# ver5b.net
KiCad netlist of a schematic drawn in EAGLE
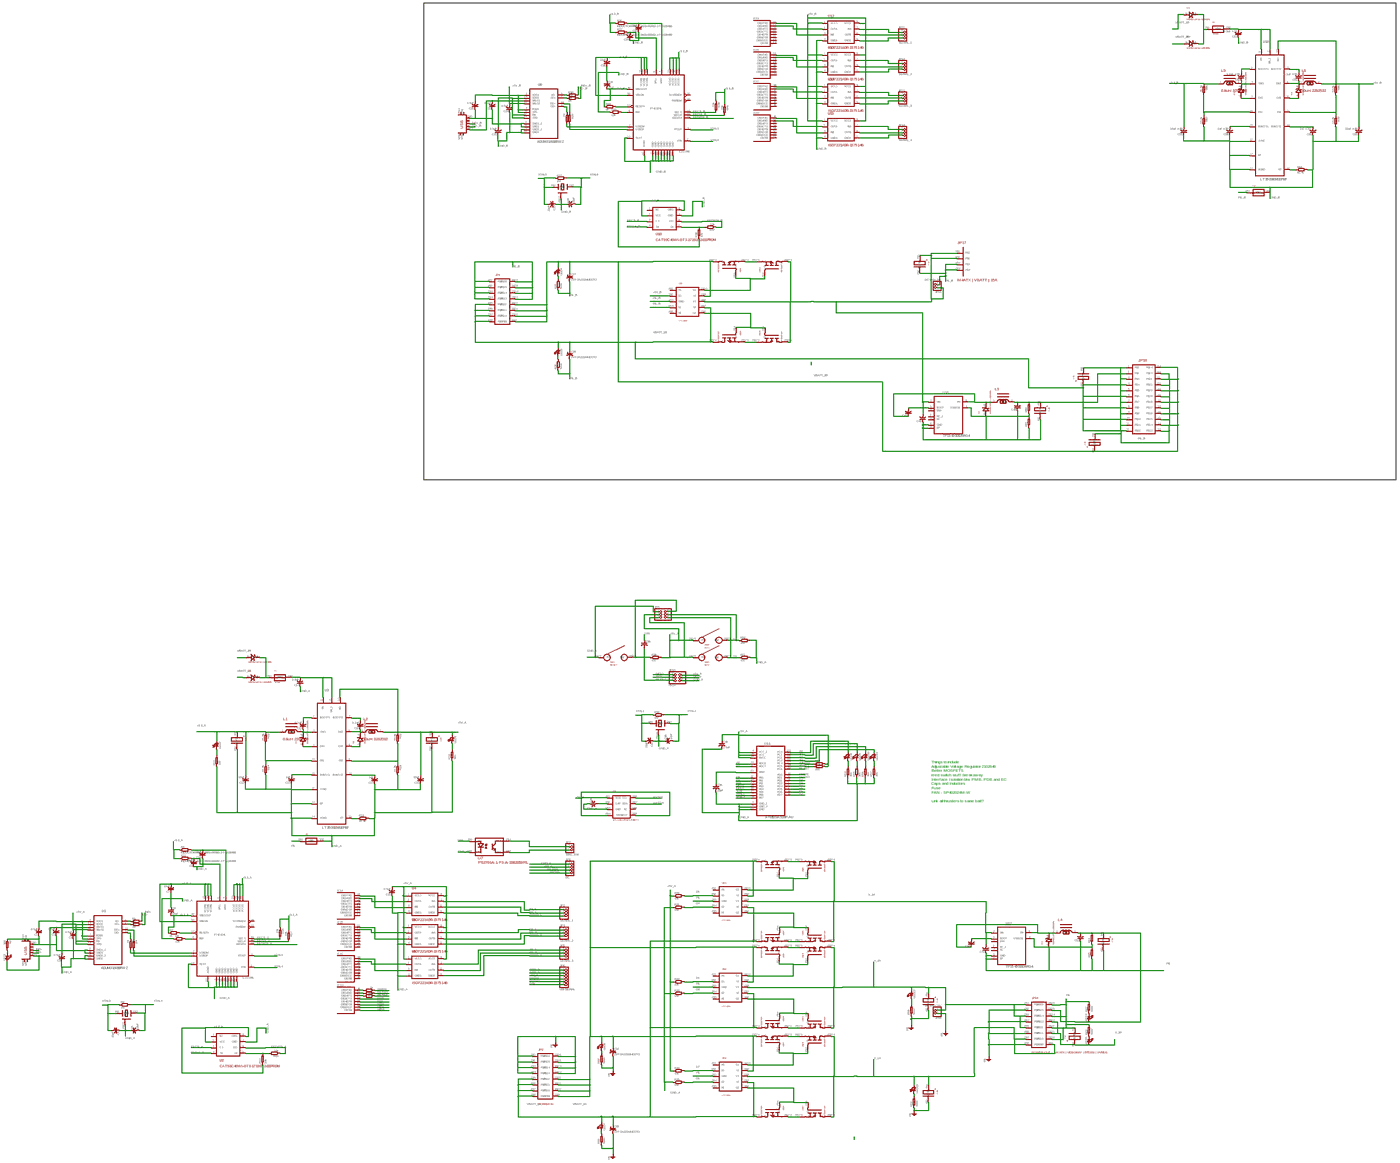
[diagram p0: schematic, sheet 1, overview]
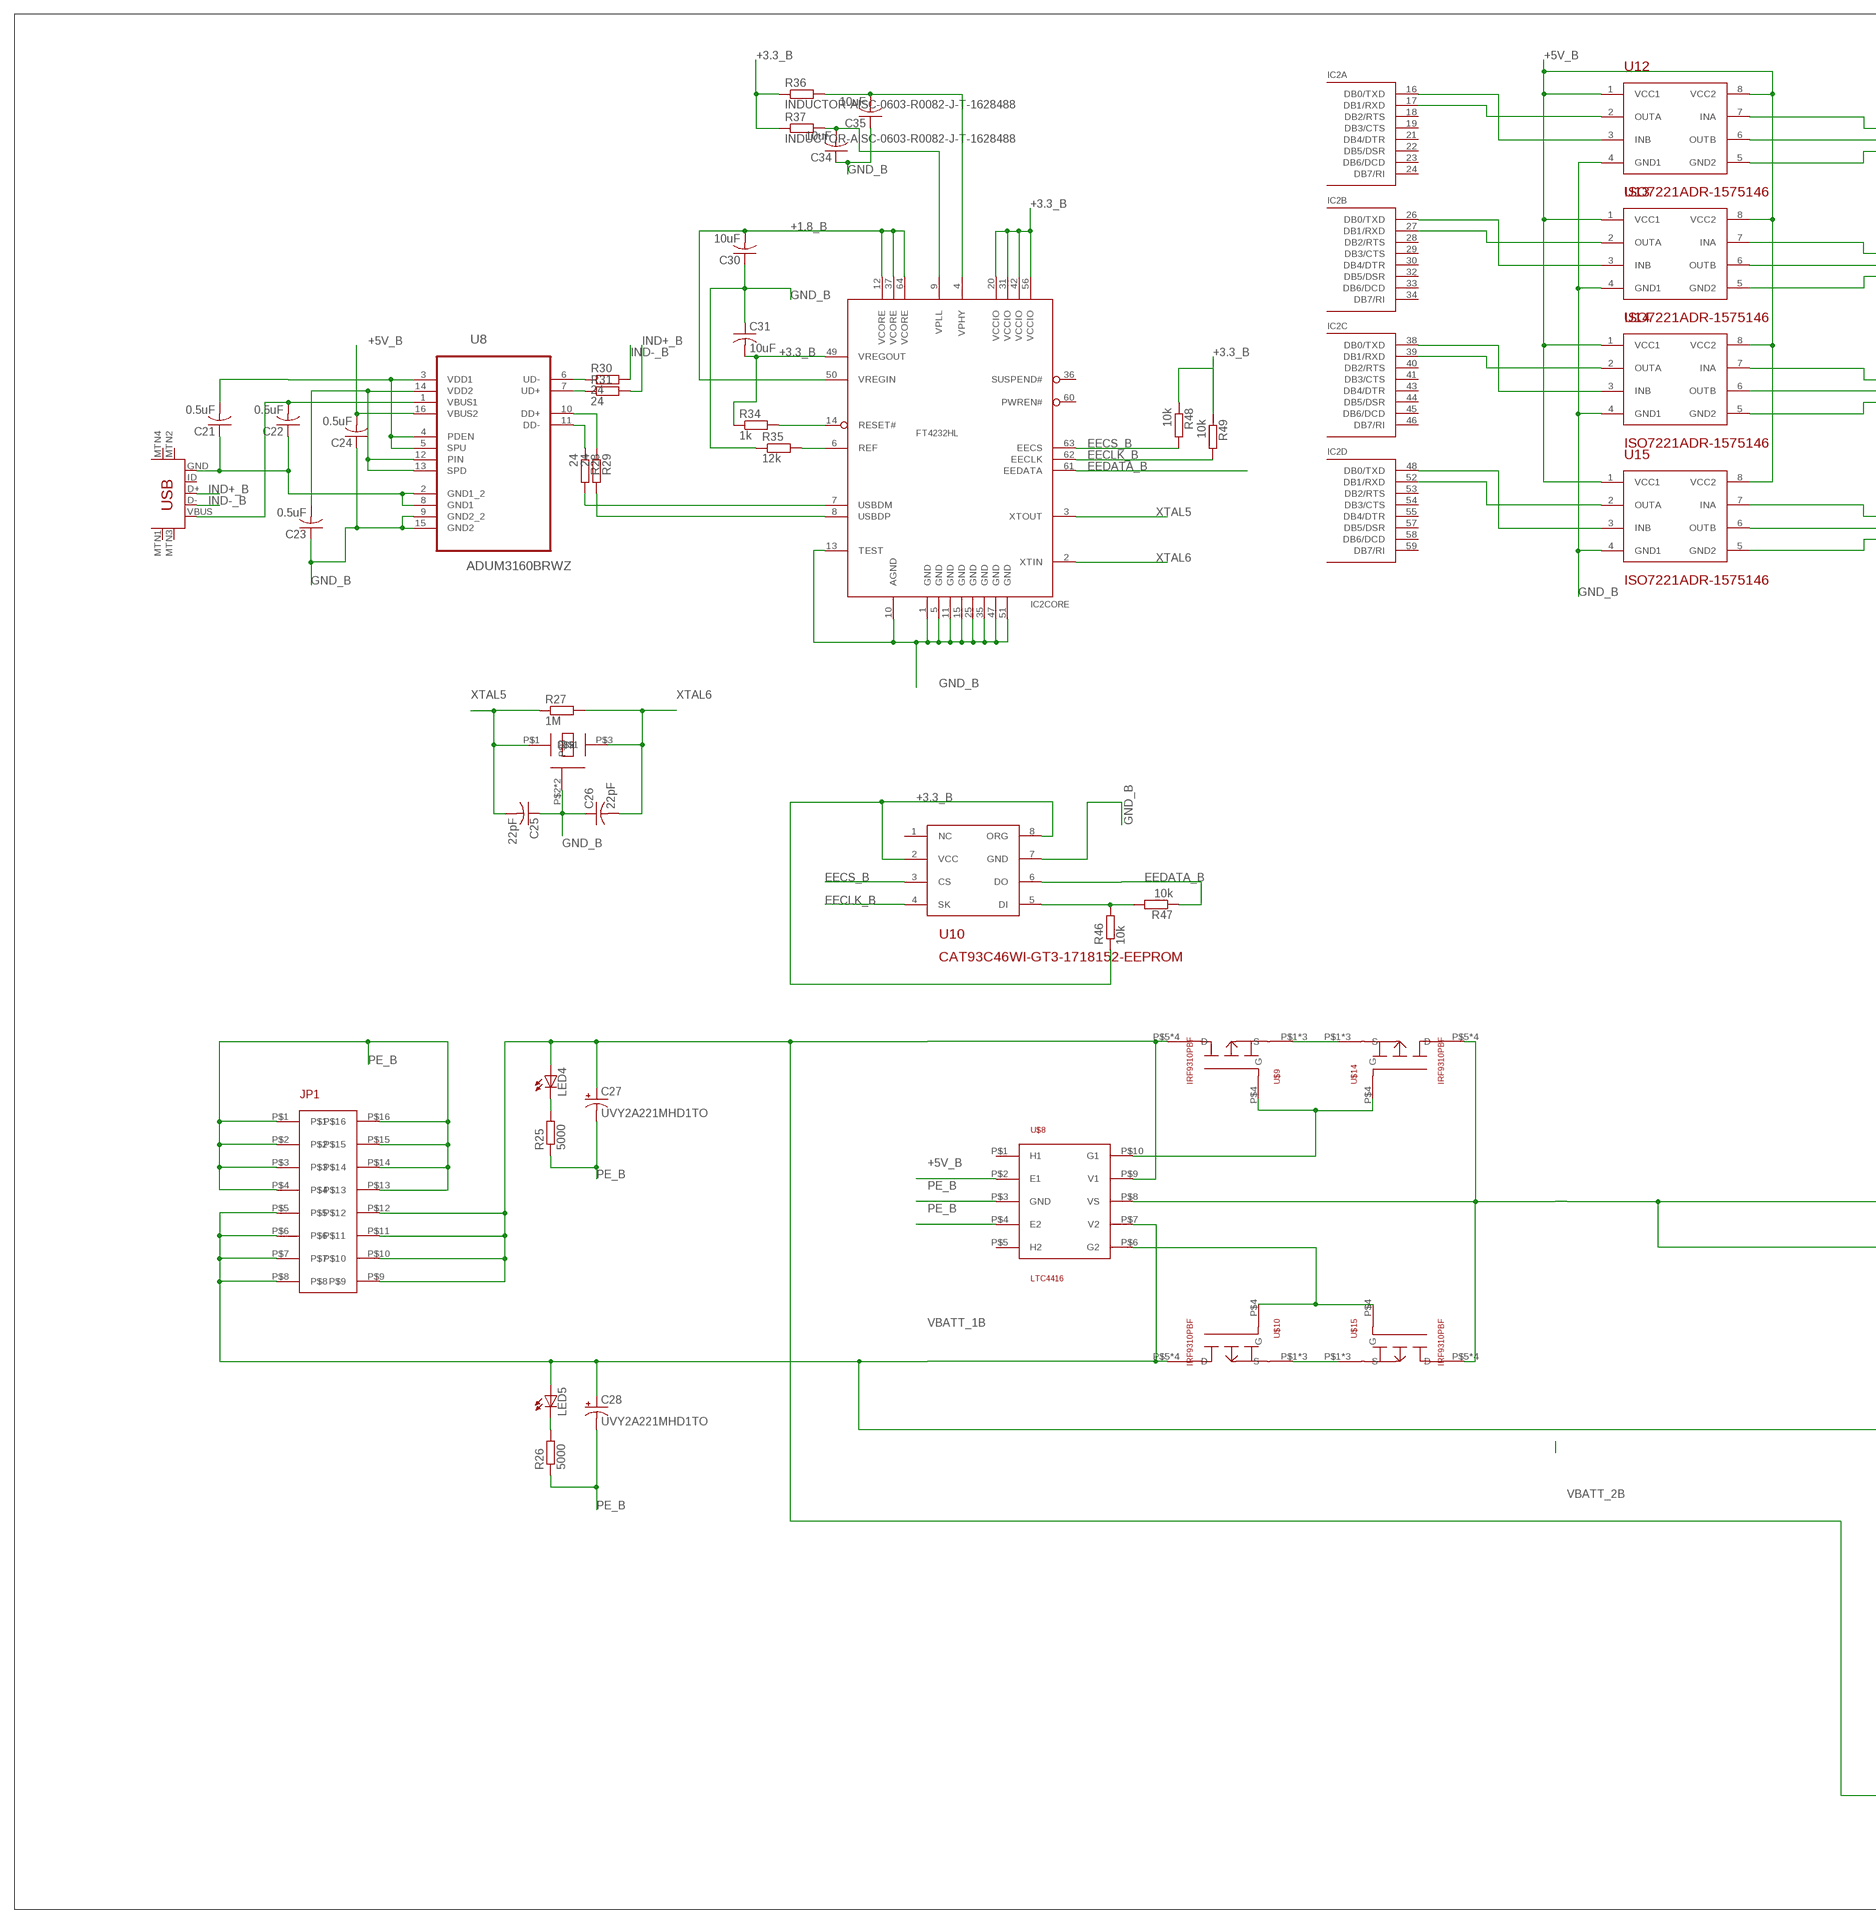
[diagram p1: schematic, sheet 1, part 1 of 6]
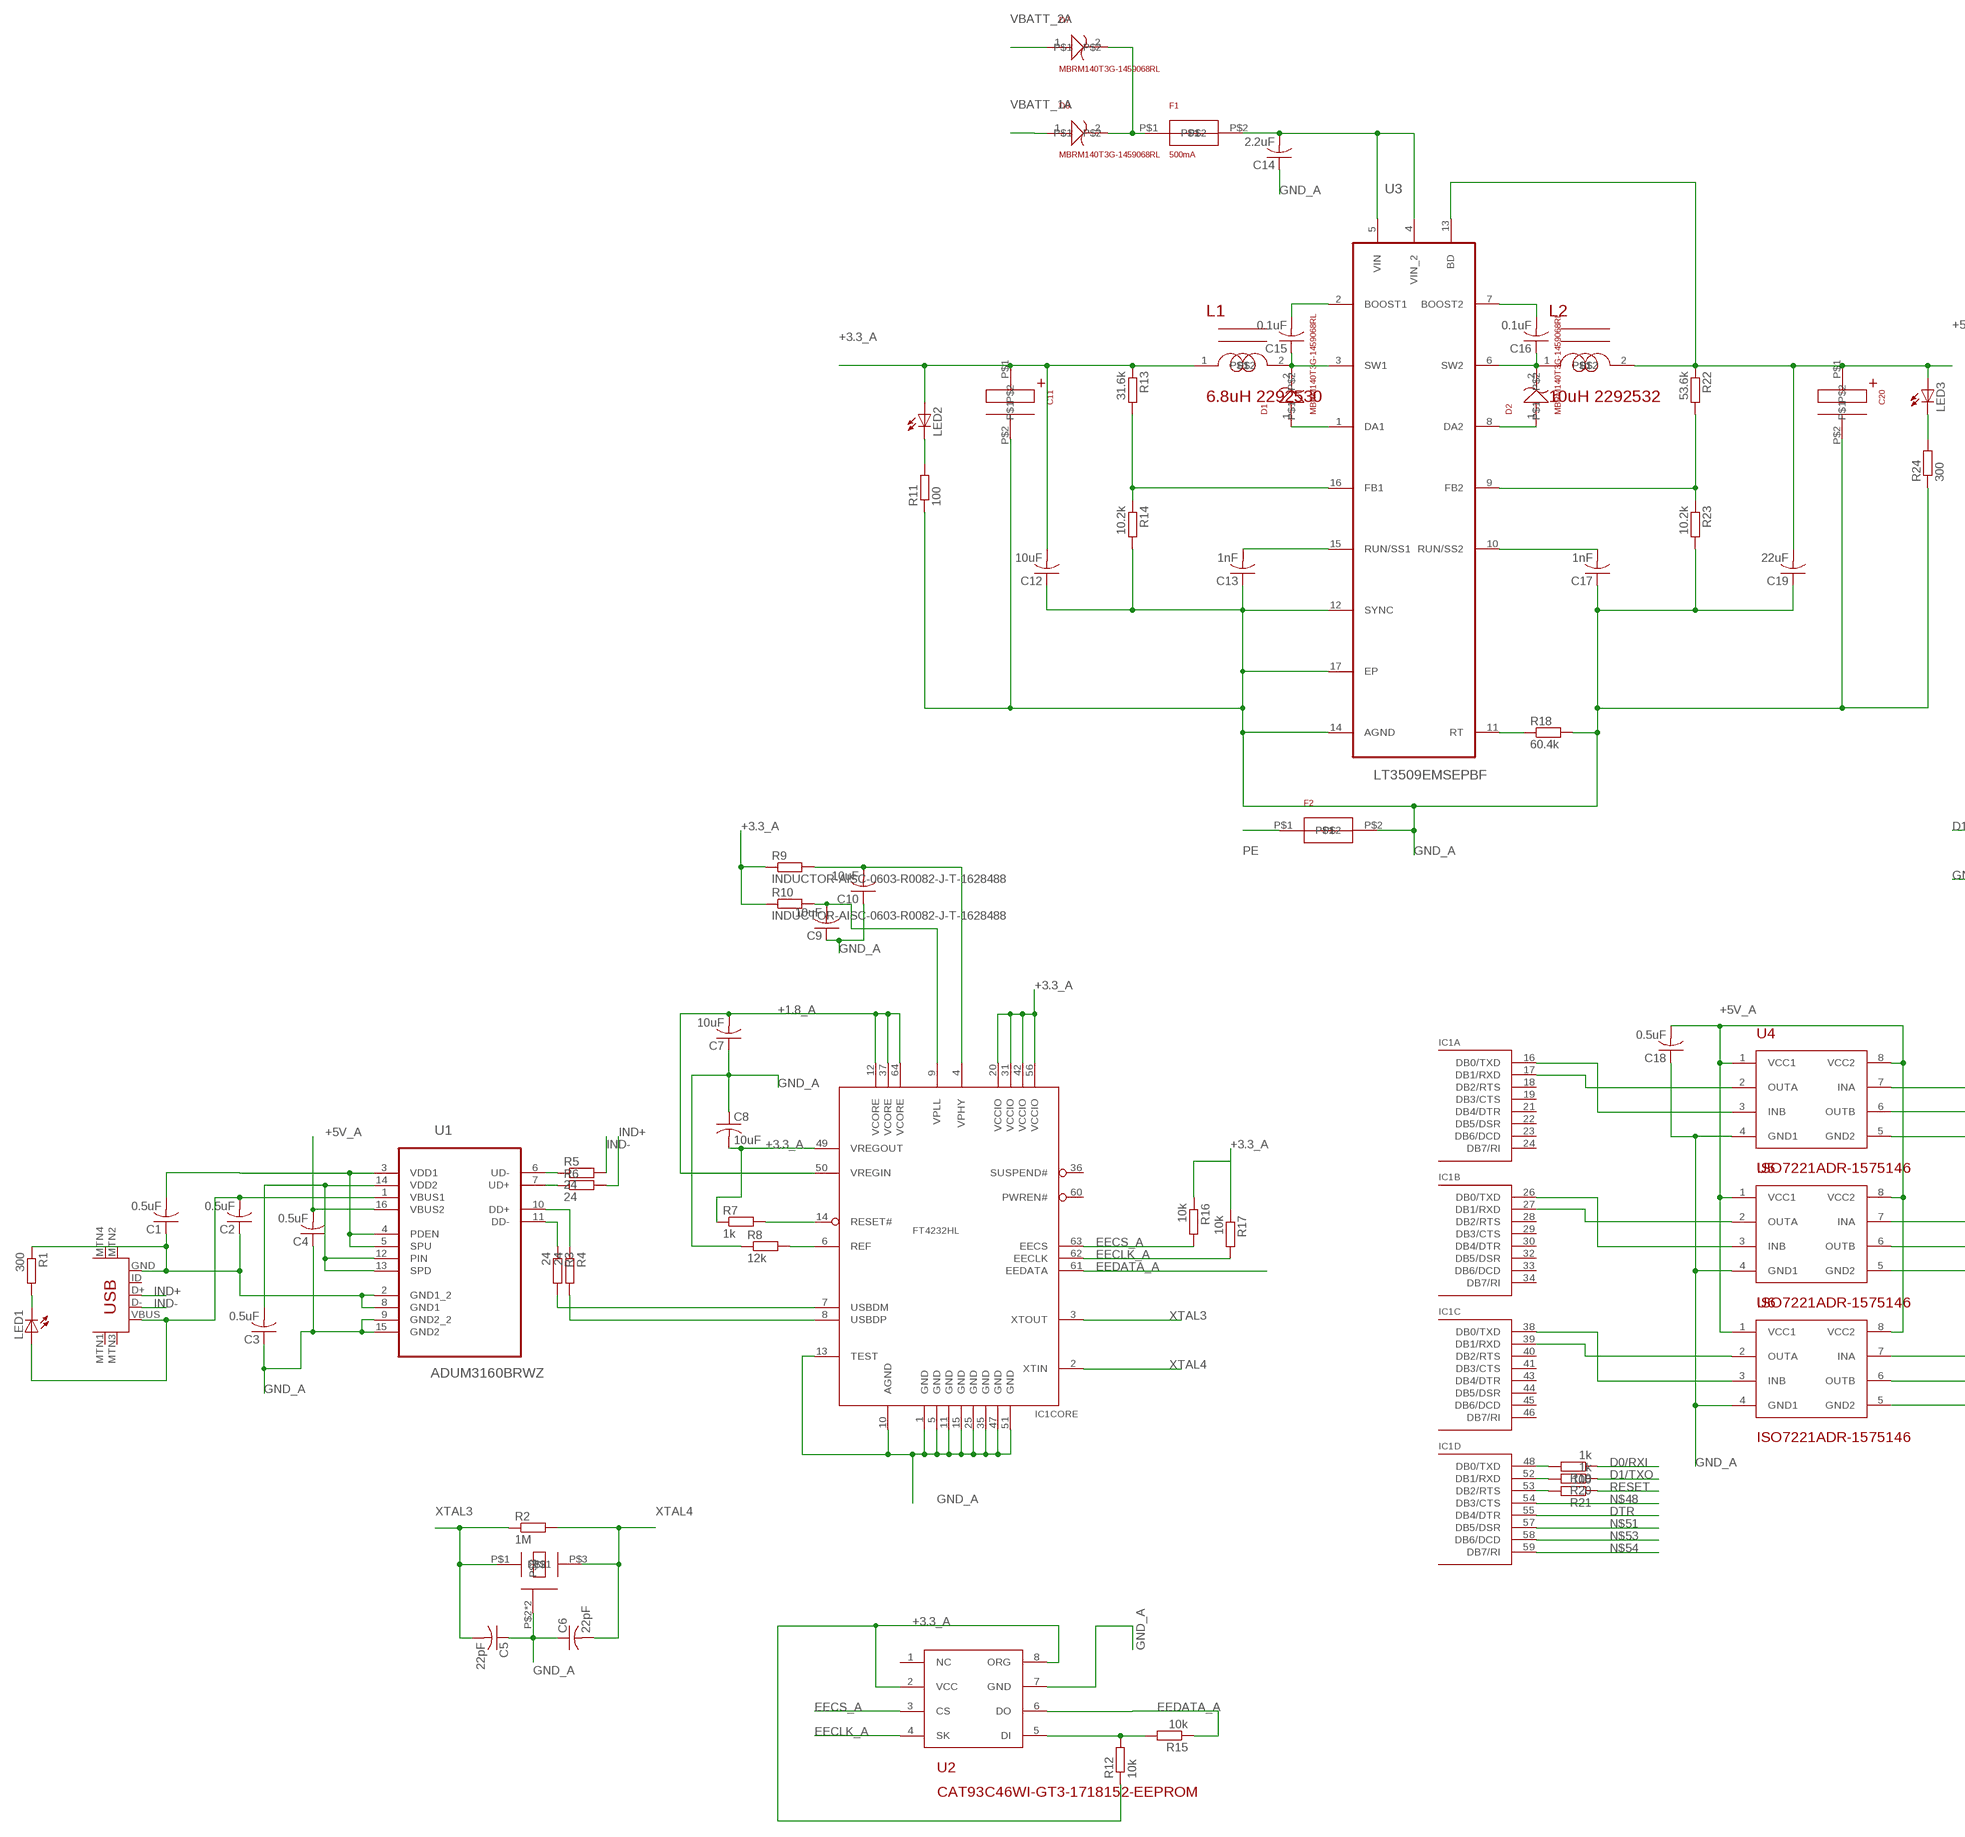
[diagram p2: schematic, sheet 1, part 2 of 6]
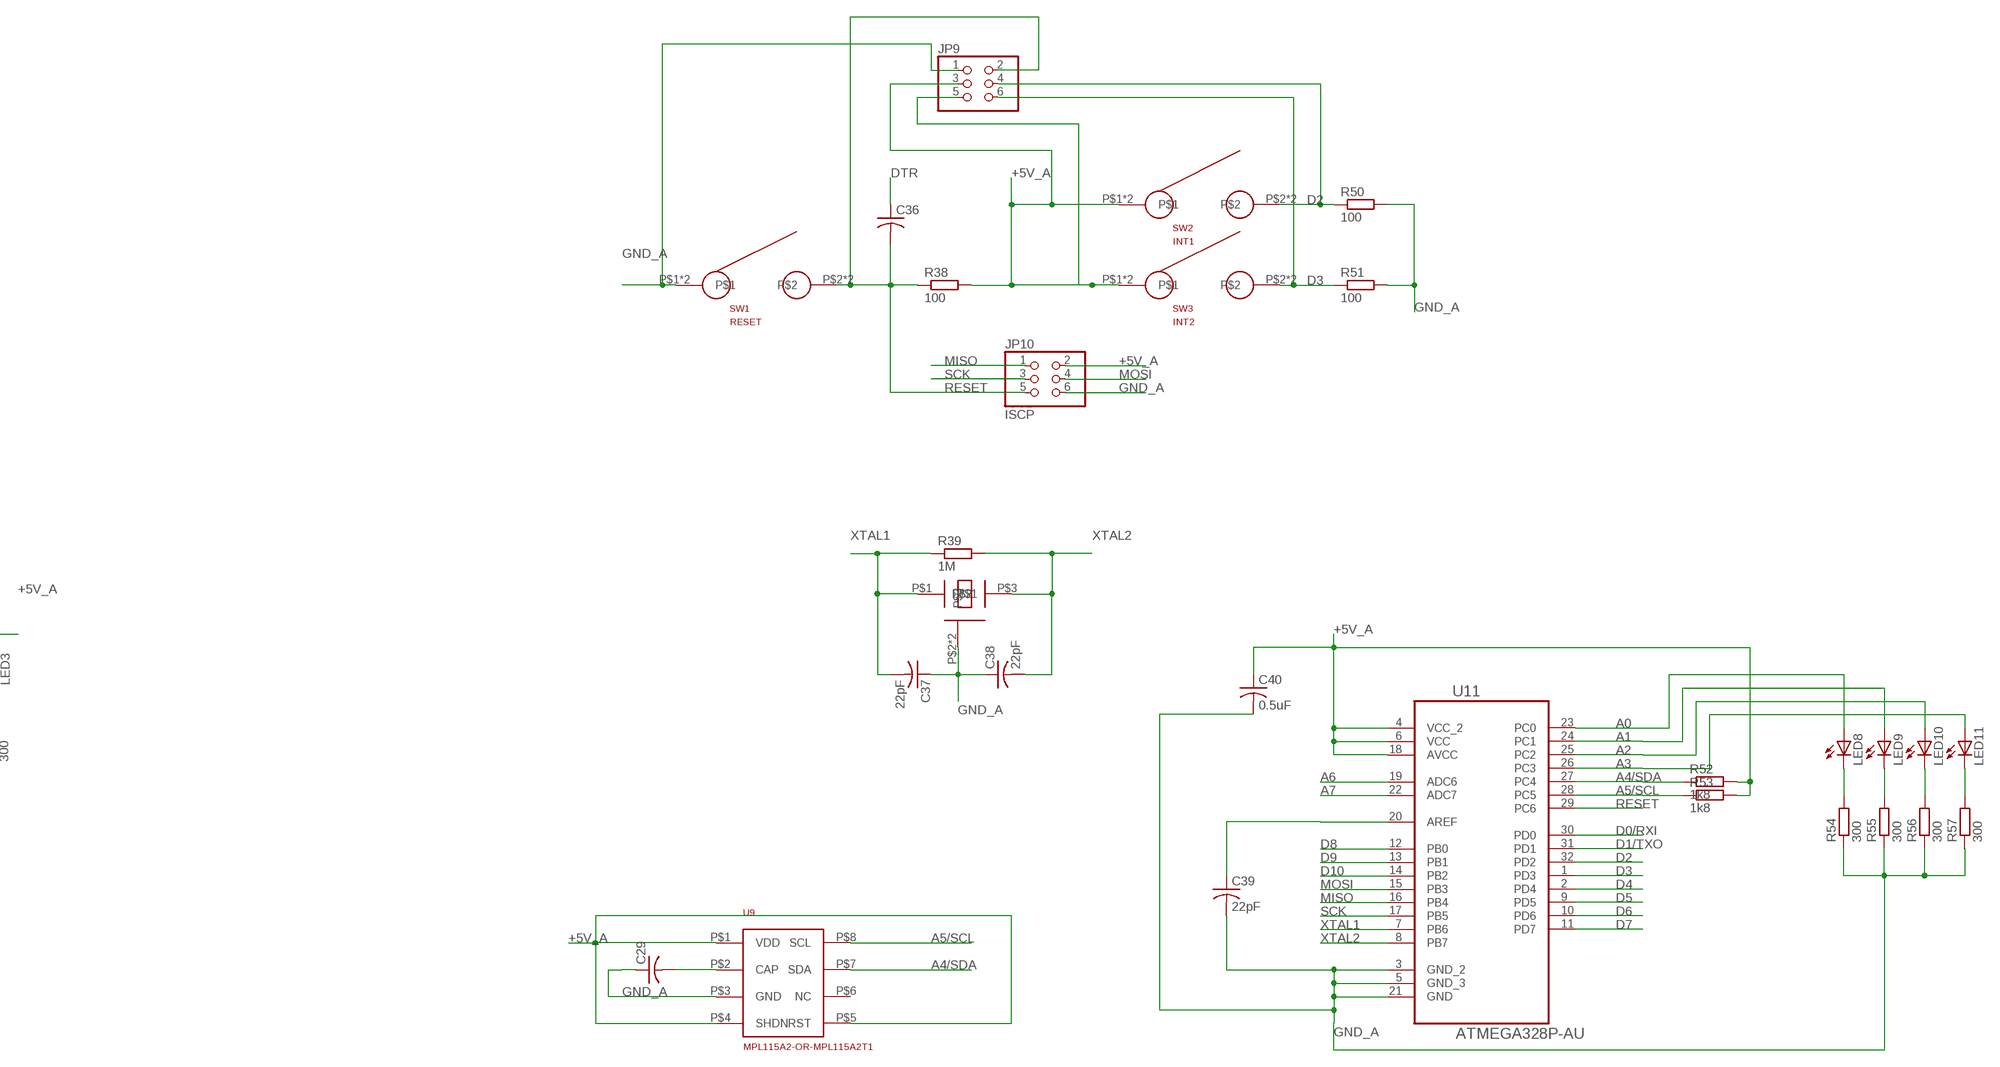
[diagram p3: schematic, sheet 1, part 3 of 6]
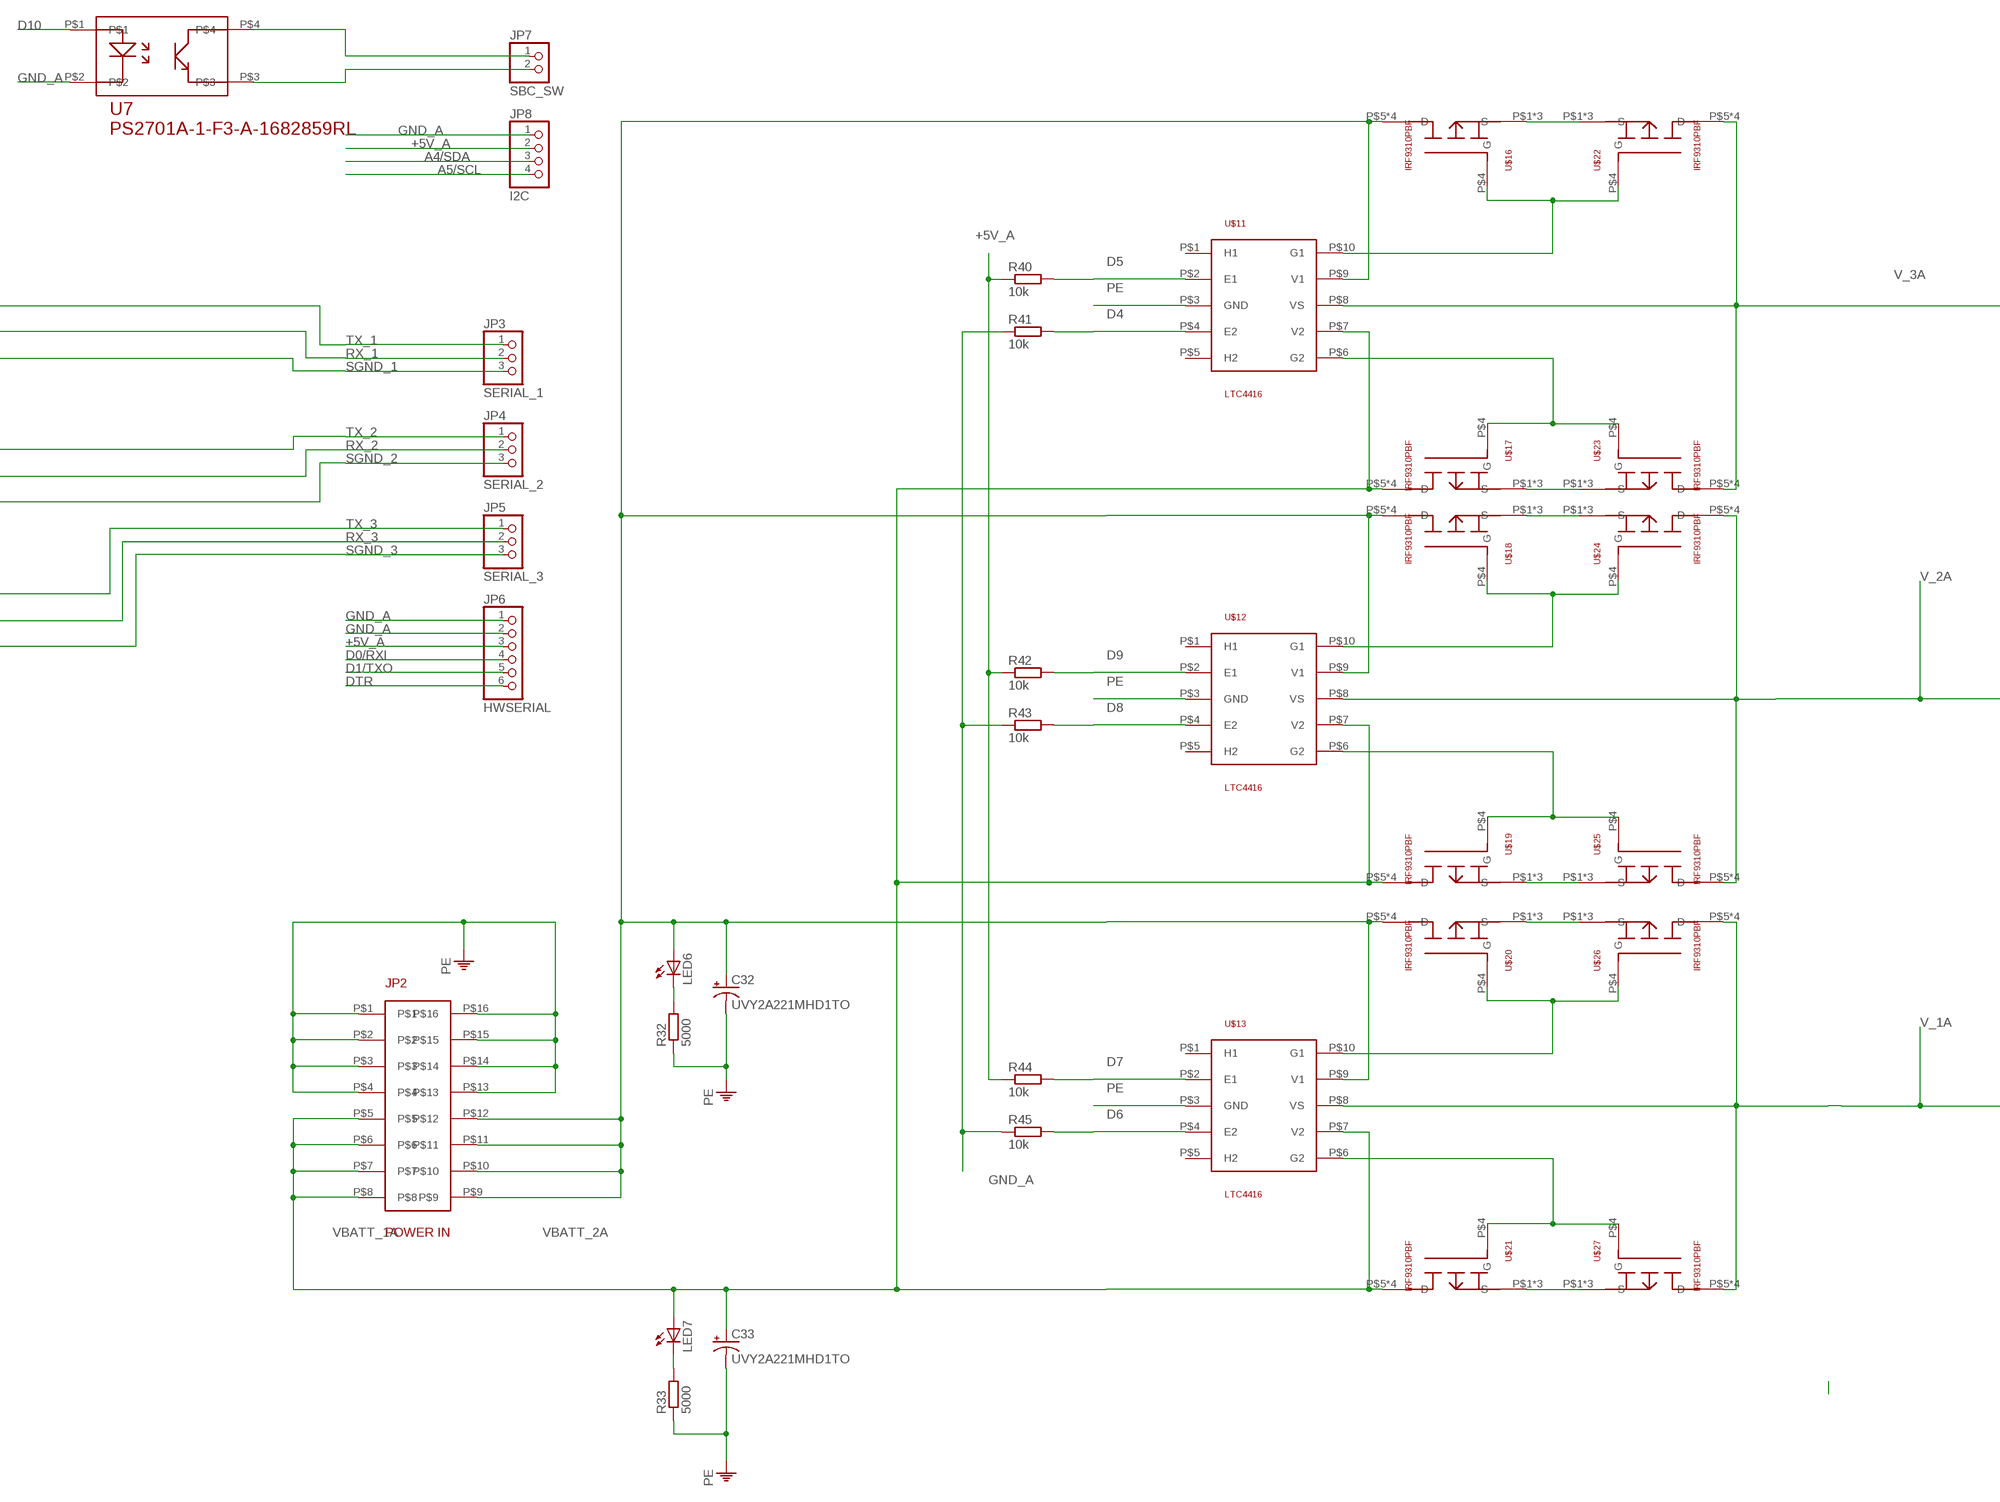
[diagram p4: schematic, sheet 1, part 4 of 6]
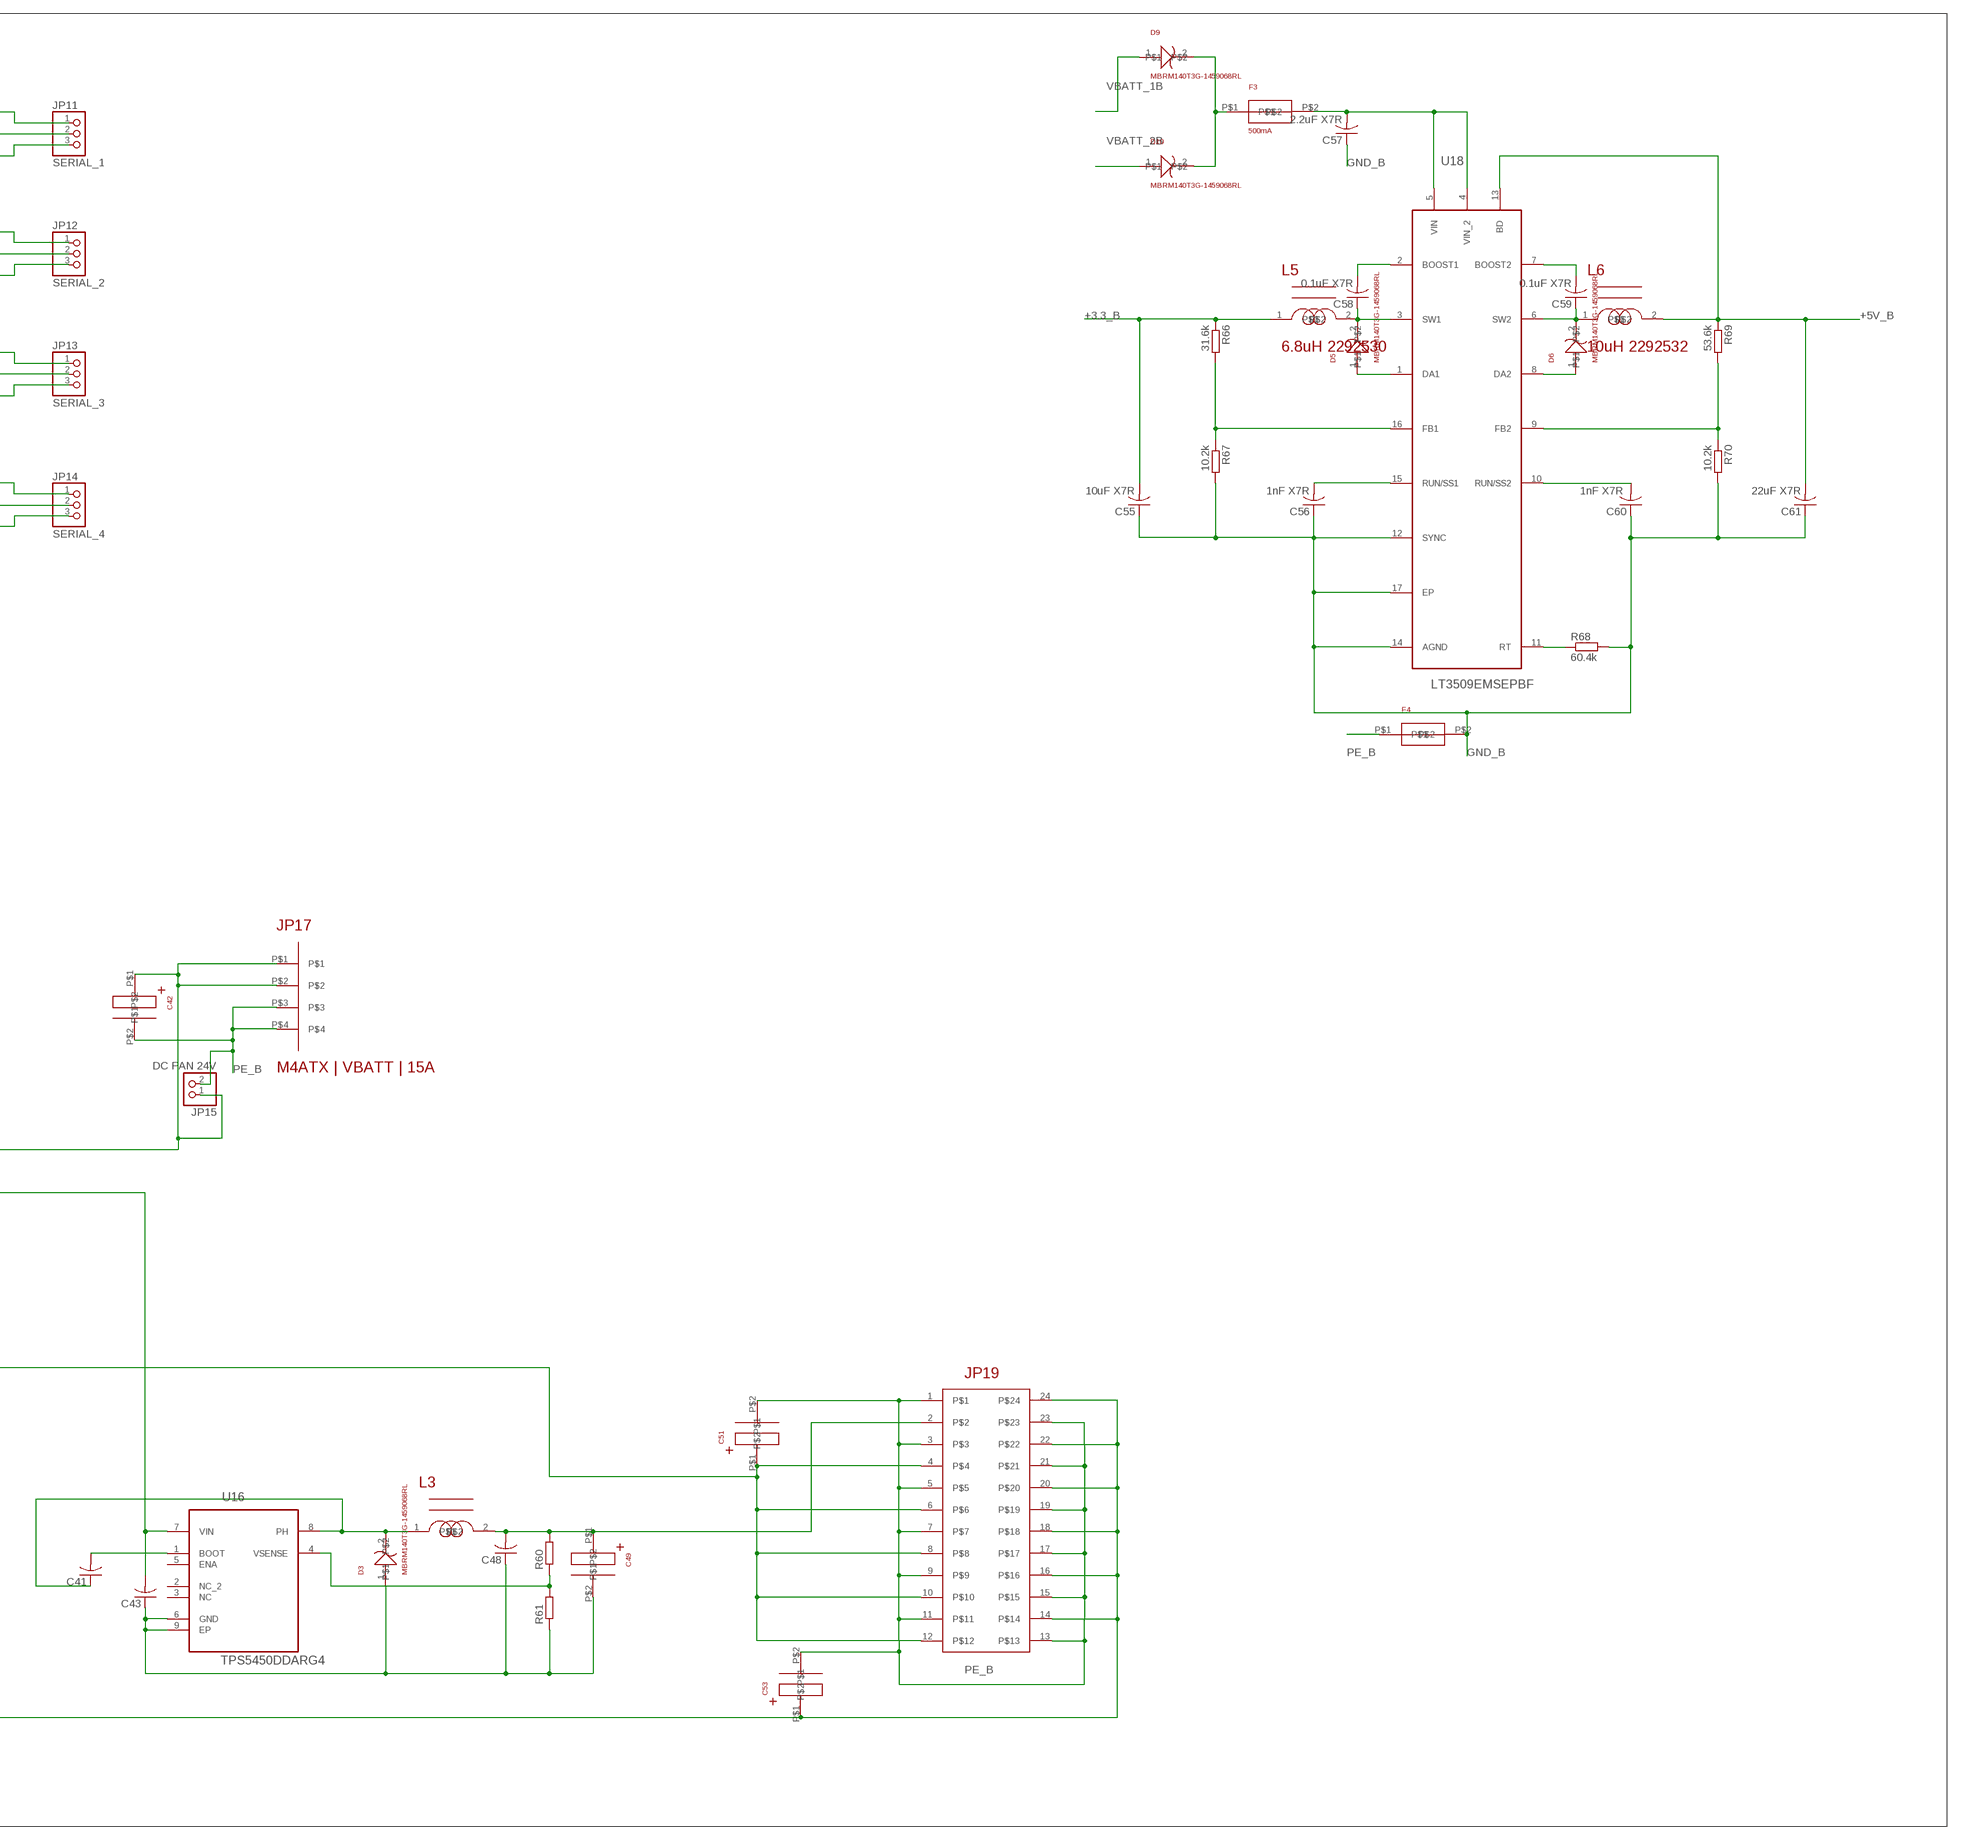
[diagram p5: schematic, sheet 1, part 5 of 6]
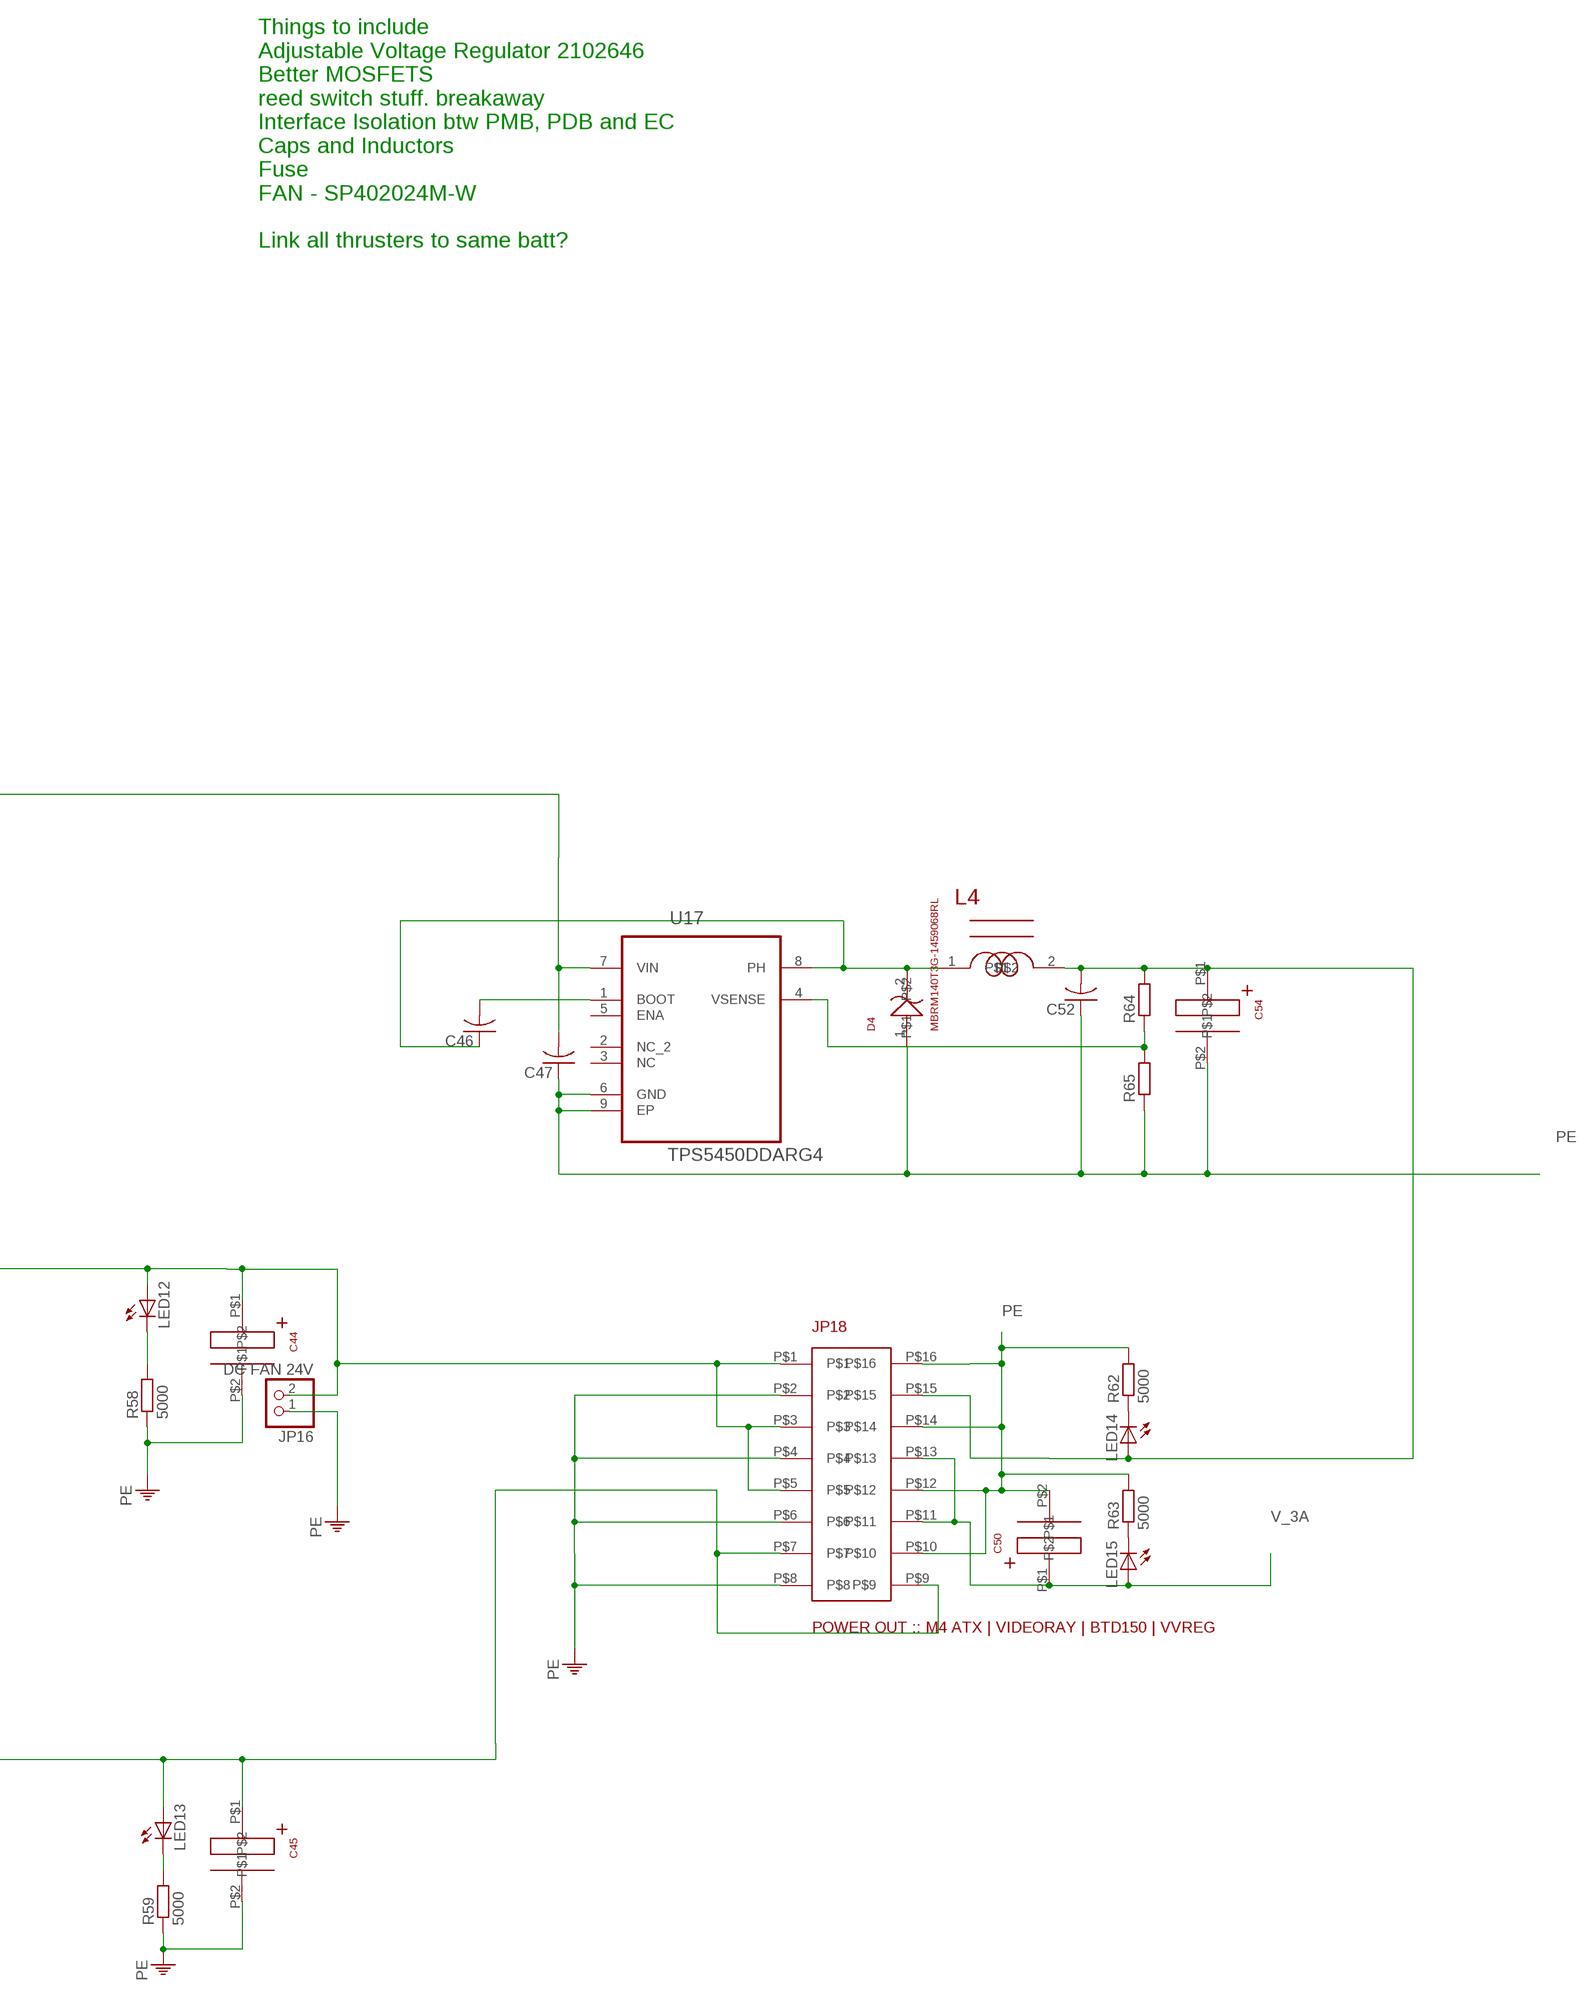
[diagram p6: schematic, sheet 1, part 6 of 6]

(export (version "E")
  (design (tool "Eeschema 10.0.6"))
  (components
    (comp (ref "C1")
      (value "0.5uF")
      (footprint "eagle-import:C1206")
      (libsource (lib "eagle-import") (part "C-USC1206"))
    )
    (comp (ref "C2")
      (value "0.5uF")
      (footprint "eagle-import:C1206")
      (libsource (lib "eagle-import") (part "C-USC1206"))
    )
    (comp (ref "C3")
      (value "0.5uF")
      (footprint "eagle-import:C1206")
      (libsource (lib "eagle-import") (part "C-USC1206"))
    )
    (comp (ref "C4")
      (value "0.5uF")
      (footprint "eagle-import:C1206")
      (libsource (lib "eagle-import") (part "C-USC1206"))
    )
    (comp (ref "C5")
      (value "22pF")
      (footprint "eagle-import:C1206")
      (libsource (lib "eagle-import") (part "C-USC1206"))
    )
    (comp (ref "C6")
      (value "22pF")
      (footprint "eagle-import:C1206")
      (libsource (lib "eagle-import") (part "C-USC1206"))
    )
    (comp (ref "C7")
      (value "10uF")
      (footprint "eagle-import:C1206")
      (libsource (lib "eagle-import") (part "C-USC1206"))
    )
    (comp (ref "C8")
      (value "10uF")
      (footprint "eagle-import:C1206")
      (libsource (lib "eagle-import") (part "C-USC1206"))
    )
    (comp (ref "C9")
      (value "10uF")
      (footprint "eagle-import:C1206")
      (libsource (lib "eagle-import") (part "C-USC1206"))
    )
    (comp (ref "C10")
      (value "10uF")
      (footprint "eagle-import:C1206")
      (libsource (lib "eagle-import") (part "C-USC1206"))
    )
    (comp (ref "C11")
      (value "EEEFTH101XAP")
      (footprint "eagle-import:EEEFTH101XAP")
      (libsource (lib "eagle-import") (part "EEEFTH101XAP"))
    )
    (comp (ref "C12")
      (value "10uF")
      (footprint "eagle-import:C1206")
      (libsource (lib "eagle-import") (part "C-USC1206"))
    )
    (comp (ref "C13")
      (value "1nF")
      (footprint "eagle-import:C1206")
      (libsource (lib "eagle-import") (part "C-USC1206"))
    )
    (comp (ref "C14")
      (value "2.2uF")
      (footprint "eagle-import:C1206")
      (libsource (lib "eagle-import") (part "C-USC1206"))
    )
    (comp (ref "C15")
      (value "0.1uF")
      (footprint "eagle-import:C1206")
      (libsource (lib "eagle-import") (part "C-USC1206"))
    )
    (comp (ref "C16")
      (value "0.1uF")
      (footprint "eagle-import:C1206")
      (libsource (lib "eagle-import") (part "C-USC1206"))
    )
    (comp (ref "C17")
      (value "1nF")
      (footprint "eagle-import:C1206")
      (libsource (lib "eagle-import") (part "C-USC1206"))
    )
    (comp (ref "C18")
      (value "0.5uF")
      (footprint "eagle-import:C1206")
      (libsource (lib "eagle-import") (part "C-USC1206"))
    )
    (comp (ref "C19")
      (value "22uF")
      (footprint "eagle-import:C1206")
      (libsource (lib "eagle-import") (part "C-USC1206"))
    )
    (comp (ref "C20")
      (value "EEEFTH101XAP")
      (footprint "eagle-import:EEEFTH101XAP")
      (libsource (lib "eagle-import") (part "EEEFTH101XAP"))
    )
    (comp (ref "C21")
      (value "0.5uF")
      (footprint "eagle-import:C1206")
      (libsource (lib "eagle-import") (part "C-USC1206"))
    )
    (comp (ref "C22")
      (value "0.5uF")
      (footprint "eagle-import:C1206")
      (libsource (lib "eagle-import") (part "C-USC1206"))
    )
    (comp (ref "C23")
      (value "0.5uF")
      (footprint "eagle-import:C1206")
      (libsource (lib "eagle-import") (part "C-USC1206"))
    )
    (comp (ref "C24")
      (value "0.5uF")
      (footprint "eagle-import:C1206")
      (libsource (lib "eagle-import") (part "C-USC1206"))
    )
    (comp (ref "C25")
      (value "22pF")
      (footprint "eagle-import:C1206")
      (libsource (lib "eagle-import") (part "C-USC1206"))
    )
    (comp (ref "C26")
      (value "22pF")
      (footprint "eagle-import:C1206")
      (libsource (lib "eagle-import") (part "C-USC1206"))
    )
    (comp (ref "C27")
      (value "UVY2A221MHD1TO")
      (footprint "eagle-import:E5-13")
      (libsource (lib "eagle-import") (part "CPOL-USE5-13"))
    )
    (comp (ref "C28")
      (value "UVY2A221MHD1TO")
      (footprint "eagle-import:E5-13")
      (libsource (lib "eagle-import") (part "CPOL-USE5-13"))
    )
    (comp (ref "C29")
      (value "C-USC1206")
      (footprint "eagle-import:C1206")
      (libsource (lib "eagle-import") (part "C-USC1206"))
    )
    (comp (ref "C30")
      (value "10uF")
      (footprint "eagle-import:C1206")
      (libsource (lib "eagle-import") (part "C-USC1206"))
    )
    (comp (ref "C31")
      (value "10uF")
      (footprint "eagle-import:C1206")
      (libsource (lib "eagle-import") (part "C-USC1206"))
    )
    (comp (ref "C32")
      (value "UVY2A221MHD1TO")
      (footprint "eagle-import:E5-13")
      (libsource (lib "eagle-import") (part "CPOL-USE5-13"))
    )
    (comp (ref "C33")
      (value "UVY2A221MHD1TO")
      (footprint "eagle-import:E5-13")
      (libsource (lib "eagle-import") (part "CPOL-USE5-13"))
    )
    (comp (ref "C34")
      (value "10uF")
      (footprint "eagle-import:C1206")
      (libsource (lib "eagle-import") (part "C-USC1206"))
    )
    (comp (ref "C35")
      (value "10uF")
      (footprint "eagle-import:C1206")
      (libsource (lib "eagle-import") (part "C-USC1206"))
    )
    (comp (ref "C36")
      (value "C-USC1206")
      (footprint "eagle-import:C1206")
      (libsource (lib "eagle-import") (part "C-USC1206"))
    )
    (comp (ref "C37")
      (value "22pF")
      (footprint "eagle-import:C1206")
      (libsource (lib "eagle-import") (part "C-USC1206"))
    )
    (comp (ref "C38")
      (value "22pF")
      (footprint "eagle-import:C1206")
      (libsource (lib "eagle-import") (part "C-USC1206"))
    )
    (comp (ref "C39")
      (value "22pF")
      (footprint "eagle-import:C1206")
      (libsource (lib "eagle-import") (part "C-USC1206"))
    )
    (comp (ref "C40")
      (value "0.5uF")
      (footprint "eagle-import:C1206")
      (libsource (lib "eagle-import") (part "C-USC1206"))
    )
    (comp (ref "C41")
      (value "C-USC1206")
      (footprint "eagle-import:C1206")
      (libsource (lib "eagle-import") (part "C-USC1206"))
    )
    (comp (ref "C42")
      (value "EEEFTH101XAP")
      (footprint "eagle-import:EEEFTH101XAP")
      (libsource (lib "eagle-import") (part "EEEFTH101XAP"))
    )
    (comp (ref "C43")
      (value "C-USC1206")
      (footprint "eagle-import:C1206")
      (libsource (lib "eagle-import") (part "C-USC1206"))
    )
    (comp (ref "C44")
      (value "EEEFTH101XAP")
      (footprint "eagle-import:EEEFTH101XAP")
      (libsource (lib "eagle-import") (part "EEEFTH101XAP"))
    )
    (comp (ref "C45")
      (value "EEEFTH101XAP")
      (footprint "eagle-import:EEEFTH101XAP")
      (libsource (lib "eagle-import") (part "EEEFTH101XAP"))
    )
    (comp (ref "C46")
      (value "C-USC1206")
      (footprint "eagle-import:C1206")
      (libsource (lib "eagle-import") (part "C-USC1206"))
    )
    (comp (ref "C47")
      (value "C-USC1206")
      (footprint "eagle-import:C1206")
      (libsource (lib "eagle-import") (part "C-USC1206"))
    )
    (comp (ref "C48")
      (value "C-USC1206")
      (footprint "eagle-import:C1206")
      (libsource (lib "eagle-import") (part "C-USC1206"))
    )
    (comp (ref "C49")
      (value "EEEFTH101XAP")
      (footprint "eagle-import:EEEFTH101XAP")
      (libsource (lib "eagle-import") (part "EEEFTH101XAP"))
    )
    (comp (ref "C50")
      (value "EEEFTH101XAP")
      (footprint "eagle-import:EEEFTH101XAP")
      (libsource (lib "eagle-import") (part "EEEFTH101XAP"))
    )
    (comp (ref "C51")
      (value "EEEFTH101XAP")
      (footprint "eagle-import:EEEFTH101XAP")
      (libsource (lib "eagle-import") (part "EEEFTH101XAP"))
    )
    (comp (ref "C52")
      (value "C-USC1206")
      (footprint "eagle-import:C1206")
      (libsource (lib "eagle-import") (part "C-USC1206"))
    )
    (comp (ref "C53")
      (value "EEEFTH101XAP")
      (footprint "eagle-import:EEEFTH101XAP")
      (libsource (lib "eagle-import") (part "EEEFTH101XAP"))
    )
    (comp (ref "C54")
      (value "EEEFTH101XAP")
      (footprint "eagle-import:EEEFTH101XAP")
      (libsource (lib "eagle-import") (part "EEEFTH101XAP"))
    )
    (comp (ref "C55")
      (value "10uF X7R")
      (footprint "eagle-import:C1206")
      (libsource (lib "eagle-import") (part "C-USC1206"))
    )
    (comp (ref "C56")
      (value "1nF X7R")
      (footprint "eagle-import:C1206")
      (libsource (lib "eagle-import") (part "C-USC1206"))
    )
    (comp (ref "C57")
      (value "2.2uF X7R")
      (footprint "eagle-import:C1206")
      (libsource (lib "eagle-import") (part "C-USC1206"))
    )
    (comp (ref "C58")
      (value "0.1uF X7R")
      (footprint "eagle-import:C1206")
      (libsource (lib "eagle-import") (part "C-USC1206"))
    )
    (comp (ref "C59")
      (value "0.1uF X7R")
      (footprint "eagle-import:C1206")
      (libsource (lib "eagle-import") (part "C-USC1206"))
    )
    (comp (ref "C60")
      (value "1nF X7R")
      (footprint "eagle-import:C1206")
      (libsource (lib "eagle-import") (part "C-USC1206"))
    )
    (comp (ref "C61")
      (value "22uF X7R")
      (footprint "eagle-import:C1206")
      (libsource (lib "eagle-import") (part "C-USC1206"))
    )
    (comp (ref "D1")
      (value "MBRM140T3G-1459068RL")
      (footprint "eagle-import:MBRM140T3G-1459068RL")
      (libsource (lib "eagle-import") (part "MBRM140T3G-1459068RL"))
    )
    (comp (ref "D2")
      (value "MBRM140T3G-1459068RL")
      (footprint "eagle-import:MBRM140T3G-1459068RL")
      (libsource (lib "eagle-import") (part "MBRM140T3G-1459068RL"))
    )
    (comp (ref "D3")
      (value "MBRM140T3G-1459068RL")
      (footprint "eagle-import:MBRM140T3G-1459068RL")
      (libsource (lib "eagle-import") (part "MBRM140T3G-1459068RL"))
    )
    (comp (ref "D4")
      (value "MBRM140T3G-1459068RL")
      (footprint "eagle-import:MBRM140T3G-1459068RL")
      (libsource (lib "eagle-import") (part "MBRM140T3G-1459068RL"))
    )
    (comp (ref "D5")
      (value "MBRM140T3G-1459068RL")
      (footprint "eagle-import:MBRM140T3G-1459068RL")
      (libsource (lib "eagle-import") (part "MBRM140T3G-1459068RL"))
    )
    (comp (ref "D6")
      (value "MBRM140T3G-1459068RL")
      (footprint "eagle-import:MBRM140T3G-1459068RL")
      (libsource (lib "eagle-import") (part "MBRM140T3G-1459068RL"))
    )
    (comp (ref "D7")
      (value "MBRM140T3G-1459068RL")
      (footprint "eagle-import:MBRM140T3G-1459068RL")
      (libsource (lib "eagle-import") (part "MBRM140T3G-1459068RL"))
    )
    (comp (ref "D8")
      (value "MBRM140T3G-1459068RL")
      (footprint "eagle-import:MBRM140T3G-1459068RL")
      (libsource (lib "eagle-import") (part "MBRM140T3G-1459068RL"))
    )
    (comp (ref "D9")
      (value "MBRM140T3G-1459068RL")
      (footprint "eagle-import:MBRM140T3G-1459068RL")
      (libsource (lib "eagle-import") (part "MBRM140T3G-1459068RL"))
    )
    (comp (ref "D10")
      (value "MBRM140T3G-1459068RL")
      (footprint "eagle-import:MBRM140T3G-1459068RL")
      (libsource (lib "eagle-import") (part "MBRM140T3G-1459068RL"))
    )
    (comp (ref "F1")
      (value "500mA")
      (footprint "eagle-import:MF-MSMF050-2")
      (libsource (lib "eagle-import") (part "MF-MSMF050-2"))
    )
    (comp (ref "F2")
      (value "0154.500DR-FUSE-0453.500")
      (footprint "eagle-import:0154.500DR-FUSE-0453.500")
      (libsource (lib "eagle-import") (part "0154.500DR-FUSE-0453.500"))
    )
    (comp (ref "F3")
      (value "500mA")
      (footprint "eagle-import:MF-MSMF050-2")
      (libsource (lib "eagle-import") (part "MF-MSMF050-2"))
    )
    (comp (ref "F4")
      (value "0154.500DR-FUSE-0453.500")
      (footprint "eagle-import:0154.500DR-FUSE-0453.500")
      (libsource (lib "eagle-import") (part "0154.500DR-FUSE-0453.500"))
    )
    (comp (ref "IC1")
      (value "FT4232HL")
      (footprint "eagle-import:LQFP64")
      (libsource (lib "eagle-import") (part "FT4232HL"))
    )
    (comp (ref "IC2")
      (value "FT4232HL")
      (footprint "eagle-import:LQFP64")
      (libsource (lib "eagle-import") (part "FT4232HL"))
    )
    (comp (ref "JP1")
      (value "39-29-1167-MOLEX")
      (footprint "eagle-import:39-29-1167-MOLEX")
      (libsource (lib "eagle-import") (part "39-29-1167-MOLEX"))
    )
    (comp (ref "JP2")
      (value "POWER IN")
      (footprint "eagle-import:39-29-1167-MOLEX")
      (libsource (lib "eagle-import") (part "39-29-1167-MOLEX"))
    )
    (comp (ref "JP3")
      (value "SERIAL_1")
      (footprint "eagle-import:1X03_90")
      (libsource (lib "eagle-import") (part "PINHD-1X3/90"))
    )
    (comp (ref "JP4")
      (value "SERIAL_2")
      (footprint "eagle-import:1X03_90")
      (libsource (lib "eagle-import") (part "PINHD-1X3/90"))
    )
    (comp (ref "JP5")
      (value "SERIAL_3")
      (footprint "eagle-import:1X03_90")
      (libsource (lib "eagle-import") (part "PINHD-1X3/90"))
    )
    (comp (ref "JP6")
      (value "HWSERIAL")
      (footprint "eagle-import:1X06")
      (libsource (lib "eagle-import") (part "PINHD-1X6"))
    )
    (comp (ref "JP7")
      (value "SBC_SW")
      (footprint "eagle-import:1X02")
      (libsource (lib "eagle-import") (part "PINHD-1X2"))
    )
    (comp (ref "JP8")
      (value "I2C")
      (footprint "eagle-import:1X04")
      (libsource (lib "eagle-import") (part "PINHD-1X4"))
    )
    (comp (ref "JP9")
      (value "PINHD-2X3")
      (footprint "eagle-import:2X03")
      (libsource (lib "eagle-import") (part "PINHD-2X3"))
    )
    (comp (ref "JP10")
      (value "ISCP")
      (footprint "eagle-import:2X03")
      (libsource (lib "eagle-import") (part "PINHD-2X3"))
    )
    (comp (ref "JP11")
      (value "SERIAL_1")
      (footprint "eagle-import:1X03_90")
      (libsource (lib "eagle-import") (part "PINHD-1X3/90"))
    )
    (comp (ref "JP12")
      (value "SERIAL_2")
      (footprint "eagle-import:1X03_90")
      (libsource (lib "eagle-import") (part "PINHD-1X3/90"))
    )
    (comp (ref "JP13")
      (value "SERIAL_3")
      (footprint "eagle-import:1X03_90")
      (libsource (lib "eagle-import") (part "PINHD-1X3/90"))
    )
    (comp (ref "JP14")
      (value "SERIAL_4")
      (footprint "eagle-import:1X03_90")
      (libsource (lib "eagle-import") (part "PINHD-1X3/90"))
    )
    (comp (ref "JP15")
      (value "DC FAN 24V")
      (footprint "eagle-import:1X02")
      (libsource (lib "eagle-import") (part "PINHD-1X2"))
    )
    (comp (ref "JP16")
      (value "DC FAN 24V")
      (footprint "eagle-import:1X02")
      (libsource (lib "eagle-import") (part "PINHD-1X2"))
    )
    (comp (ref "JP17")
      (value "M4ATX | VBATT | 15A")
      (footprint "eagle-import:39-29-4049-MOLEX")
      (libsource (lib "eagle-import") (part "39-29-4049-MOLEX"))
    )
    (comp (ref "JP18")
      (value "POWER OUT :: M4 ATX | VIDEORAY | BTD150 | VVREG")
      (footprint "eagle-import:39-29-1167-MOLEX")
      (libsource (lib "eagle-import") (part "39-29-1167-MOLEX"))
    )
    (comp (ref "JP19")
      (value "43045-2400")
      (footprint "eagle-import:43045-2400")
      (libsource (lib "eagle-import") (part "43045-2400"))
    )
    (comp (ref "L1")
      (value "6.8uH 2292530")
      (footprint "eagle-import:LAIRD-TECH-INDUCTOR-TYS5040")
      (libsource (lib "eagle-import") (part "LAIRD-TECH-INDUCTOR-TYS5040"))
    )
    (comp (ref "L2")
      (value "10uH 2292532")
      (footprint "eagle-import:LAIRD-TECH-INDUCTOR-TYS5040")
      (libsource (lib "eagle-import") (part "LAIRD-TECH-INDUCTOR-TYS5040"))
    )
    (comp (ref "L3")
      (value "SER1360-802KLD-2288814RL-INDUCTOR")
      (footprint "eagle-import:SER1360-802KLD-2288814RL-INDUCTOR")
      (libsource (lib "eagle-import") (part "SER1360-802KLD-2288814RL-INDUCTOR"))
    )
    (comp (ref "L4")
      (value "SER1360-802KLD-2288814RL-INDUCTOR")
      (footprint "eagle-import:SER1360-802KLD-2288814RL-INDUCTOR")
      (libsource (lib "eagle-import") (part "SER1360-802KLD-2288814RL-INDUCTOR"))
    )
    (comp (ref "L5")
      (value "6.8uH 2292530")
      (footprint "eagle-import:LAIRD-TECH-INDUCTOR-TYS5040")
      (libsource (lib "eagle-import") (part "LAIRD-TECH-INDUCTOR-TYS5040"))
    )
    (comp (ref "L6")
      (value "10uH 2292532")
      (footprint "eagle-import:LAIRD-TECH-INDUCTOR-TYS5040")
      (libsource (lib "eagle-import") (part "LAIRD-TECH-INDUCTOR-TYS5040"))
    )
    (comp (ref "LED1")
      (value "LEDCHIPLED_1206")
      (footprint "eagle-import:CHIPLED_1206")
      (libsource (lib "eagle-import") (part "LEDCHIPLED_1206"))
    )
    (comp (ref "LED2")
      (value "LEDCHIPLED_1206")
      (footprint "eagle-import:CHIPLED_1206")
      (libsource (lib "eagle-import") (part "LEDCHIPLED_1206"))
    )
    (comp (ref "LED3")
      (value "LEDCHIPLED_1206")
      (footprint "eagle-import:CHIPLED_1206")
      (libsource (lib "eagle-import") (part "LEDCHIPLED_1206"))
    )
    (comp (ref "LED4")
      (value "LEDCHIPLED_1206")
      (footprint "eagle-import:CHIPLED_1206")
      (libsource (lib "eagle-import") (part "LEDCHIPLED_1206"))
    )
    (comp (ref "LED5")
      (value "LEDCHIPLED_1206")
      (footprint "eagle-import:CHIPLED_1206")
      (libsource (lib "eagle-import") (part "LEDCHIPLED_1206"))
    )
    (comp (ref "LED6")
      (value "LEDCHIPLED_1206")
      (footprint "eagle-import:CHIPLED_1206")
      (libsource (lib "eagle-import") (part "LEDCHIPLED_1206"))
    )
    (comp (ref "LED7")
      (value "LEDCHIPLED_1206")
      (footprint "eagle-import:CHIPLED_1206")
      (libsource (lib "eagle-import") (part "LEDCHIPLED_1206"))
    )
    (comp (ref "LED8")
      (value "LEDCHIPLED_1206")
      (footprint "eagle-import:CHIPLED_1206")
      (libsource (lib "eagle-import") (part "LEDCHIPLED_1206"))
    )
    (comp (ref "LED9")
      (value "LEDCHIPLED_1206")
      (footprint "eagle-import:CHIPLED_1206")
      (libsource (lib "eagle-import") (part "LEDCHIPLED_1206"))
    )
    (comp (ref "LED10")
      (value "LEDCHIPLED_1206")
      (footprint "eagle-import:CHIPLED_1206")
      (libsource (lib "eagle-import") (part "LEDCHIPLED_1206"))
    )
    (comp (ref "LED11")
      (value "LEDCHIPLED_1206")
      (footprint "eagle-import:CHIPLED_1206")
      (libsource (lib "eagle-import") (part "LEDCHIPLED_1206"))
    )
    (comp (ref "LED12")
      (value "LEDCHIPLED_1206")
      (footprint "eagle-import:CHIPLED_1206")
      (libsource (lib "eagle-import") (part "LEDCHIPLED_1206"))
    )
    (comp (ref "LED13")
      (value "LEDCHIPLED_1206")
      (footprint "eagle-import:CHIPLED_1206")
      (libsource (lib "eagle-import") (part "LEDCHIPLED_1206"))
    )
    (comp (ref "LED14")
      (value "LEDCHIPLED_1206")
      (footprint "eagle-import:CHIPLED_1206")
      (libsource (lib "eagle-import") (part "LEDCHIPLED_1206"))
    )
    (comp (ref "LED15")
      (value "LEDCHIPLED_1206")
      (footprint "eagle-import:CHIPLED_1206")
      (libsource (lib "eagle-import") (part "LEDCHIPLED_1206"))
    )
    (comp (ref "R1")
      (value "300")
      (footprint "eagle-import:R1206")
      (libsource (lib "eagle-import") (part "R-EU_R1206"))
    )
    (comp (ref "R2")
      (value "1M")
      (footprint "eagle-import:R1206")
      (libsource (lib "eagle-import") (part "R-EU_R1206"))
    )
    (comp (ref "R3")
      (value "24")
      (footprint "eagle-import:R1206")
      (libsource (lib "eagle-import") (part "R-EU_R1206"))
    )
    (comp (ref "R4")
      (value "24")
      (footprint "eagle-import:R1206")
      (libsource (lib "eagle-import") (part "R-EU_R1206"))
    )
    (comp (ref "R5")
      (value "24")
      (footprint "eagle-import:R1206")
      (libsource (lib "eagle-import") (part "R-EU_R1206"))
    )
    (comp (ref "R6")
      (value "24")
      (footprint "eagle-import:R1206")
      (libsource (lib "eagle-import") (part "R-EU_R1206"))
    )
    (comp (ref "R7")
      (value "1k")
      (footprint "eagle-import:R1206")
      (libsource (lib "eagle-import") (part "R-EU_R1206"))
    )
    (comp (ref "R8")
      (value "12k")
      (footprint "eagle-import:R1206")
      (libsource (lib "eagle-import") (part "R-EU_R1206"))
    )
    (comp (ref "R9")
      (value "INDUCTOR-AISC-0603-R0082-J-T-1628488")
      (footprint "eagle-import:R0603")
      (libsource (lib "eagle-import") (part "R-EU_R0603"))
    )
    (comp (ref "R10")
      (value "INDUCTOR-AISC-0603-R0082-J-T-1628488")
      (footprint "eagle-import:R0603")
      (libsource (lib "eagle-import") (part "R-EU_R0603"))
    )
    (comp (ref "R11")
      (value "100")
      (footprint "eagle-import:R1206")
      (libsource (lib "eagle-import") (part "R-EU_R1206"))
    )
    (comp (ref "R12")
      (value "10k")
      (footprint "eagle-import:R1206")
      (libsource (lib "eagle-import") (part "R-EU_R1206"))
    )
    (comp (ref "R13")
      (value "31.6k")
      (footprint "eagle-import:R1206")
      (libsource (lib "eagle-import") (part "R-EU_R1206"))
    )
    (comp (ref "R14")
      (value "10.2k")
      (footprint "eagle-import:R1206")
      (libsource (lib "eagle-import") (part "R-EU_R1206"))
    )
    (comp (ref "R15")
      (value "10k")
      (footprint "eagle-import:R1206")
      (libsource (lib "eagle-import") (part "R-EU_R1206"))
    )
    (comp (ref "R16")
      (value "10k")
      (footprint "eagle-import:R1206")
      (libsource (lib "eagle-import") (part "R-EU_R1206"))
    )
    (comp (ref "R17")
      (value "10k")
      (footprint "eagle-import:R1206")
      (libsource (lib "eagle-import") (part "R-EU_R1206"))
    )
    (comp (ref "R18")
      (value "60.4k")
      (footprint "eagle-import:R1206")
      (libsource (lib "eagle-import") (part "R-EU_R1206"))
    )
    (comp (ref "R19")
      (value "1k")
      (footprint "eagle-import:R1206")
      (libsource (lib "eagle-import") (part "R-EU_R1206"))
    )
    (comp (ref "R20")
      (value "1k")
      (footprint "eagle-import:R1206")
      (libsource (lib "eagle-import") (part "R-EU_R1206"))
    )
    (comp (ref "R21")
      (value "100")
      (footprint "eagle-import:R1206")
      (libsource (lib "eagle-import") (part "R-EU_R1206"))
    )
    (comp (ref "R22")
      (value "53.6k")
      (footprint "eagle-import:R1206")
      (libsource (lib "eagle-import") (part "R-EU_R1206"))
    )
    (comp (ref "R23")
      (value "10.2k")
      (footprint "eagle-import:R1206")
      (libsource (lib "eagle-import") (part "R-EU_R1206"))
    )
    (comp (ref "R24")
      (value "300")
      (footprint "eagle-import:R1206")
      (libsource (lib "eagle-import") (part "R-EU_R1206"))
    )
    (comp (ref "R25")
      (value "5000")
      (footprint "eagle-import:R1206")
      (libsource (lib "eagle-import") (part "R-EU_R1206"))
    )
    (comp (ref "R26")
      (value "5000")
      (footprint "eagle-import:R1206")
      (libsource (lib "eagle-import") (part "R-EU_R1206"))
    )
    (comp (ref "R27")
      (value "1M")
      (footprint "eagle-import:R1206")
      (libsource (lib "eagle-import") (part "R-EU_R1206"))
    )
    (comp (ref "R28")
      (value "24")
      (footprint "eagle-import:R1206")
      (libsource (lib "eagle-import") (part "R-EU_R1206"))
    )
    (comp (ref "R29")
      (value "24")
      (footprint "eagle-import:R1206")
      (libsource (lib "eagle-import") (part "R-EU_R1206"))
    )
    (comp (ref "R30")
      (value "24")
      (footprint "eagle-import:R1206")
      (libsource (lib "eagle-import") (part "R-EU_R1206"))
    )
    (comp (ref "R31")
      (value "24")
      (footprint "eagle-import:R1206")
      (libsource (lib "eagle-import") (part "R-EU_R1206"))
    )
    (comp (ref "R32")
      (value "5000")
      (footprint "eagle-import:R1206")
      (libsource (lib "eagle-import") (part "R-EU_R1206"))
    )
    (comp (ref "R33")
      (value "5000")
      (footprint "eagle-import:R1206")
      (libsource (lib "eagle-import") (part "R-EU_R1206"))
    )
    (comp (ref "R34")
      (value "1k")
      (footprint "eagle-import:R1206")
      (libsource (lib "eagle-import") (part "R-EU_R1206"))
    )
    (comp (ref "R35")
      (value "12k")
      (footprint "eagle-import:R1206")
      (libsource (lib "eagle-import") (part "R-EU_R1206"))
    )
    (comp (ref "R36")
      (value "INDUCTOR-AISC-0603-R0082-J-T-1628488")
      (footprint "eagle-import:R0603")
      (libsource (lib "eagle-import") (part "R-EU_R0603"))
    )
    (comp (ref "R37")
      (value "INDUCTOR-AISC-0603-R0082-J-T-1628488")
      (footprint "eagle-import:R0603")
      (libsource (lib "eagle-import") (part "R-EU_R0603"))
    )
    (comp (ref "R38")
      (value "100")
      (footprint "eagle-import:R1206")
      (libsource (lib "eagle-import") (part "R-EU_R1206"))
    )
    (comp (ref "R39")
      (value "1M")
      (footprint "eagle-import:R1206")
      (libsource (lib "eagle-import") (part "R-EU_R1206"))
    )
    (comp (ref "R40")
      (value "10k")
      (footprint "eagle-import:R1206")
      (libsource (lib "eagle-import") (part "R-EU_R1206"))
    )
    (comp (ref "R41")
      (value "10k")
      (footprint "eagle-import:R1206")
      (libsource (lib "eagle-import") (part "R-EU_R1206"))
    )
    (comp (ref "R42")
      (value "10k")
      (footprint "eagle-import:R1206")
      (libsource (lib "eagle-import") (part "R-EU_R1206"))
    )
    (comp (ref "R43")
      (value "10k")
      (footprint "eagle-import:R1206")
      (libsource (lib "eagle-import") (part "R-EU_R1206"))
    )
    (comp (ref "R44")
      (value "10k")
      (footprint "eagle-import:R1206")
      (libsource (lib "eagle-import") (part "R-EU_R1206"))
    )
    (comp (ref "R45")
      (value "10k")
      (footprint "eagle-import:R1206")
      (libsource (lib "eagle-import") (part "R-EU_R1206"))
    )
    (comp (ref "R46")
      (value "10k")
      (footprint "eagle-import:R1206")
      (libsource (lib "eagle-import") (part "R-EU_R1206"))
    )
    (comp (ref "R47")
      (value "10k")
      (footprint "eagle-import:R1206")
      (libsource (lib "eagle-import") (part "R-EU_R1206"))
    )
    (comp (ref "R48")
      (value "10k")
      (footprint "eagle-import:R1206")
      (libsource (lib "eagle-import") (part "R-EU_R1206"))
    )
    (comp (ref "R49")
      (value "10k")
      (footprint "eagle-import:R1206")
      (libsource (lib "eagle-import") (part "R-EU_R1206"))
    )
    (comp (ref "R50")
      (value "100")
      (footprint "eagle-import:R1206")
      (libsource (lib "eagle-import") (part "R-EU_R1206"))
    )
    (comp (ref "R51")
      (value "100")
      (footprint "eagle-import:R1206")
      (libsource (lib "eagle-import") (part "R-EU_R1206"))
    )
    (comp (ref "R52")
      (value "1k8")
      (footprint "eagle-import:R1206")
      (libsource (lib "eagle-import") (part "R-EU_R1206"))
    )
    (comp (ref "R53")
      (value "1k8")
      (footprint "eagle-import:R1206")
      (libsource (lib "eagle-import") (part "R-EU_R1206"))
    )
    (comp (ref "R54")
      (value "300")
      (footprint "eagle-import:R1206")
      (libsource (lib "eagle-import") (part "R-EU_R1206"))
    )
    (comp (ref "R55")
      (value "300")
      (footprint "eagle-import:R1206")
      (libsource (lib "eagle-import") (part "R-EU_R1206"))
    )
    (comp (ref "R56")
      (value "300")
      (footprint "eagle-import:R1206")
      (libsource (lib "eagle-import") (part "R-EU_R1206"))
    )
    (comp (ref "R57")
      (value "300")
      (footprint "eagle-import:R1206")
      (libsource (lib "eagle-import") (part "R-EU_R1206"))
    )
    (comp (ref "R58")
      (value "5000")
      (footprint "eagle-import:R1206")
      (libsource (lib "eagle-import") (part "R-EU_R1206"))
    )
    (comp (ref "R59")
      (value "5000")
      (footprint "eagle-import:R1206")
      (libsource (lib "eagle-import") (part "R-EU_R1206"))
    )
    (comp (ref "R60")
      (value "R-EU_R1206")
      (footprint "eagle-import:R1206")
      (libsource (lib "eagle-import") (part "R-EU_R1206"))
    )
    (comp (ref "R61")
      (value "R-EU_R1206")
      (footprint "eagle-import:R1206")
      (libsource (lib "eagle-import") (part "R-EU_R1206"))
    )
    (comp (ref "R62")
      (value "5000")
      (footprint "eagle-import:R1206")
      (libsource (lib "eagle-import") (part "R-EU_R1206"))
    )
    (comp (ref "R63")
      (value "5000")
      (footprint "eagle-import:R1206")
      (libsource (lib "eagle-import") (part "R-EU_R1206"))
    )
    (comp (ref "R64")
      (value "R-EU_R1206")
      (footprint "eagle-import:R1206")
      (libsource (lib "eagle-import") (part "R-EU_R1206"))
    )
    (comp (ref "R65")
      (value "R-EU_R1206")
      (footprint "eagle-import:R1206")
      (libsource (lib "eagle-import") (part "R-EU_R1206"))
    )
    (comp (ref "R66")
      (value "31.6k")
      (footprint "eagle-import:R1206")
      (libsource (lib "eagle-import") (part "R-EU_R1206"))
    )
    (comp (ref "R67")
      (value "10.2k")
      (footprint "eagle-import:R1206")
      (libsource (lib "eagle-import") (part "R-EU_R1206"))
    )
    (comp (ref "R68")
      (value "60.4k")
      (footprint "eagle-import:R1206")
      (libsource (lib "eagle-import") (part "R-EU_R1206"))
    )
    (comp (ref "R69")
      (value "53.6k")
      (footprint "eagle-import:R1206")
      (libsource (lib "eagle-import") (part "R-EU_R1206"))
    )
    (comp (ref "R70")
      (value "10.2k")
      (footprint "eagle-import:R1206")
      (libsource (lib "eagle-import") (part "R-EU_R1206"))
    )
    (comp (ref "SW1")
      (value "RESET")
      (footprint "eagle-import:MC32829")
      (libsource (lib "eagle-import") (part "MC32829"))
    )
    (comp (ref "SW2")
      (value "INT1")
      (footprint "eagle-import:MC32829")
      (libsource (lib "eagle-import") (part "MC32829"))
    )
    (comp (ref "SW3")
      (value "INT2")
      (footprint "eagle-import:MC32829")
      (libsource (lib "eagle-import") (part "MC32829"))
    )
    (comp (ref "U$1")
      (value "USB-MINIB-5PIN")
      (footprint "eagle-import:USB-MINIB")
      (libsource (lib "eagle-import") (part "USB-MINIB-5PIN"))
    )
    (comp (ref "U$2")
      (value "ABMM2-12.000MHZ-E2-T")
      (footprint "eagle-import:ABMM2-16.000MHZ-E2-T")
      (libsource (lib "eagle-import") (part "ABMM2-16.000MHZ-E2-T"))
    )
    (comp (ref "U$5")
      (value "USB-MINIB-5PIN")
      (footprint "eagle-import:USB-MINIB")
      (libsource (lib "eagle-import") (part "USB-MINIB-5PIN"))
    )
    (comp (ref "U$6")
      (value "ABMM2-12.000MHZ-E2-T")
      (footprint "eagle-import:ABMM2-16.000MHZ-E2-T")
      (libsource (lib "eagle-import") (part "ABMM2-16.000MHZ-E2-T"))
    )
    (comp (ref "U$7")
      (value "ABMM2-16.000MHZ-E2-T")
      (footprint "eagle-import:ABMM2-16.000MHZ-E2-T")
      (libsource (lib "eagle-import") (part "ABMM2-16.000MHZ-E2-T"))
    )
    (comp (ref "U$8")
      (value "LTC4416")
      (footprint "eagle-import:LTC4416")
      (libsource (lib "eagle-import") (part "LTC4416"))
    )
    (comp (ref "U$9")
      (value "IRF9310PBF")
      (footprint "eagle-import:IRF9310PBF")
      (libsource (lib "eagle-import") (part "IRF9310PBF"))
    )
    (comp (ref "U$10")
      (value "IRF9310PBF")
      (footprint "eagle-import:IRF9310PBF")
      (libsource (lib "eagle-import") (part "IRF9310PBF"))
    )
    (comp (ref "U$11")
      (value "LTC4416")
      (footprint "eagle-import:LTC4416")
      (libsource (lib "eagle-import") (part "LTC4416"))
    )
    (comp (ref "U$12")
      (value "LTC4416")
      (footprint "eagle-import:LTC4416")
      (libsource (lib "eagle-import") (part "LTC4416"))
    )
    (comp (ref "U$13")
      (value "LTC4416")
      (footprint "eagle-import:LTC4416")
      (libsource (lib "eagle-import") (part "LTC4416"))
    )
    (comp (ref "U$14")
      (value "IRF9310PBF")
      (footprint "eagle-import:IRF9310PBF")
      (libsource (lib "eagle-import") (part "IRF9310PBF"))
    )
    (comp (ref "U$15")
      (value "IRF9310PBF")
      (footprint "eagle-import:IRF9310PBF")
      (libsource (lib "eagle-import") (part "IRF9310PBF"))
    )
    (comp (ref "U$16")
      (value "IRF9310PBF")
      (footprint "eagle-import:IRF9310PBF")
      (libsource (lib "eagle-import") (part "IRF9310PBF"))
    )
    (comp (ref "U$17")
      (value "IRF9310PBF")
      (footprint "eagle-import:IRF9310PBF")
      (libsource (lib "eagle-import") (part "IRF9310PBF"))
    )
    (comp (ref "U$18")
      (value "IRF9310PBF")
      (footprint "eagle-import:IRF9310PBF")
      (libsource (lib "eagle-import") (part "IRF9310PBF"))
    )
    (comp (ref "U$19")
      (value "IRF9310PBF")
      (footprint "eagle-import:IRF9310PBF")
      (libsource (lib "eagle-import") (part "IRF9310PBF"))
    )
    (comp (ref "U$20")
      (value "IRF9310PBF")
      (footprint "eagle-import:IRF9310PBF")
      (libsource (lib "eagle-import") (part "IRF9310PBF"))
    )
    (comp (ref "U$21")
      (value "IRF9310PBF")
      (footprint "eagle-import:IRF9310PBF")
      (libsource (lib "eagle-import") (part "IRF9310PBF"))
    )
    (comp (ref "U$22")
      (value "IRF9310PBF")
      (footprint "eagle-import:IRF9310PBF")
      (libsource (lib "eagle-import") (part "IRF9310PBF"))
    )
    (comp (ref "U$23")
      (value "IRF9310PBF")
      (footprint "eagle-import:IRF9310PBF")
      (libsource (lib "eagle-import") (part "IRF9310PBF"))
    )
    (comp (ref "U$24")
      (value "IRF9310PBF")
      (footprint "eagle-import:IRF9310PBF")
      (libsource (lib "eagle-import") (part "IRF9310PBF"))
    )
    (comp (ref "U$25")
      (value "IRF9310PBF")
      (footprint "eagle-import:IRF9310PBF")
      (libsource (lib "eagle-import") (part "IRF9310PBF"))
    )
    (comp (ref "U$26")
      (value "IRF9310PBF")
      (footprint "eagle-import:IRF9310PBF")
      (libsource (lib "eagle-import") (part "IRF9310PBF"))
    )
    (comp (ref "U$27")
      (value "IRF9310PBF")
      (footprint "eagle-import:IRF9310PBF")
      (libsource (lib "eagle-import") (part "IRF9310PBF"))
    )
    (comp (ref "U1")
      (value "ADUM3160BRWZ")
      (footprint "eagle-import:SOIC127P1032X265-16N")
      (libsource (lib "eagle-import") (part "ADUM3160BRWZ"))
    )
    (comp (ref "U2")
      (value "CAT93C46WI-GT3-1718152-EEPROM")
      (footprint "eagle-import:SO08")
      (libsource (lib "eagle-import") (part "CAT93C46WI-GT3-1718152-EEPROM"))
    )
    (comp (ref "U3")
      (value "LT3509EMSEPBF")
      (footprint "eagle-import:SOP50P490X110-17N")
      (fields (field (name "MPN") "LT3509EMSE#PBF"))
      (libsource (lib "eagle-import") (part "LT3509EMSEPBF"))
    )
    (comp (ref "U4")
      (value "ISO7221ADR-1575146")
      (footprint "eagle-import:SO08")
      (libsource (lib "eagle-import") (part "TI-ISO7221"))
    )
    (comp (ref "U5")
      (value "ISO7221ADR-1575146")
      (footprint "eagle-import:SO08")
      (libsource (lib "eagle-import") (part "TI-ISO7221"))
    )
    (comp (ref "U6")
      (value "ISO7221ADR-1575146")
      (footprint "eagle-import:SO08")
      (libsource (lib "eagle-import") (part "TI-ISO7221"))
    )
    (comp (ref "U7")
      (value "PS2701A-1-F3-A-1682859RL")
      (footprint "eagle-import:PS2701A-1-F3-A-1682859RL")
      (libsource (lib "eagle-import") (part "PS2701A-1-F3-A-1682859RL"))
    )
    (comp (ref "U8")
      (value "ADUM3160BRWZ")
      (footprint "eagle-import:SOIC127P1032X265-16N")
      (libsource (lib "eagle-import") (part "ADUM3160BRWZ"))
    )
    (comp (ref "U9")
      (value "MPL115A2-OR-MPL115A2T1")
      (footprint "eagle-import:MPL115A2-OR-MPL115A2T1")
      (libsource (lib "eagle-import") (part "MPL115A2-OR-MPL115A2T1"))
    )
    (comp (ref "U10")
      (value "CAT93C46WI-GT3-1718152-EEPROM")
      (footprint "eagle-import:SO08")
      (libsource (lib "eagle-import") (part "CAT93C46WI-GT3-1718152-EEPROM"))
    )
    (comp (ref "U11")
      (value "ATMEGA328P-AU")
      (footprint "eagle-import:QFP80P900X900X120-32N")
      (libsource (lib "eagle-import") (part "ATMEGA328P-AU"))
    )
    (comp (ref "U12")
      (value "ISO7221ADR-1575146")
      (footprint "eagle-import:SO08")
      (libsource (lib "eagle-import") (part "TI-ISO7221"))
    )
    (comp (ref "U13")
      (value "ISO7221ADR-1575146")
      (footprint "eagle-import:SO08")
      (libsource (lib "eagle-import") (part "TI-ISO7221"))
    )
    (comp (ref "U14")
      (value "ISO7221ADR-1575146")
      (footprint "eagle-import:SO08")
      (libsource (lib "eagle-import") (part "TI-ISO7221"))
    )
    (comp (ref "U15")
      (value "ISO7221ADR-1575146")
      (footprint "eagle-import:SO08")
      (libsource (lib "eagle-import") (part "TI-ISO7221"))
    )
    (comp (ref "U16")
      (value "TPS5450DDARG4")
      (footprint "eagle-import:SOIC127P600X170-9N")
      (libsource (lib "eagle-import") (part "TPS5450DDARG4"))
    )
    (comp (ref "U17")
      (value "TPS5450DDARG4")
      (footprint "eagle-import:SOIC127P600X170-9N")
      (libsource (lib "eagle-import") (part "TPS5450DDARG4"))
    )
    (comp (ref "U18")
      (value "LT3509EMSEPBF")
      (footprint "eagle-import:SOP50P490X110-17N")
      (fields (field (name "MPN") "LT3509EMSE#PBF"))
      (libsource (lib "eagle-import") (part "LT3509EMSEPBF"))
    )
  )
  (nets
    (net (code "1") (name "/+1.8_A") (class "Default")
      (node (ref "C7") (pin "2") (pinfunction "2_2") (pintype "passive"))
      (node (ref "IC1") (pin "12") (pinfunction "VCORE_12") (pintype "input"))
      (node (ref "IC1") (pin "37") (pinfunction "VCORE_37") (pintype "input"))
      (node (ref "IC1") (pin "50") (pinfunction "VREGIN_50") (pintype "bidirectional"))
      (node (ref "IC1") (pin "64") (pinfunction "VCORE_64") (pintype "input"))
    )
    (net (code "2") (name "/+1.8_B") (class "Default")
      (node (ref "C30") (pin "2") (pinfunction "2_2") (pintype "passive"))
      (node (ref "IC2") (pin "12") (pinfunction "VCORE_12") (pintype "input"))
      (node (ref "IC2") (pin "37") (pinfunction "VCORE_37") (pintype "input"))
      (node (ref "IC2") (pin "50") (pinfunction "VREGIN_50") (pintype "bidirectional"))
      (node (ref "IC2") (pin "64") (pinfunction "VCORE_64") (pintype "input"))
    )
    (net (code "3") (name "/+3.3_A") (class "Default")
      (node (ref "C11") (pin "P$1") (pinfunction "P$1_P$1") (pintype "bidirectional"))
      (node (ref "C12") (pin "2") (pinfunction "2_2") (pintype "passive"))
      (node (ref "C8") (pin "2") (pinfunction "2_2") (pintype "passive"))
      (node (ref "IC1") (pin "20") (pinfunction "VCCIO_20") (pintype "input"))
      (node (ref "IC1") (pin "31") (pinfunction "VCCIO_31") (pintype "input"))
      (node (ref "IC1") (pin "42") (pinfunction "VCCIO_42") (pintype "input"))
      (node (ref "IC1") (pin "49") (pinfunction "VREGOUT_49") (pintype "output"))
      (node (ref "IC1") (pin "56") (pinfunction "VCCIO_56") (pintype "input"))
      (node (ref "L1") (pin "1") (pinfunction "P$1_1") (pintype "bidirectional"))
      (node (ref "LED2") (pin "A") (pinfunction "A_A") (pintype "passive"))
      (node (ref "R10") (pin "1") (pinfunction "1_1") (pintype "passive"))
      (node (ref "R12") (pin "1") (pinfunction "1_1") (pintype "passive"))
      (node (ref "R13") (pin "1") (pinfunction "1_1") (pintype "passive"))
      (node (ref "R16") (pin "1") (pinfunction "1_1") (pintype "passive"))
      (node (ref "R17") (pin "1") (pinfunction "1_1") (pintype "passive"))
      (node (ref "R7") (pin "1") (pinfunction "1_1") (pintype "passive"))
      (node (ref "R9") (pin "1") (pinfunction "1_1") (pintype "passive"))
      (node (ref "U2") (pin "2") (pinfunction "VCC_2") (pintype "bidirectional"))
      (node (ref "U2") (pin "8") (pinfunction "ORG_8") (pintype "bidirectional"))
    )
    (net (code "4") (name "/+3.3_B") (class "Default")
      (node (ref "C31") (pin "2") (pinfunction "2_2") (pintype "passive"))
      (node (ref "C55") (pin "2") (pinfunction "2_2") (pintype "passive"))
      (node (ref "IC2") (pin "20") (pinfunction "VCCIO_20") (pintype "input"))
      (node (ref "IC2") (pin "31") (pinfunction "VCCIO_31") (pintype "input"))
      (node (ref "IC2") (pin "42") (pinfunction "VCCIO_42") (pintype "input"))
      (node (ref "IC2") (pin "49") (pinfunction "VREGOUT_49") (pintype "output"))
      (node (ref "IC2") (pin "56") (pinfunction "VCCIO_56") (pintype "input"))
      (node (ref "L5") (pin "1") (pinfunction "P$1_1") (pintype "bidirectional"))
      (node (ref "R34") (pin "1") (pinfunction "1_1") (pintype "passive"))
      (node (ref "R36") (pin "1") (pinfunction "1_1") (pintype "passive"))
      (node (ref "R37") (pin "1") (pinfunction "1_1") (pintype "passive"))
      (node (ref "R46") (pin "1") (pinfunction "1_1") (pintype "passive"))
      (node (ref "R48") (pin "1") (pinfunction "1_1") (pintype "passive"))
      (node (ref "R49") (pin "1") (pinfunction "1_1") (pintype "passive"))
      (node (ref "R66") (pin "1") (pinfunction "1_1") (pintype "passive"))
      (node (ref "U10") (pin "2") (pinfunction "VCC_2") (pintype "bidirectional"))
      (node (ref "U10") (pin "8") (pinfunction "ORG_8") (pintype "bidirectional"))
    )
    (net (code "5") (name "/+5V_A") (class "Default")
      (node (ref "C18") (pin "2") (pinfunction "2_2") (pintype "passive"))
      (node (ref "C19") (pin "2") (pinfunction "2_2") (pintype "passive"))
      (node (ref "C20") (pin "P$1") (pinfunction "P$1_P$1") (pintype "bidirectional"))
      (node (ref "C4") (pin "2") (pinfunction "2_2") (pintype "passive"))
      (node (ref "C40") (pin "1") (pinfunction "1_1") (pintype "passive"))
      (node (ref "JP10") (pin "2") (pinfunction "2_2") (pintype "passive"))
      (node (ref "JP6") (pin "3") (pinfunction "3_3") (pintype "passive"))
      (node (ref "JP8") (pin "2") (pinfunction "2_2") (pintype "passive"))
      (node (ref "JP9") (pin "3") (pinfunction "3_3") (pintype "passive"))
      (node (ref "JP9") (pin "5") (pinfunction "5_5") (pintype "passive"))
      (node (ref "L2") (pin "2") (pinfunction "P$2_2") (pintype "bidirectional"))
      (node (ref "LED3") (pin "A") (pinfunction "A_A") (pintype "passive"))
      (node (ref "R22") (pin "1") (pinfunction "1_1") (pintype "passive"))
      (node (ref "R38") (pin "2") (pinfunction "2_2") (pintype "passive"))
      (node (ref "R40") (pin "1") (pinfunction "1_1") (pintype "passive"))
      (node (ref "R42") (pin "1") (pinfunction "1_1") (pintype "passive"))
      (node (ref "R44") (pin "1") (pinfunction "1_1") (pintype "passive"))
      (node (ref "R52") (pin "2") (pinfunction "2_2") (pintype "passive"))
      (node (ref "R53") (pin "2") (pinfunction "2_2") (pintype "passive"))
      (node (ref "SW2") (pin "P$1") (pinfunction "P$1_P$1") (pintype "bidirectional"))
      (node (ref "SW2") (pin "P$4") (pinfunction "P$1_P$4") (pintype "bidirectional"))
      (node (ref "SW3") (pin "P$1") (pinfunction "P$1_P$1") (pintype "bidirectional"))
      (node (ref "SW3") (pin "P$4") (pinfunction "P$1_P$4") (pintype "bidirectional"))
      (node (ref "U1") (pin "16") (pinfunction "VBUS2_16") (pintype "bidirectional"))
      (node (ref "U11") (pin "18") (pinfunction "AVCC_18") (pintype "power_in"))
      (node (ref "U11") (pin "4") (pinfunction "VCC_2_4") (pintype "power_in"))
      (node (ref "U11") (pin "6") (pinfunction "VCC_6") (pintype "power_in"))
      (node (ref "U3") (pin "13") (pinfunction "BD_13") (pintype "input"))
      (node (ref "U4") (pin "1") (pinfunction "VCC1_1") (pintype "bidirectional"))
      (node (ref "U4") (pin "8") (pinfunction "VCC2_8") (pintype "bidirectional"))
      (node (ref "U5") (pin "1") (pinfunction "VCC1_1") (pintype "bidirectional"))
      (node (ref "U5") (pin "8") (pinfunction "VCC2_8") (pintype "bidirectional"))
      (node (ref "U6") (pin "1") (pinfunction "VCC1_1") (pintype "bidirectional"))
      (node (ref "U6") (pin "8") (pinfunction "VCC2_8") (pintype "bidirectional"))
      (node (ref "U9") (pin "P$1") (pinfunction "VDD_P$1") (pintype "bidirectional"))
      (node (ref "U9") (pin "P$4") (pinfunction "SHDN_P$4") (pintype "bidirectional"))
      (node (ref "U9") (pin "P$5") (pinfunction "RST_P$5") (pintype "bidirectional"))
    )
    (net (code "6") (name "/+5V_B") (class "Default")
      (node (ref "C24") (pin "2") (pinfunction "2_2") (pintype "passive"))
      (node (ref "C61") (pin "2") (pinfunction "2_2") (pintype "passive"))
      (node (ref "L6") (pin "2") (pinfunction "P$2_2") (pintype "bidirectional"))
      (node (ref "R69") (pin "1") (pinfunction "1_1") (pintype "passive"))
      (node (ref "U$8") (pin "P$2") (pinfunction "E1_P$2") (pintype "bidirectional"))
      (node (ref "U12") (pin "1") (pinfunction "VCC1_1") (pintype "bidirectional"))
      (node (ref "U12") (pin "8") (pinfunction "VCC2_8") (pintype "bidirectional"))
      (node (ref "U13") (pin "1") (pinfunction "VCC1_1") (pintype "bidirectional"))
      (node (ref "U13") (pin "8") (pinfunction "VCC2_8") (pintype "bidirectional"))
      (node (ref "U14") (pin "1") (pinfunction "VCC1_1") (pintype "bidirectional"))
      (node (ref "U14") (pin "8") (pinfunction "VCC2_8") (pintype "bidirectional"))
      (node (ref "U15") (pin "1") (pinfunction "VCC1_1") (pintype "bidirectional"))
      (node (ref "U15") (pin "8") (pinfunction "VCC2_8") (pintype "bidirectional"))
      (node (ref "U18") (pin "13") (pinfunction "BD_13") (pintype "input"))
      (node (ref "U8") (pin "16") (pinfunction "VBUS2_16") (pintype "bidirectional"))
    )
    (net (code "7") (name "/A0") (class "Default")
      (node (ref "LED8") (pin "A") (pinfunction "A_A") (pintype "passive"))
      (node (ref "U11") (pin "23") (pinfunction "PC0_23") (pintype "bidirectional"))
    )
    (net (code "8") (name "/A1") (class "Default")
      (node (ref "LED9") (pin "A") (pinfunction "A_A") (pintype "passive"))
      (node (ref "U11") (pin "24") (pinfunction "PC1_24") (pintype "bidirectional"))
    )
    (net (code "9") (name "/A2") (class "Default")
      (node (ref "LED10") (pin "A") (pinfunction "A_A") (pintype "passive"))
      (node (ref "U11") (pin "25") (pinfunction "PC2_25") (pintype "bidirectional"))
    )
    (net (code "10") (name "/A3") (class "Default")
      (node (ref "LED11") (pin "A") (pinfunction "A_A") (pintype "passive"))
      (node (ref "U11") (pin "26") (pinfunction "PC3_26") (pintype "bidirectional"))
    )
    (net (code "11") (name "/A4{slash}SDA") (class "Default")
      (node (ref "JP8") (pin "3") (pinfunction "3_3") (pintype "passive"))
      (node (ref "R52") (pin "1") (pinfunction "1_1") (pintype "passive"))
      (node (ref "U11") (pin "27") (pinfunction "PC4_27") (pintype "bidirectional"))
      (node (ref "U9") (pin "P$7") (pinfunction "SDA_P$7") (pintype "bidirectional"))
    )
    (net (code "12") (name "/A5{slash}SCL") (class "Default")
      (node (ref "JP8") (pin "4") (pinfunction "4_4") (pintype "passive"))
      (node (ref "R53") (pin "1") (pinfunction "1_1") (pintype "passive"))
      (node (ref "U11") (pin "28") (pinfunction "PC5_28") (pintype "bidirectional"))
      (node (ref "U9") (pin "P$8") (pinfunction "SCL_P$8") (pintype "bidirectional"))
    )
    (net (code "13") (name "/A6") (class "Default")
      (node (ref "U11") (pin "19") (pinfunction "ADC6_19") (pintype "input"))
    )
    (net (code "14") (name "/A7") (class "Default")
      (node (ref "U11") (pin "22") (pinfunction "ADC7_22") (pintype "input"))
    )
    (net (code "15") (name "/D0{slash}RXI") (class "Default")
      (node (ref "JP6") (pin "4") (pinfunction "4_4") (pintype "passive"))
      (node (ref "R19") (pin "1") (pinfunction "1_1") (pintype "passive"))
      (node (ref "U11") (pin "30") (pinfunction "PD0_30") (pintype "bidirectional"))
    )
    (net (code "16") (name "/D1{slash}TXO") (class "Default")
      (node (ref "JP6") (pin "5") (pinfunction "5_5") (pintype "passive"))
      (node (ref "R20") (pin "1") (pinfunction "1_1") (pintype "passive"))
      (node (ref "U11") (pin "31") (pinfunction "PD1_31") (pintype "bidirectional"))
    )
    (net (code "17") (name "/D2") (class "Default")
      (node (ref "JP9") (pin "4") (pinfunction "4_4") (pintype "passive"))
      (node (ref "R50") (pin "1") (pinfunction "1_1") (pintype "passive"))
      (node (ref "SW2") (pin "P$2") (pinfunction "P$2_P$2") (pintype "bidirectional"))
      (node (ref "SW2") (pin "P$3") (pinfunction "P$2_P$3") (pintype "bidirectional"))
      (node (ref "U11") (pin "32") (pinfunction "PD2_32") (pintype "bidirectional"))
    )
    (net (code "18") (name "/D3") (class "Default")
      (node (ref "JP9") (pin "6") (pinfunction "6_6") (pintype "passive"))
      (node (ref "R51") (pin "1") (pinfunction "1_1") (pintype "passive"))
      (node (ref "SW3") (pin "P$2") (pinfunction "P$2_P$2") (pintype "bidirectional"))
      (node (ref "SW3") (pin "P$3") (pinfunction "P$2_P$3") (pintype "bidirectional"))
      (node (ref "U11") (pin "1") (pinfunction "PD3_1") (pintype "bidirectional"))
    )
    (net (code "19") (name "/D4") (class "Default")
      (node (ref "R41") (pin "2") (pinfunction "2_2") (pintype "passive"))
      (node (ref "U$11") (pin "P$4") (pinfunction "E2_P$4") (pintype "bidirectional"))
      (node (ref "U11") (pin "2") (pinfunction "PD4_2") (pintype "bidirectional"))
    )
    (net (code "20") (name "/D5") (class "Default")
      (node (ref "R40") (pin "2") (pinfunction "2_2") (pintype "passive"))
      (node (ref "U$11") (pin "P$2") (pinfunction "E1_P$2") (pintype "bidirectional"))
      (node (ref "U11") (pin "9") (pinfunction "PD5_9") (pintype "bidirectional"))
    )
    (net (code "21") (name "/D6") (class "Default")
      (node (ref "R45") (pin "2") (pinfunction "2_2") (pintype "passive"))
      (node (ref "U$13") (pin "P$4") (pinfunction "E2_P$4") (pintype "bidirectional"))
      (node (ref "U11") (pin "10") (pinfunction "PD6_10") (pintype "bidirectional"))
    )
    (net (code "22") (name "/D7") (class "Default")
      (node (ref "R44") (pin "2") (pinfunction "2_2") (pintype "passive"))
      (node (ref "U$13") (pin "P$2") (pinfunction "E1_P$2") (pintype "bidirectional"))
      (node (ref "U11") (pin "11") (pinfunction "PD7_11") (pintype "bidirectional"))
    )
    (net (code "23") (name "/D8") (class "Default")
      (node (ref "R43") (pin "2") (pinfunction "2_2") (pintype "passive"))
      (node (ref "U$12") (pin "P$4") (pinfunction "E2_P$4") (pintype "bidirectional"))
      (node (ref "U11") (pin "12") (pinfunction "PB0_12") (pintype "bidirectional"))
    )
    (net (code "24") (name "/D9") (class "Default")
      (node (ref "R42") (pin "2") (pinfunction "2_2") (pintype "passive"))
      (node (ref "U$12") (pin "P$2") (pinfunction "E1_P$2") (pintype "bidirectional"))
      (node (ref "U11") (pin "13") (pinfunction "PB1_13") (pintype "bidirectional"))
    )
    (net (code "25") (name "/D10") (class "Default")
      (node (ref "U11") (pin "14") (pinfunction "PB2_14") (pintype "bidirectional"))
      (node (ref "U7") (pin "P$1") (pinfunction "P$1_P$1") (pintype "bidirectional"))
    )
    (net (code "26") (name "/DTR") (class "Default")
      (node (ref "C36") (pin "1") (pinfunction "1_1") (pintype "passive"))
      (node (ref "IC1") (pin "55") (pinfunction "DB4/DTR_55") (pintype "bidirectional"))
      (node (ref "JP6") (pin "6") (pinfunction "6_6") (pintype "passive"))
    )
    (net (code "27") (name "/EECLK_A") (class "Default")
      (node (ref "IC1") (pin "62") (pinfunction "EECLK_62") (pintype "output"))
      (node (ref "R17") (pin "2") (pinfunction "2_2") (pintype "passive"))
      (node (ref "U2") (pin "4") (pinfunction "SK_4") (pintype "bidirectional"))
    )
    (net (code "28") (name "/EECLK_B") (class "Default")
      (node (ref "IC2") (pin "62") (pinfunction "EECLK_62") (pintype "output"))
      (node (ref "R49") (pin "2") (pinfunction "2_2") (pintype "passive"))
      (node (ref "U10") (pin "4") (pinfunction "SK_4") (pintype "bidirectional"))
    )
    (net (code "29") (name "/EECS_A") (class "Default")
      (node (ref "IC1") (pin "63") (pinfunction "EECS_63") (pintype "bidirectional"))
      (node (ref "R16") (pin "2") (pinfunction "2_2") (pintype "passive"))
      (node (ref "U2") (pin "3") (pinfunction "CS_3") (pintype "bidirectional"))
    )
    (net (code "30") (name "/EECS_B") (class "Default")
      (node (ref "IC2") (pin "63") (pinfunction "EECS_63") (pintype "bidirectional"))
      (node (ref "R48") (pin "2") (pinfunction "2_2") (pintype "passive"))
      (node (ref "U10") (pin "3") (pinfunction "CS_3") (pintype "bidirectional"))
    )
    (net (code "31") (name "/EEDATA_A") (class "Default")
      (node (ref "IC1") (pin "61") (pinfunction "EEDATA_61") (pintype "bidirectional"))
      (node (ref "R15") (pin "1") (pinfunction "1_1") (pintype "passive"))
      (node (ref "U2") (pin "6") (pinfunction "DO_6") (pintype "bidirectional"))
    )
    (net (code "32") (name "/EEDATA_B") (class "Default")
      (node (ref "IC2") (pin "61") (pinfunction "EEDATA_61") (pintype "bidirectional"))
      (node (ref "R47") (pin "1") (pinfunction "1_1") (pintype "passive"))
      (node (ref "U10") (pin "6") (pinfunction "DO_6") (pintype "bidirectional"))
    )
    (net (code "33") (name "/GND_A") (class "Default")
      (node (ref "C10") (pin "1") (pinfunction "1_1") (pintype "passive"))
      (node (ref "C11") (pin "P$2") (pinfunction "P$2_P$2") (pintype "bidirectional"))
      (node (ref "C12") (pin "1") (pinfunction "1_1") (pintype "passive"))
      (node (ref "C13") (pin "1") (pinfunction "1_1") (pintype "passive"))
      (node (ref "C14") (pin "1") (pinfunction "1_1") (pintype "passive"))
      (node (ref "C17") (pin "1") (pinfunction "1_1") (pintype "passive"))
      (node (ref "C18") (pin "1") (pinfunction "1_1") (pintype "passive"))
      (node (ref "C19") (pin "1") (pinfunction "1_1") (pintype "passive"))
      (node (ref "C20") (pin "P$2") (pinfunction "P$2_P$2") (pintype "bidirectional"))
      (node (ref "C29") (pin "1") (pinfunction "1_1") (pintype "passive"))
      (node (ref "C3") (pin "1") (pinfunction "1_1") (pintype "passive"))
      (node (ref "C37") (pin "1") (pinfunction "1_1") (pintype "passive"))
      (node (ref "C38") (pin "1") (pinfunction "1_1") (pintype "passive"))
      (node (ref "C39") (pin "2") (pinfunction "2_2") (pintype "passive"))
      (node (ref "C4") (pin "1") (pinfunction "1_1") (pintype "passive"))
      (node (ref "C40") (pin "2") (pinfunction "2_2") (pintype "passive"))
      (node (ref "C5") (pin "1") (pinfunction "1_1") (pintype "passive"))
      (node (ref "C6") (pin "1") (pinfunction "1_1") (pintype "passive"))
      (node (ref "C7") (pin "1") (pinfunction "1_1") (pintype "passive"))
      (node (ref "C8") (pin "1") (pinfunction "1_1") (pintype "passive"))
      (node (ref "C9") (pin "1") (pinfunction "1_1") (pintype "passive"))
      (node (ref "F2") (pin "P$2") (pinfunction "P$2_P$2") (pintype "bidirectional"))
      (node (ref "IC1") (pin "1") (pinfunction "GND_1") (pintype "input"))
      (node (ref "IC1") (pin "10") (pinfunction "AGND_10") (pintype "input"))
      (node (ref "IC1") (pin "11") (pinfunction "GND_11") (pintype "input"))
      (node (ref "IC1") (pin "13") (pinfunction "TEST_13") (pintype "input"))
      (node (ref "IC1") (pin "15") (pinfunction "GND_15") (pintype "input"))
      (node (ref "IC1") (pin "25") (pinfunction "GND_25") (pintype "input"))
      (node (ref "IC1") (pin "35") (pinfunction "GND_35") (pintype "input"))
      (node (ref "IC1") (pin "47") (pinfunction "GND_47") (pintype "input"))
      (node (ref "IC1") (pin "5") (pinfunction "GND_5") (pintype "input"))
      (node (ref "IC1") (pin "51") (pinfunction "GND_51") (pintype "input"))
      (node (ref "JP10") (pin "6") (pinfunction "6_6") (pintype "passive"))
      (node (ref "JP6") (pin "1") (pinfunction "1_1") (pintype "passive"))
      (node (ref "JP6") (pin "2") (pinfunction "2_2") (pintype "passive"))
      (node (ref "JP8") (pin "1") (pinfunction "1_1") (pintype "passive"))
      (node (ref "JP9") (pin "1") (pinfunction "1_1") (pintype "passive"))
      (node (ref "R11") (pin "1") (pinfunction "1_1") (pintype "passive"))
      (node (ref "R14") (pin "2") (pinfunction "2_2") (pintype "passive"))
      (node (ref "R18") (pin "2") (pinfunction "2_2") (pintype "passive"))
      (node (ref "R23") (pin "2") (pinfunction "2_2") (pintype "passive"))
      (node (ref "R24") (pin "1") (pinfunction "1_1") (pintype "passive"))
      (node (ref "R41") (pin "1") (pinfunction "1_1") (pintype "passive"))
      (node (ref "R43") (pin "1") (pinfunction "1_1") (pintype "passive"))
      (node (ref "R45") (pin "1") (pinfunction "1_1") (pintype "passive"))
      (node (ref "R50") (pin "2") (pinfunction "2_2") (pintype "passive"))
      (node (ref "R51") (pin "2") (pinfunction "2_2") (pintype "passive"))
      (node (ref "R54") (pin "1") (pinfunction "1_1") (pintype "passive"))
      (node (ref "R55") (pin "1") (pinfunction "1_1") (pintype "passive"))
      (node (ref "R56") (pin "1") (pinfunction "1_1") (pintype "passive"))
      (node (ref "R57") (pin "1") (pinfunction "1_1") (pintype "passive"))
      (node (ref "R8") (pin "1") (pinfunction "1_1") (pintype "passive"))
      (node (ref "SW1") (pin "P$1") (pinfunction "P$1_P$1") (pintype "bidirectional"))
      (node (ref "SW1") (pin "P$4") (pinfunction "P$1_P$4") (pintype "bidirectional"))
      (node (ref "U$2") (pin "P$2") (pinfunction "P$3_P$2") (pintype "bidirectional"))
      (node (ref "U$2") (pin "P$4") (pinfunction "P$3_P$4") (pintype "bidirectional"))
      (node (ref "U$7") (pin "P$2") (pinfunction "P$3_P$2") (pintype "bidirectional"))
      (node (ref "U$7") (pin "P$4") (pinfunction "P$3_P$4") (pintype "bidirectional"))
      (node (ref "U1") (pin "15") (pinfunction "GND2_15") (pintype "passive"))
      (node (ref "U1") (pin "9") (pinfunction "GND2_2_9") (pintype "passive"))
      (node (ref "U11") (pin "21") (pinfunction "GND_21") (pintype "passive"))
      (node (ref "U11") (pin "3") (pinfunction "GND_2_3") (pintype "passive"))
      (node (ref "U11") (pin "5") (pinfunction "GND_3_5") (pintype "passive"))
      (node (ref "U2") (pin "7") (pinfunction "GND_7") (pintype "bidirectional"))
      (node (ref "U3") (pin "12") (pinfunction "SYNC_12") (pintype "input"))
      (node (ref "U3") (pin "14") (pinfunction "AGND_14") (pintype "passive"))
      (node (ref "U3") (pin "17") (pinfunction "EP_17") (pintype "passive"))
      (node (ref "U4") (pin "4") (pinfunction "GND1_4") (pintype "bidirectional"))
      (node (ref "U5") (pin "4") (pinfunction "GND1_4") (pintype "bidirectional"))
      (node (ref "U6") (pin "4") (pinfunction "GND1_4") (pintype "bidirectional"))
      (node (ref "U7") (pin "P$2") (pinfunction "P$2_P$2") (pintype "bidirectional"))
      (node (ref "U9") (pin "P$3") (pinfunction "GND_P$3") (pintype "bidirectional"))
    )
    (net (code "34") (name "/GND_B") (class "Default")
      (node (ref "C23") (pin "1") (pinfunction "1_1") (pintype "passive"))
      (node (ref "C24") (pin "1") (pinfunction "1_1") (pintype "passive"))
      (node (ref "C25") (pin "1") (pinfunction "1_1") (pintype "passive"))
      (node (ref "C26") (pin "1") (pinfunction "1_1") (pintype "passive"))
      (node (ref "C30") (pin "1") (pinfunction "1_1") (pintype "passive"))
      (node (ref "C31") (pin "1") (pinfunction "1_1") (pintype "passive"))
      (node (ref "C34") (pin "1") (pinfunction "1_1") (pintype "passive"))
      (node (ref "C35") (pin "1") (pinfunction "1_1") (pintype "passive"))
      (node (ref "C55") (pin "1") (pinfunction "1_1") (pintype "passive"))
      (node (ref "C56") (pin "1") (pinfunction "1_1") (pintype "passive"))
      (node (ref "C57") (pin "1") (pinfunction "1_1") (pintype "passive"))
      (node (ref "C60") (pin "1") (pinfunction "1_1") (pintype "passive"))
      (node (ref "C61") (pin "1") (pinfunction "1_1") (pintype "passive"))
      (node (ref "F4") (pin "P$2") (pinfunction "P$2_P$2") (pintype "bidirectional"))
      (node (ref "IC2") (pin "1") (pinfunction "GND_1") (pintype "input"))
      (node (ref "IC2") (pin "10") (pinfunction "AGND_10") (pintype "input"))
      (node (ref "IC2") (pin "11") (pinfunction "GND_11") (pintype "input"))
      (node (ref "IC2") (pin "13") (pinfunction "TEST_13") (pintype "input"))
      (node (ref "IC2") (pin "15") (pinfunction "GND_15") (pintype "input"))
      (node (ref "IC2") (pin "25") (pinfunction "GND_25") (pintype "input"))
      (node (ref "IC2") (pin "35") (pinfunction "GND_35") (pintype "input"))
      (node (ref "IC2") (pin "47") (pinfunction "GND_47") (pintype "input"))
      (node (ref "IC2") (pin "5") (pinfunction "GND_5") (pintype "input"))
      (node (ref "IC2") (pin "51") (pinfunction "GND_51") (pintype "input"))
      (node (ref "R35") (pin "1") (pinfunction "1_1") (pintype "passive"))
      (node (ref "R67") (pin "2") (pinfunction "2_2") (pintype "passive"))
      (node (ref "R68") (pin "2") (pinfunction "2_2") (pintype "passive"))
      (node (ref "R70") (pin "2") (pinfunction "2_2") (pintype "passive"))
      (node (ref "U$6") (pin "P$2") (pinfunction "P$3_P$2") (pintype "bidirectional"))
      (node (ref "U$6") (pin "P$4") (pinfunction "P$3_P$4") (pintype "bidirectional"))
      (node (ref "U10") (pin "7") (pinfunction "GND_7") (pintype "bidirectional"))
      (node (ref "U12") (pin "4") (pinfunction "GND1_4") (pintype "bidirectional"))
      (node (ref "U13") (pin "4") (pinfunction "GND1_4") (pintype "bidirectional"))
      (node (ref "U14") (pin "4") (pinfunction "GND1_4") (pintype "bidirectional"))
      (node (ref "U15") (pin "4") (pinfunction "GND1_4") (pintype "bidirectional"))
      (node (ref "U18") (pin "12") (pinfunction "SYNC_12") (pintype "input"))
      (node (ref "U18") (pin "14") (pinfunction "AGND_14") (pintype "passive"))
      (node (ref "U18") (pin "17") (pinfunction "EP_17") (pintype "passive"))
      (node (ref "U8") (pin "15") (pinfunction "GND2_15") (pintype "passive"))
      (node (ref "U8") (pin "9") (pinfunction "GND2_2_9") (pintype "passive"))
    )
    (net (code "35") (name "/IND+") (class "Default")
      (node (ref "R6") (pin "2") (pinfunction "2_2") (pintype "passive"))
      (node (ref "U$1") (pin "D+") (pinfunction "D+_D+") (pintype "bidirectional"))
    )
    (net (code "36") (name "/IND+_B") (class "Default")
      (node (ref "R31") (pin "2") (pinfunction "2_2") (pintype "passive"))
      (node (ref "U$5") (pin "D+") (pinfunction "D+_D+") (pintype "bidirectional"))
    )
    (net (code "37") (name "/IND-") (class "Default")
      (node (ref "R5") (pin "2") (pinfunction "2_2") (pintype "passive"))
      (node (ref "U$1") (pin "D-") (pinfunction "D-_D-") (pintype "bidirectional"))
    )
    (net (code "38") (name "/IND-_B") (class "Default")
      (node (ref "R30") (pin "2") (pinfunction "2_2") (pintype "passive"))
      (node (ref "U$5") (pin "D-") (pinfunction "D-_D-") (pintype "bidirectional"))
    )
    (net (code "39") (name "/MISO") (class "Default")
      (node (ref "JP10") (pin "1") (pinfunction "1_1") (pintype "passive"))
      (node (ref "U11") (pin "16") (pinfunction "PB4_16") (pintype "bidirectional"))
    )
    (net (code "40") (name "/MOSI") (class "Default")
      (node (ref "JP10") (pin "4") (pinfunction "4_4") (pintype "passive"))
      (node (ref "U11") (pin "15") (pinfunction "PB3_15") (pintype "bidirectional"))
    )
    (net (code "41") (name "/N$48") (class "Default")
      (node (ref "IC1") (pin "54") (pinfunction "DB3/CTS_54") (pintype "bidirectional"))
    )
    (net (code "42") (name "/N$51") (class "Default")
      (node (ref "IC1") (pin "57") (pinfunction "DB5/DSR_57") (pintype "bidirectional"))
    )
    (net (code "43") (name "/N$53") (class "Default")
      (node (ref "IC1") (pin "58") (pinfunction "DB6/DCD_58") (pintype "bidirectional"))
    )
    (net (code "44") (name "/N$54") (class "Default")
      (node (ref "IC1") (pin "59") (pinfunction "DB7/RI_59") (pintype "bidirectional"))
    )
    (net (code "45") (name "/PE_B") (class "Default")
      (node (ref "C27") (pin "-") (pinfunction "-_-") (pintype "passive"))
      (node (ref "C28") (pin "-") (pinfunction "-_-") (pintype "passive"))
      (node (ref "C42") (pin "P$2") (pinfunction "P$2_P$2") (pintype "bidirectional"))
      (node (ref "C43") (pin "1") (pinfunction "1_1") (pintype "passive"))
      (node (ref "C48") (pin "1") (pinfunction "1_1") (pintype "passive"))
      (node (ref "C49") (pin "P$2") (pinfunction "P$2_P$2") (pintype "bidirectional"))
      (node (ref "C51") (pin "P$2") (pinfunction "P$2_P$2") (pintype "bidirectional"))
      (node (ref "C53") (pin "P$2") (pinfunction "P$2_P$2") (pintype "bidirectional"))
      (node (ref "D3") (pin "1") (pinfunction "P$2_1") (pintype "bidirectional"))
      (node (ref "F4") (pin "P$1") (pinfunction "P$1_P$1") (pintype "bidirectional"))
      (node (ref "JP1") (pin "P$1") (pinfunction "P$1_P$1") (pintype "bidirectional"))
      (node (ref "JP1") (pin "P$13") (pinfunction "P$13_P$13") (pintype "bidirectional"))
      (node (ref "JP1") (pin "P$14") (pinfunction "P$14_P$14") (pintype "bidirectional"))
      (node (ref "JP1") (pin "P$15") (pinfunction "P$15_P$15") (pintype "bidirectional"))
      (node (ref "JP1") (pin "P$16") (pinfunction "P$16_P$16") (pintype "bidirectional"))
      (node (ref "JP1") (pin "P$2") (pinfunction "P$2_P$2") (pintype "bidirectional"))
      (node (ref "JP1") (pin "P$3") (pinfunction "P$3_P$3") (pintype "bidirectional"))
      (node (ref "JP1") (pin "P$4") (pinfunction "P$4_P$4") (pintype "bidirectional"))
      (node (ref "JP15") (pin "2") (pinfunction "2_2") (pintype "passive"))
      (node (ref "JP17") (pin "P$3") (pinfunction "P$3_P$3") (pintype "bidirectional"))
      (node (ref "JP17") (pin "P$4") (pinfunction "P$4_P$4") (pintype "bidirectional"))
      (node (ref "JP19") (pin "1") (pinfunction "P$1_1") (pintype "output"))
      (node (ref "JP19") (pin "11") (pinfunction "P$11_11") (pintype "output"))
      (node (ref "JP19") (pin "13") (pinfunction "P$13_13") (pintype "output"))
      (node (ref "JP19") (pin "15") (pinfunction "P$15_15") (pintype "output"))
      (node (ref "JP19") (pin "17") (pinfunction "P$17_17") (pintype "output"))
      (node (ref "JP19") (pin "19") (pinfunction "P$19_19") (pintype "output"))
      (node (ref "JP19") (pin "21") (pinfunction "P$21_21") (pintype "output"))
      (node (ref "JP19") (pin "23") (pinfunction "P$23_23") (pintype "output"))
      (node (ref "JP19") (pin "3") (pinfunction "P$3_3") (pintype "output"))
      (node (ref "JP19") (pin "5") (pinfunction "P$5_5") (pintype "output"))
      (node (ref "JP19") (pin "7") (pinfunction "P$7_7") (pintype "output"))
      (node (ref "JP19") (pin "9") (pinfunction "P$9_9") (pintype "output"))
      (node (ref "R25") (pin "1") (pinfunction "1_1") (pintype "passive"))
      (node (ref "R26") (pin "1") (pinfunction "1_1") (pintype "passive"))
      (node (ref "R61") (pin "1") (pinfunction "1_1") (pintype "passive"))
      (node (ref "U$8") (pin "P$3") (pinfunction "GND_P$3") (pintype "bidirectional"))
      (node (ref "U$8") (pin "P$4") (pinfunction "E2_P$4") (pintype "bidirectional"))
      (node (ref "U16") (pin "6") (pinfunction "GND_6") (pintype "passive"))
      (node (ref "U16") (pin "9") (pinfunction "EP_9") (pintype "passive"))
    )
    (net (code "46") (name "/RESET") (class "Default")
      (node (ref "C36") (pin "2") (pinfunction "2_2") (pintype "passive"))
      (node (ref "JP10") (pin "5") (pinfunction "5_5") (pintype "passive"))
      (node (ref "JP9") (pin "2") (pinfunction "2_2") (pintype "passive"))
      (node (ref "R21") (pin "1") (pinfunction "1_1") (pintype "passive"))
      (node (ref "R38") (pin "1") (pinfunction "1_1") (pintype "passive"))
      (node (ref "SW1") (pin "P$2") (pinfunction "P$2_P$2") (pintype "bidirectional"))
      (node (ref "SW1") (pin "P$3") (pinfunction "P$2_P$3") (pintype "bidirectional"))
      (node (ref "U11") (pin "29") (pinfunction "PC6_29") (pintype "bidirectional"))
    )
    (net (code "47") (name "/RX_1") (class "Default")
      (node (ref "JP3") (pin "2") (pinfunction "2_2") (pintype "passive"))
      (node (ref "U4") (pin "6") (pinfunction "OUTB_6") (pintype "bidirectional"))
    )
    (net (code "48") (name "/RX_2") (class "Default")
      (node (ref "JP4") (pin "2") (pinfunction "2_2") (pintype "passive"))
      (node (ref "U5") (pin "6") (pinfunction "OUTB_6") (pintype "bidirectional"))
    )
    (net (code "49") (name "/RX_3") (class "Default")
      (node (ref "JP5") (pin "2") (pinfunction "2_2") (pintype "passive"))
      (node (ref "U6") (pin "6") (pinfunction "OUTB_6") (pintype "bidirectional"))
    )
    (net (code "50") (name "/SCK") (class "Default")
      (node (ref "JP10") (pin "3") (pinfunction "3_3") (pintype "passive"))
      (node (ref "U11") (pin "17") (pinfunction "PB5_17") (pintype "bidirectional"))
    )
    (net (code "51") (name "/SGND_1") (class "Default")
      (node (ref "JP3") (pin "3") (pinfunction "3_3") (pintype "passive"))
      (node (ref "U4") (pin "5") (pinfunction "GND2_5") (pintype "bidirectional"))
    )
    (net (code "52") (name "/SGND_2") (class "Default")
      (node (ref "JP4") (pin "3") (pinfunction "3_3") (pintype "passive"))
      (node (ref "U5") (pin "5") (pinfunction "GND2_5") (pintype "bidirectional"))
    )
    (net (code "53") (name "/SGND_3") (class "Default")
      (node (ref "JP5") (pin "3") (pinfunction "3_3") (pintype "passive"))
      (node (ref "U6") (pin "5") (pinfunction "GND2_5") (pintype "bidirectional"))
    )
    (net (code "54") (name "/TX_1") (class "Default")
      (node (ref "JP3") (pin "1") (pinfunction "1_1") (pintype "passive"))
      (node (ref "U4") (pin "7") (pinfunction "INA_7") (pintype "bidirectional"))
    )
    (net (code "55") (name "/TX_2") (class "Default")
      (node (ref "JP4") (pin "1") (pinfunction "1_1") (pintype "passive"))
      (node (ref "U5") (pin "7") (pinfunction "INA_7") (pintype "bidirectional"))
    )
    (net (code "56") (name "/TX_3") (class "Default")
      (node (ref "JP5") (pin "1") (pinfunction "1_1") (pintype "passive"))
      (node (ref "U6") (pin "7") (pinfunction "INA_7") (pintype "bidirectional"))
    )
    (net (code "57") (name "/VBATT_1A") (class "Default")
      (node (ref "C33") (pin "+") (pinfunction "+_+") (pintype "passive"))
      (node (ref "D8") (pin "1") (pinfunction "P$2_1") (pintype "bidirectional"))
      (node (ref "JP2") (pin "P$5") (pinfunction "P$5_P$5") (pintype "bidirectional"))
      (node (ref "JP2") (pin "P$6") (pinfunction "P$6_P$6") (pintype "bidirectional"))
      (node (ref "JP2") (pin "P$7") (pinfunction "P$7_P$7") (pintype "bidirectional"))
      (node (ref "JP2") (pin "P$8") (pinfunction "P$8_P$8") (pintype "bidirectional"))
      (node (ref "LED7") (pin "A") (pinfunction "A_A") (pintype "passive"))
      (node (ref "U$11") (pin "P$7") (pinfunction "V2_P$7") (pintype "bidirectional"))
      (node (ref "U$12") (pin "P$7") (pinfunction "V2_P$7") (pintype "bidirectional"))
      (node (ref "U$13") (pin "P$7") (pinfunction "V2_P$7") (pintype "bidirectional"))
      (node (ref "U$17") (pin "P$5") (pinfunction "D_P$5") (pintype "bidirectional"))
      (node (ref "U$17") (pin "P$6") (pinfunction "D_P$6") (pintype "bidirectional"))
      (node (ref "U$17") (pin "P$7") (pinfunction "D_P$7") (pintype "bidirectional"))
      (node (ref "U$17") (pin "P$8") (pinfunction "D_P$8") (pintype "bidirectional"))
      (node (ref "U$19") (pin "P$5") (pinfunction "D_P$5") (pintype "bidirectional"))
      (node (ref "U$19") (pin "P$6") (pinfunction "D_P$6") (pintype "bidirectional"))
      (node (ref "U$19") (pin "P$7") (pinfunction "D_P$7") (pintype "bidirectional"))
      (node (ref "U$19") (pin "P$8") (pinfunction "D_P$8") (pintype "bidirectional"))
      (node (ref "U$21") (pin "P$5") (pinfunction "D_P$5") (pintype "bidirectional"))
      (node (ref "U$21") (pin "P$6") (pinfunction "D_P$6") (pintype "bidirectional"))
      (node (ref "U$21") (pin "P$7") (pinfunction "D_P$7") (pintype "bidirectional"))
      (node (ref "U$21") (pin "P$8") (pinfunction "D_P$8") (pintype "bidirectional"))
    )
    (net (code "58") (name "/VBATT_1B") (class "Default")
      (node (ref "C28") (pin "+") (pinfunction "+_+") (pintype "passive"))
      (node (ref "C51") (pin "P$1") (pinfunction "P$1_P$1") (pintype "bidirectional"))
      (node (ref "D9") (pin "1") (pinfunction "P$2_1") (pintype "bidirectional"))
      (node (ref "JP1") (pin "P$5") (pinfunction "P$5_P$5") (pintype "bidirectional"))
      (node (ref "JP1") (pin "P$6") (pinfunction "P$6_P$6") (pintype "bidirectional"))
      (node (ref "JP1") (pin "P$7") (pinfunction "P$7_P$7") (pintype "bidirectional"))
      (node (ref "JP1") (pin "P$8") (pinfunction "P$8_P$8") (pintype "bidirectional"))
      (node (ref "JP19") (pin "10") (pinfunction "P$10_10") (pintype "output"))
      (node (ref "JP19") (pin "12") (pinfunction "P$12_12") (pintype "output"))
      (node (ref "JP19") (pin "4") (pinfunction "P$4_4") (pintype "output"))
      (node (ref "JP19") (pin "6") (pinfunction "P$6_6") (pintype "output"))
      (node (ref "JP19") (pin "8") (pinfunction "P$8_8") (pintype "output"))
      (node (ref "LED5") (pin "A") (pinfunction "A_A") (pintype "passive"))
      (node (ref "U$10") (pin "P$5") (pinfunction "D_P$5") (pintype "bidirectional"))
      (node (ref "U$10") (pin "P$6") (pinfunction "D_P$6") (pintype "bidirectional"))
      (node (ref "U$10") (pin "P$7") (pinfunction "D_P$7") (pintype "bidirectional"))
      (node (ref "U$10") (pin "P$8") (pinfunction "D_P$8") (pintype "bidirectional"))
      (node (ref "U$8") (pin "P$7") (pinfunction "V2_P$7") (pintype "bidirectional"))
    )
    (net (code "59") (name "/VBATT_2A") (class "Default")
      (node (ref "C32") (pin "+") (pinfunction "+_+") (pintype "passive"))
      (node (ref "D7") (pin "1") (pinfunction "P$2_1") (pintype "bidirectional"))
      (node (ref "JP2") (pin "P$10") (pinfunction "P$10_P$10") (pintype "bidirectional"))
      (node (ref "JP2") (pin "P$11") (pinfunction "P$11_P$11") (pintype "bidirectional"))
      (node (ref "JP2") (pin "P$12") (pinfunction "P$12_P$12") (pintype "bidirectional"))
      (node (ref "JP2") (pin "P$9") (pinfunction "P$9_P$9") (pintype "bidirectional"))
      (node (ref "LED6") (pin "A") (pinfunction "A_A") (pintype "passive"))
      (node (ref "U$11") (pin "P$9") (pinfunction "V1_P$9") (pintype "bidirectional"))
      (node (ref "U$12") (pin "P$9") (pinfunction "V1_P$9") (pintype "bidirectional"))
      (node (ref "U$13") (pin "P$9") (pinfunction "V1_P$9") (pintype "bidirectional"))
      (node (ref "U$16") (pin "P$5") (pinfunction "D_P$5") (pintype "bidirectional"))
      (node (ref "U$16") (pin "P$6") (pinfunction "D_P$6") (pintype "bidirectional"))
      (node (ref "U$16") (pin "P$7") (pinfunction "D_P$7") (pintype "bidirectional"))
      (node (ref "U$16") (pin "P$8") (pinfunction "D_P$8") (pintype "bidirectional"))
      (node (ref "U$18") (pin "P$5") (pinfunction "D_P$5") (pintype "bidirectional"))
      (node (ref "U$18") (pin "P$6") (pinfunction "D_P$6") (pintype "bidirectional"))
      (node (ref "U$18") (pin "P$7") (pinfunction "D_P$7") (pintype "bidirectional"))
      (node (ref "U$18") (pin "P$8") (pinfunction "D_P$8") (pintype "bidirectional"))
      (node (ref "U$20") (pin "P$5") (pinfunction "D_P$5") (pintype "bidirectional"))
      (node (ref "U$20") (pin "P$6") (pinfunction "D_P$6") (pintype "bidirectional"))
      (node (ref "U$20") (pin "P$7") (pinfunction "D_P$7") (pintype "bidirectional"))
      (node (ref "U$20") (pin "P$8") (pinfunction "D_P$8") (pintype "bidirectional"))
    )
    (net (code "60") (name "/VBATT_2B") (class "Default")
      (node (ref "C27") (pin "+") (pinfunction "+_+") (pintype "passive"))
      (node (ref "C53") (pin "P$1") (pinfunction "P$1_P$1") (pintype "bidirectional"))
      (node (ref "D10") (pin "1") (pinfunction "P$2_1") (pintype "bidirectional"))
      (node (ref "JP1") (pin "P$10") (pinfunction "P$10_P$10") (pintype "bidirectional"))
      (node (ref "JP1") (pin "P$11") (pinfunction "P$11_P$11") (pintype "bidirectional"))
      (node (ref "JP1") (pin "P$12") (pinfunction "P$12_P$12") (pintype "bidirectional"))
      (node (ref "JP1") (pin "P$9") (pinfunction "P$9_P$9") (pintype "bidirectional"))
      (node (ref "JP19") (pin "14") (pinfunction "P$14_14") (pintype "output"))
      (node (ref "JP19") (pin "16") (pinfunction "P$16_16") (pintype "output"))
      (node (ref "JP19") (pin "18") (pinfunction "P$18_18") (pintype "output"))
      (node (ref "JP19") (pin "20") (pinfunction "P$20_20") (pintype "output"))
      (node (ref "JP19") (pin "22") (pinfunction "P$22_22") (pintype "output"))
      (node (ref "JP19") (pin "24") (pinfunction "P$24_24") (pintype "output"))
      (node (ref "LED4") (pin "A") (pinfunction "A_A") (pintype "passive"))
      (node (ref "U$8") (pin "P$9") (pinfunction "V1_P$9") (pintype "bidirectional"))
      (node (ref "U$9") (pin "P$5") (pinfunction "D_P$5") (pintype "bidirectional"))
      (node (ref "U$9") (pin "P$6") (pinfunction "D_P$6") (pintype "bidirectional"))
      (node (ref "U$9") (pin "P$7") (pinfunction "D_P$7") (pintype "bidirectional"))
      (node (ref "U$9") (pin "P$8") (pinfunction "D_P$8") (pintype "bidirectional"))
    )
    (net (code "61") (name "/V_1A") (class "Default")
      (node (ref "C45") (pin "P$1") (pinfunction "P$1_P$1") (pintype "bidirectional"))
      (node (ref "JP18") (pin "P$7") (pinfunction "P$7_P$7") (pintype "bidirectional"))
      (node (ref "JP18") (pin "P$9") (pinfunction "P$9_P$9") (pintype "bidirectional"))
      (node (ref "LED13") (pin "A") (pinfunction "A_A") (pintype "passive"))
      (node (ref "U$13") (pin "P$8") (pinfunction "VS_P$8") (pintype "bidirectional"))
      (node (ref "U$26") (pin "P$5") (pinfunction "D_P$5") (pintype "bidirectional"))
      (node (ref "U$26") (pin "P$6") (pinfunction "D_P$6") (pintype "bidirectional"))
      (node (ref "U$26") (pin "P$7") (pinfunction "D_P$7") (pintype "bidirectional"))
      (node (ref "U$26") (pin "P$8") (pinfunction "D_P$8") (pintype "bidirectional"))
      (node (ref "U$27") (pin "P$5") (pinfunction "D_P$5") (pintype "bidirectional"))
      (node (ref "U$27") (pin "P$6") (pinfunction "D_P$6") (pintype "bidirectional"))
      (node (ref "U$27") (pin "P$7") (pinfunction "D_P$7") (pintype "bidirectional"))
      (node (ref "U$27") (pin "P$8") (pinfunction "D_P$8") (pintype "bidirectional"))
    )
    (net (code "62") (name "/V_2A") (class "Default")
      (node (ref "C44") (pin "P$1") (pinfunction "P$1_P$1") (pintype "bidirectional"))
      (node (ref "JP16") (pin "2") (pinfunction "2_2") (pintype "passive"))
      (node (ref "JP18") (pin "P$1") (pinfunction "P$1_P$1") (pintype "bidirectional"))
      (node (ref "JP18") (pin "P$3") (pinfunction "P$3_P$3") (pintype "bidirectional"))
      (node (ref "JP18") (pin "P$5") (pinfunction "P$5_P$5") (pintype "bidirectional"))
      (node (ref "LED12") (pin "A") (pinfunction "A_A") (pintype "passive"))
      (node (ref "U$12") (pin "P$8") (pinfunction "VS_P$8") (pintype "bidirectional"))
      (node (ref "U$24") (pin "P$5") (pinfunction "D_P$5") (pintype "bidirectional"))
      (node (ref "U$24") (pin "P$6") (pinfunction "D_P$6") (pintype "bidirectional"))
      (node (ref "U$24") (pin "P$7") (pinfunction "D_P$7") (pintype "bidirectional"))
      (node (ref "U$24") (pin "P$8") (pinfunction "D_P$8") (pintype "bidirectional"))
      (node (ref "U$25") (pin "P$5") (pinfunction "D_P$5") (pintype "bidirectional"))
      (node (ref "U$25") (pin "P$6") (pinfunction "D_P$6") (pintype "bidirectional"))
      (node (ref "U$25") (pin "P$7") (pinfunction "D_P$7") (pintype "bidirectional"))
      (node (ref "U$25") (pin "P$8") (pinfunction "D_P$8") (pintype "bidirectional"))
    )
    (net (code "63") (name "/V_3A") (class "Default")
      (node (ref "C47") (pin "2") (pinfunction "2_2") (pintype "passive"))
      (node (ref "C50") (pin "P$1") (pinfunction "P$1_P$1") (pintype "bidirectional"))
      (node (ref "JP18") (pin "P$11") (pinfunction "P$11_P$11") (pintype "bidirectional"))
      (node (ref "JP18") (pin "P$13") (pinfunction "P$13_P$13") (pintype "bidirectional"))
      (node (ref "LED15") (pin "A") (pinfunction "A_A") (pintype "passive"))
      (node (ref "U$11") (pin "P$8") (pinfunction "VS_P$8") (pintype "bidirectional"))
      (node (ref "U$22") (pin "P$5") (pinfunction "D_P$5") (pintype "bidirectional"))
      (node (ref "U$22") (pin "P$6") (pinfunction "D_P$6") (pintype "bidirectional"))
      (node (ref "U$22") (pin "P$7") (pinfunction "D_P$7") (pintype "bidirectional"))
      (node (ref "U$22") (pin "P$8") (pinfunction "D_P$8") (pintype "bidirectional"))
      (node (ref "U$23") (pin "P$5") (pinfunction "D_P$5") (pintype "bidirectional"))
      (node (ref "U$23") (pin "P$6") (pinfunction "D_P$6") (pintype "bidirectional"))
      (node (ref "U$23") (pin "P$7") (pinfunction "D_P$7") (pintype "bidirectional"))
      (node (ref "U$23") (pin "P$8") (pinfunction "D_P$8") (pintype "bidirectional"))
      (node (ref "U17") (pin "7") (pinfunction "VIN_7") (pintype "input"))
    )
    (net (code "64") (name "/XTAL1") (class "Default")
      (node (ref "C37") (pin "2") (pinfunction "2_2") (pintype "passive"))
      (node (ref "R39") (pin "1") (pinfunction "1_1") (pintype "passive"))
      (node (ref "U$7") (pin "P$1") (pinfunction "P$1_P$1") (pintype "bidirectional"))
      (node (ref "U11") (pin "7") (pinfunction "PB6_7") (pintype "bidirectional"))
    )
    (net (code "65") (name "/XTAL2") (class "Default")
      (node (ref "C38") (pin "2") (pinfunction "2_2") (pintype "passive"))
      (node (ref "R39") (pin "2") (pinfunction "2_2") (pintype "passive"))
      (node (ref "U$7") (pin "P$3") (pinfunction "P$2_P$3") (pintype "bidirectional"))
      (node (ref "U11") (pin "8") (pinfunction "PB7_8") (pintype "bidirectional"))
    )
    (net (code "66") (name "/XTAL3") (class "Default")
      (node (ref "C5") (pin "2") (pinfunction "2_2") (pintype "passive"))
      (node (ref "IC1") (pin "3") (pinfunction "XTOUT_3") (pintype "output"))
      (node (ref "R2") (pin "1") (pinfunction "1_1") (pintype "passive"))
      (node (ref "U$2") (pin "P$1") (pinfunction "P$1_P$1") (pintype "bidirectional"))
    )
    (net (code "67") (name "/XTAL4") (class "Default")
      (node (ref "C6") (pin "2") (pinfunction "2_2") (pintype "passive"))
      (node (ref "IC1") (pin "2") (pinfunction "XTIN_2") (pintype "input"))
      (node (ref "R2") (pin "2") (pinfunction "2_2") (pintype "passive"))
      (node (ref "U$2") (pin "P$3") (pinfunction "P$2_P$3") (pintype "bidirectional"))
    )
    (net (code "68") (name "/XTAL5") (class "Default")
      (node (ref "C25") (pin "2") (pinfunction "2_2") (pintype "passive"))
      (node (ref "IC2") (pin "3") (pinfunction "XTOUT_3") (pintype "output"))
      (node (ref "R27") (pin "1") (pinfunction "1_1") (pintype "passive"))
      (node (ref "U$6") (pin "P$1") (pinfunction "P$1_P$1") (pintype "bidirectional"))
    )
    (net (code "69") (name "/XTAL6") (class "Default")
      (node (ref "C26") (pin "2") (pinfunction "2_2") (pintype "passive"))
      (node (ref "IC2") (pin "2") (pinfunction "XTIN_2") (pintype "input"))
      (node (ref "R27") (pin "2") (pinfunction "2_2") (pintype "passive"))
      (node (ref "U$6") (pin "P$3") (pinfunction "P$2_P$3") (pintype "bidirectional"))
    )
    (net (code "70") (name "Net-(D1-P$1)") (class "Default")
      (node (ref "C15") (pin "1") (pinfunction "1_1") (pintype "passive"))
      (node (ref "D1") (pin "2") (pinfunction "P$1_2") (pintype "bidirectional"))
      (node (ref "L1") (pin "2") (pinfunction "P$2_2") (pintype "bidirectional"))
      (node (ref "U3") (pin "3") (pinfunction "SW1_3") (pintype "output"))
    )
    (net (code "71") (name "Net-(D1-P$2)") (class "Default")
      (node (ref "D1") (pin "1") (pinfunction "P$2_1") (pintype "bidirectional"))
      (node (ref "U3") (pin "1") (pinfunction "DA1_1") (pintype "input"))
    )
    (net (code "72") (name "Net-(D2-P$1)") (class "Default")
      (node (ref "C16") (pin "1") (pinfunction "1_1") (pintype "passive"))
      (node (ref "D2") (pin "2") (pinfunction "P$1_2") (pintype "bidirectional"))
      (node (ref "L2") (pin "1") (pinfunction "P$1_1") (pintype "bidirectional"))
      (node (ref "U3") (pin "6") (pinfunction "SW2_6") (pintype "output"))
    )
    (net (code "73") (name "Net-(D2-P$2)") (class "Default")
      (node (ref "D2") (pin "1") (pinfunction "P$2_1") (pintype "bidirectional"))
      (node (ref "U3") (pin "8") (pinfunction "DA2_8") (pintype "input"))
    )
    (net (code "74") (name "Net-(D3-P$1)") (class "Default")
      (node (ref "C41") (pin "1") (pinfunction "1_1") (pintype "passive"))
      (node (ref "D3") (pin "2") (pinfunction "P$1_2") (pintype "bidirectional"))
      (node (ref "L3") (pin "1") (pinfunction "P$1_1") (pintype "bidirectional"))
      (node (ref "U16") (pin "8") (pinfunction "PH_8") (pintype "output"))
    )
    (net (code "75") (name "Net-(D4-P$1)") (class "Default")
      (node (ref "C46") (pin "1") (pinfunction "1_1") (pintype "passive"))
      (node (ref "D4") (pin "2") (pinfunction "P$1_2") (pintype "bidirectional"))
      (node (ref "L4") (pin "1") (pinfunction "P$1_1") (pintype "bidirectional"))
      (node (ref "U17") (pin "8") (pinfunction "PH_8") (pintype "output"))
    )
    (net (code "76") (name "Net-(D5-P$1)") (class "Default")
      (node (ref "C58") (pin "1") (pinfunction "1_1") (pintype "passive"))
      (node (ref "D5") (pin "2") (pinfunction "P$1_2") (pintype "bidirectional"))
      (node (ref "L5") (pin "2") (pinfunction "P$2_2") (pintype "bidirectional"))
      (node (ref "U18") (pin "3") (pinfunction "SW1_3") (pintype "output"))
    )
    (net (code "77") (name "Net-(D5-P$2)") (class "Default")
      (node (ref "D5") (pin "1") (pinfunction "P$2_1") (pintype "bidirectional"))
      (node (ref "U18") (pin "1") (pinfunction "DA1_1") (pintype "input"))
    )
    (net (code "78") (name "Net-(D6-P$1)") (class "Default")
      (node (ref "C59") (pin "1") (pinfunction "1_1") (pintype "passive"))
      (node (ref "D6") (pin "2") (pinfunction "P$1_2") (pintype "bidirectional"))
      (node (ref "L6") (pin "1") (pinfunction "P$1_1") (pintype "bidirectional"))
      (node (ref "U18") (pin "6") (pinfunction "SW2_6") (pintype "output"))
    )
    (net (code "79") (name "Net-(D6-P$2)") (class "Default")
      (node (ref "D6") (pin "1") (pinfunction "P$2_1") (pintype "bidirectional"))
      (node (ref "U18") (pin "8") (pinfunction "DA2_8") (pintype "input"))
    )
    (net (code "80") (name "Net-(D7-P$1)") (class "Default")
      (node (ref "D7") (pin "2") (pinfunction "P$1_2") (pintype "bidirectional"))
      (node (ref "D8") (pin "2") (pinfunction "P$1_2") (pintype "bidirectional"))
      (node (ref "F1") (pin "P$1") (pinfunction "P$1_P$1") (pintype "bidirectional"))
    )
    (net (code "81") (name "Net-(D10-P$1)") (class "Default")
      (node (ref "D10") (pin "2") (pinfunction "P$1_2") (pintype "bidirectional"))
      (node (ref "D9") (pin "2") (pinfunction "P$1_2") (pintype "bidirectional"))
      (node (ref "F3") (pin "P$1") (pinfunction "P$1_P$1") (pintype "bidirectional"))
    )
    (net (code "82") (name "Net-(IC1A-DB0{slash}TXD)") (class "Default")
      (node (ref "IC1") (pin "16") (pinfunction "DB0/TXD_16") (pintype "bidirectional"))
      (node (ref "U4") (pin "3") (pinfunction "INB_3") (pintype "bidirectional"))
    )
    (net (code "83") (name "Net-(IC1A-DB1{slash}RXD)") (class "Default")
      (node (ref "IC1") (pin "17") (pinfunction "DB1/RXD_17") (pintype "bidirectional"))
      (node (ref "U4") (pin "2") (pinfunction "OUTA_2") (pintype "bidirectional"))
    )
    (net (code "84") (name "Net-(IC1B-DB0{slash}TXD)") (class "Default")
      (node (ref "IC1") (pin "26") (pinfunction "DB0/TXD_26") (pintype "bidirectional"))
      (node (ref "U5") (pin "3") (pinfunction "INB_3") (pintype "bidirectional"))
    )
    (net (code "85") (name "Net-(IC1B-DB1{slash}RXD)") (class "Default")
      (node (ref "IC1") (pin "27") (pinfunction "DB1/RXD_27") (pintype "bidirectional"))
      (node (ref "U5") (pin "2") (pinfunction "OUTA_2") (pintype "bidirectional"))
    )
    (net (code "86") (name "Net-(IC1C-DB0{slash}TXD)") (class "Default")
      (node (ref "IC1") (pin "38") (pinfunction "DB0/TXD_38") (pintype "bidirectional"))
      (node (ref "U6") (pin "3") (pinfunction "INB_3") (pintype "bidirectional"))
    )
    (net (code "87") (name "Net-(IC1C-DB1{slash}RXD)") (class "Default")
      (node (ref "IC1") (pin "39") (pinfunction "DB1/RXD_39") (pintype "bidirectional"))
      (node (ref "U6") (pin "2") (pinfunction "OUTA_2") (pintype "bidirectional"))
    )
    (net (code "88") (name "Net-(IC1D-REF)") (class "Default")
      (node (ref "IC1") (pin "6") (pinfunction "REF_6") (pintype "input"))
      (node (ref "R8") (pin "2") (pinfunction "2_2") (pintype "passive"))
    )
    (net (code "89") (name "Net-(IC1D-RESET#)") (class "Default")
      (node (ref "IC1") (pin "14") (pinfunction "RESET#_14") (pintype "input"))
      (node (ref "R7") (pin "2") (pinfunction "2_2") (pintype "passive"))
    )
    (net (code "90") (name "Net-(IC1D-USBDM)") (class "Default")
      (node (ref "IC1") (pin "7") (pinfunction "USBDM_7") (pintype "input"))
      (node (ref "R3") (pin "2") (pinfunction "2_2") (pintype "passive"))
    )
    (net (code "91") (name "Net-(IC1D-USBDP)") (class "Default")
      (node (ref "IC1") (pin "8") (pinfunction "USBDP_8") (pintype "input"))
      (node (ref "R4") (pin "2") (pinfunction "2_2") (pintype "passive"))
    )
    (net (code "92") (name "Net-(IC1D-VPHY)") (class "Default")
      (node (ref "C10") (pin "2") (pinfunction "2_2") (pintype "passive"))
      (node (ref "IC1") (pin "4") (pinfunction "VPHY_4") (pintype "input"))
      (node (ref "R9") (pin "2") (pinfunction "2_2") (pintype "passive"))
    )
    (net (code "93") (name "Net-(IC1D-VPLL)") (class "Default")
      (node (ref "C9") (pin "2") (pinfunction "2_2") (pintype "passive"))
      (node (ref "IC1") (pin "9") (pinfunction "VPLL_9") (pintype "input"))
      (node (ref "R10") (pin "2") (pinfunction "2_2") (pintype "passive"))
    )
    (net (code "94") (name "Net-(IC1E-DB0{slash}TXD)") (class "Default")
      (node (ref "IC1") (pin "48") (pinfunction "DB0/TXD_48") (pintype "bidirectional"))
      (node (ref "R19") (pin "2") (pinfunction "2_2") (pintype "passive"))
    )
    (net (code "95") (name "Net-(IC1E-DB1{slash}RXD)") (class "Default")
      (node (ref "IC1") (pin "52") (pinfunction "DB1/RXD_52") (pintype "bidirectional"))
      (node (ref "R20") (pin "2") (pinfunction "2_2") (pintype "passive"))
    )
    (net (code "96") (name "Net-(IC1E-DB2{slash}RTS)") (class "Default")
      (node (ref "IC1") (pin "53") (pinfunction "DB2/RTS_53") (pintype "bidirectional"))
      (node (ref "R21") (pin "2") (pinfunction "2_2") (pintype "passive"))
    )
    (net (code "97") (name "Net-(IC2A-DB0{slash}TXD)") (class "Default")
      (node (ref "IC2") (pin "16") (pinfunction "DB0/TXD_16") (pintype "bidirectional"))
      (node (ref "U12") (pin "3") (pinfunction "INB_3") (pintype "bidirectional"))
    )
    (net (code "98") (name "Net-(IC2A-DB1{slash}RXD)") (class "Default")
      (node (ref "IC2") (pin "17") (pinfunction "DB1/RXD_17") (pintype "bidirectional"))
      (node (ref "U12") (pin "2") (pinfunction "OUTA_2") (pintype "bidirectional"))
    )
    (net (code "99") (name "Net-(IC2B-DB0{slash}TXD)") (class "Default")
      (node (ref "IC2") (pin "26") (pinfunction "DB0/TXD_26") (pintype "bidirectional"))
      (node (ref "U13") (pin "3") (pinfunction "INB_3") (pintype "bidirectional"))
    )
    (net (code "100") (name "Net-(IC2B-DB1{slash}RXD)") (class "Default")
      (node (ref "IC2") (pin "27") (pinfunction "DB1/RXD_27") (pintype "bidirectional"))
      (node (ref "U13") (pin "2") (pinfunction "OUTA_2") (pintype "bidirectional"))
    )
    (net (code "101") (name "Net-(IC2C-DB0{slash}TXD)") (class "Default")
      (node (ref "IC2") (pin "38") (pinfunction "DB0/TXD_38") (pintype "bidirectional"))
      (node (ref "U14") (pin "3") (pinfunction "INB_3") (pintype "bidirectional"))
    )
    (net (code "102") (name "Net-(IC2C-DB1{slash}RXD)") (class "Default")
      (node (ref "IC2") (pin "39") (pinfunction "DB1/RXD_39") (pintype "bidirectional"))
      (node (ref "U14") (pin "2") (pinfunction "OUTA_2") (pintype "bidirectional"))
    )
    (net (code "103") (name "Net-(IC2D-REF)") (class "Default")
      (node (ref "IC2") (pin "6") (pinfunction "REF_6") (pintype "input"))
      (node (ref "R35") (pin "2") (pinfunction "2_2") (pintype "passive"))
    )
    (net (code "104") (name "Net-(IC2D-RESET#)") (class "Default")
      (node (ref "IC2") (pin "14") (pinfunction "RESET#_14") (pintype "input"))
      (node (ref "R34") (pin "2") (pinfunction "2_2") (pintype "passive"))
    )
    (net (code "105") (name "Net-(IC2D-USBDM)") (class "Default")
      (node (ref "IC2") (pin "7") (pinfunction "USBDM_7") (pintype "input"))
      (node (ref "R28") (pin "2") (pinfunction "2_2") (pintype "passive"))
    )
    (net (code "106") (name "Net-(IC2D-USBDP)") (class "Default")
      (node (ref "IC2") (pin "8") (pinfunction "USBDP_8") (pintype "input"))
      (node (ref "R29") (pin "2") (pinfunction "2_2") (pintype "passive"))
    )
    (net (code "107") (name "Net-(IC2D-VPHY)") (class "Default")
      (node (ref "C35") (pin "2") (pinfunction "2_2") (pintype "passive"))
      (node (ref "IC2") (pin "4") (pinfunction "VPHY_4") (pintype "input"))
      (node (ref "R36") (pin "2") (pinfunction "2_2") (pintype "passive"))
    )
    (net (code "108") (name "Net-(IC2D-VPLL)") (class "Default")
      (node (ref "C34") (pin "2") (pinfunction "2_2") (pintype "passive"))
      (node (ref "IC2") (pin "9") (pinfunction "VPLL_9") (pintype "input"))
      (node (ref "R37") (pin "2") (pinfunction "2_2") (pintype "passive"))
    )
    (net (code "109") (name "Net-(IC2E-DB0{slash}TXD)") (class "Default")
      (node (ref "IC2") (pin "48") (pinfunction "DB0/TXD_48") (pintype "bidirectional"))
      (node (ref "U15") (pin "3") (pinfunction "INB_3") (pintype "bidirectional"))
    )
    (net (code "110") (name "Net-(IC2E-DB1{slash}RXD)") (class "Default")
      (node (ref "IC2") (pin "52") (pinfunction "DB1/RXD_52") (pintype "bidirectional"))
      (node (ref "U15") (pin "2") (pinfunction "OUTA_2") (pintype "bidirectional"))
    )
    (net (code "111") (name "Net-(JP7-Pad1)") (class "Default")
      (node (ref "JP7") (pin "1") (pinfunction "1_1") (pintype "passive"))
      (node (ref "U7") (pin "P$4") (pinfunction "P$4_P$4") (pintype "bidirectional"))
    )
    (net (code "112") (name "Net-(JP7-Pad2)") (class "Default")
      (node (ref "JP7") (pin "2") (pinfunction "2_2") (pintype "passive"))
      (node (ref "U7") (pin "P$3") (pinfunction "P$3_P$3") (pintype "bidirectional"))
    )
    (net (code "113") (name "Net-(JP19-P$2)") (class "Default")
      (node (ref "C48") (pin "2") (pinfunction "2_2") (pintype "passive"))
      (node (ref "C49") (pin "P$1") (pinfunction "P$1_P$1") (pintype "bidirectional"))
      (node (ref "JP19") (pin "2") (pinfunction "P$2_2") (pintype "output"))
      (node (ref "L3") (pin "2") (pinfunction "P$2_2") (pintype "bidirectional"))
      (node (ref "R60") (pin "2") (pinfunction "2_2") (pintype "passive"))
    )
    (net (code "114") (name "Net-(L4-P$2)") (class "Default")
      (node (ref "C52") (pin "2") (pinfunction "2_2") (pintype "passive"))
      (node (ref "C54") (pin "P$1") (pinfunction "P$1_P$1") (pintype "bidirectional"))
      (node (ref "JP18") (pin "P$15") (pinfunction "P$15_P$15") (pintype "bidirectional"))
      (node (ref "L4") (pin "2") (pinfunction "P$2_2") (pintype "bidirectional"))
      (node (ref "LED14") (pin "A") (pinfunction "A_A") (pintype "passive"))
      (node (ref "R64") (pin "2") (pinfunction "2_2") (pintype "passive"))
    )
    (net (code "115") (name "Net-(LED1-PadC)") (class "Default")
      (node (ref "LED1") (pin "C") (pinfunction "C_C") (pintype "passive"))
      (node (ref "R1") (pin "2") (pinfunction "2_2") (pintype "passive"))
    )
    (net (code "116") (name "Net-(LED2-PadC)") (class "Default")
      (node (ref "LED2") (pin "C") (pinfunction "C_C") (pintype "passive"))
      (node (ref "R11") (pin "2") (pinfunction "2_2") (pintype "passive"))
    )
    (net (code "117") (name "Net-(LED3-PadC)") (class "Default")
      (node (ref "LED3") (pin "C") (pinfunction "C_C") (pintype "passive"))
      (node (ref "R24") (pin "2") (pinfunction "2_2") (pintype "passive"))
    )
    (net (code "118") (name "Net-(LED4-PadC)") (class "Default")
      (node (ref "LED4") (pin "C") (pinfunction "C_C") (pintype "passive"))
      (node (ref "R25") (pin "2") (pinfunction "2_2") (pintype "passive"))
    )
    (net (code "119") (name "Net-(LED5-PadC)") (class "Default")
      (node (ref "LED5") (pin "C") (pinfunction "C_C") (pintype "passive"))
      (node (ref "R26") (pin "2") (pinfunction "2_2") (pintype "passive"))
    )
    (net (code "120") (name "Net-(LED6-PadC)") (class "Default")
      (node (ref "LED6") (pin "C") (pinfunction "C_C") (pintype "passive"))
      (node (ref "R32") (pin "2") (pinfunction "2_2") (pintype "passive"))
    )
    (net (code "121") (name "Net-(LED7-PadC)") (class "Default")
      (node (ref "LED7") (pin "C") (pinfunction "C_C") (pintype "passive"))
      (node (ref "R33") (pin "2") (pinfunction "2_2") (pintype "passive"))
    )
    (net (code "122") (name "Net-(LED8-PadC)") (class "Default")
      (node (ref "LED8") (pin "C") (pinfunction "C_C") (pintype "passive"))
      (node (ref "R54") (pin "2") (pinfunction "2_2") (pintype "passive"))
    )
    (net (code "123") (name "Net-(LED9-PadC)") (class "Default")
      (node (ref "LED9") (pin "C") (pinfunction "C_C") (pintype "passive"))
      (node (ref "R55") (pin "2") (pinfunction "2_2") (pintype "passive"))
    )
    (net (code "124") (name "Net-(LED10-PadC)") (class "Default")
      (node (ref "LED10") (pin "C") (pinfunction "C_C") (pintype "passive"))
      (node (ref "R56") (pin "2") (pinfunction "2_2") (pintype "passive"))
    )
    (net (code "125") (name "Net-(LED11-PadC)") (class "Default")
      (node (ref "LED11") (pin "C") (pinfunction "C_C") (pintype "passive"))
      (node (ref "R57") (pin "2") (pinfunction "2_2") (pintype "passive"))
    )
    (net (code "126") (name "Net-(LED12-PadC)") (class "Default")
      (node (ref "LED12") (pin "C") (pinfunction "C_C") (pintype "passive"))
      (node (ref "R58") (pin "2") (pinfunction "2_2") (pintype "passive"))
    )
    (net (code "127") (name "Net-(LED13-PadC)") (class "Default")
      (node (ref "LED13") (pin "C") (pinfunction "C_C") (pintype "passive"))
      (node (ref "R59") (pin "2") (pinfunction "2_2") (pintype "passive"))
    )
    (net (code "128") (name "Net-(LED14-PadC)") (class "Default")
      (node (ref "LED14") (pin "C") (pinfunction "C_C") (pintype "passive"))
      (node (ref "R62") (pin "1") (pinfunction "1_1") (pintype "passive"))
    )
    (net (code "129") (name "Net-(LED15-PadC)") (class "Default")
      (node (ref "LED15") (pin "C") (pinfunction "C_C") (pintype "passive"))
      (node (ref "R63") (pin "1") (pinfunction "1_1") (pintype "passive"))
    )
    (net (code "130") (name "Net-(U$8-VS)") (class "Default")
      (node (ref "C42") (pin "P$1") (pinfunction "P$1_P$1") (pintype "bidirectional"))
      (node (ref "C43") (pin "2") (pinfunction "2_2") (pintype "passive"))
      (node (ref "JP15") (pin "1") (pinfunction "1_1") (pintype "passive"))
      (node (ref "JP17") (pin "P$1") (pinfunction "P$1_P$1") (pintype "bidirectional"))
      (node (ref "JP17") (pin "P$2") (pinfunction "P$2_P$2") (pintype "bidirectional"))
      (node (ref "U$14") (pin "P$5") (pinfunction "D_P$5") (pintype "bidirectional"))
      (node (ref "U$14") (pin "P$6") (pinfunction "D_P$6") (pintype "bidirectional"))
      (node (ref "U$14") (pin "P$7") (pinfunction "D_P$7") (pintype "bidirectional"))
      (node (ref "U$14") (pin "P$8") (pinfunction "D_P$8") (pintype "bidirectional"))
      (node (ref "U$15") (pin "P$5") (pinfunction "D_P$5") (pintype "bidirectional"))
      (node (ref "U$15") (pin "P$6") (pinfunction "D_P$6") (pintype "bidirectional"))
      (node (ref "U$15") (pin "P$7") (pinfunction "D_P$7") (pintype "bidirectional"))
      (node (ref "U$15") (pin "P$8") (pinfunction "D_P$8") (pintype "bidirectional"))
      (node (ref "U$8") (pin "P$8") (pinfunction "VS_P$8") (pintype "bidirectional"))
      (node (ref "U16") (pin "7") (pinfunction "VIN_7") (pintype "input"))
    )
    (net (code "131") (name "Net-(U$10-G)") (class "Default")
      (node (ref "U$10") (pin "P$4") (pinfunction "G_P$4") (pintype "bidirectional"))
      (node (ref "U$15") (pin "P$4") (pinfunction "G_P$4") (pintype "bidirectional"))
      (node (ref "U$8") (pin "P$6") (pinfunction "G2_P$6") (pintype "bidirectional"))
    )
    (net (code "132") (name "Net-(U$10-S-PadP$1)") (class "Default")
      (node (ref "U$10") (pin "P$1") (pinfunction "S_P$1") (pintype "bidirectional"))
      (node (ref "U$10") (pin "P$2") (pinfunction "S_P$2") (pintype "bidirectional"))
      (node (ref "U$10") (pin "P$3") (pinfunction "S_P$3") (pintype "bidirectional"))
      (node (ref "U$15") (pin "P$1") (pinfunction "S_P$1") (pintype "bidirectional"))
      (node (ref "U$15") (pin "P$2") (pinfunction "S_P$2") (pintype "bidirectional"))
      (node (ref "U$15") (pin "P$3") (pinfunction "S_P$3") (pintype "bidirectional"))
    )
    (net (code "133") (name "Net-(U$11-G1)") (class "Default")
      (node (ref "U$11") (pin "P$10") (pinfunction "G1_P$10") (pintype "bidirectional"))
      (node (ref "U$16") (pin "P$4") (pinfunction "G_P$4") (pintype "bidirectional"))
      (node (ref "U$22") (pin "P$4") (pinfunction "G_P$4") (pintype "bidirectional"))
    )
    (net (code "134") (name "Net-(U$11-G2)") (class "Default")
      (node (ref "U$11") (pin "P$6") (pinfunction "G2_P$6") (pintype "bidirectional"))
      (node (ref "U$17") (pin "P$4") (pinfunction "G_P$4") (pintype "bidirectional"))
      (node (ref "U$23") (pin "P$4") (pinfunction "G_P$4") (pintype "bidirectional"))
    )
    (net (code "135") (name "Net-(U$12-G1)") (class "Default")
      (node (ref "U$12") (pin "P$10") (pinfunction "G1_P$10") (pintype "bidirectional"))
      (node (ref "U$18") (pin "P$4") (pinfunction "G_P$4") (pintype "bidirectional"))
      (node (ref "U$24") (pin "P$4") (pinfunction "G_P$4") (pintype "bidirectional"))
    )
    (net (code "136") (name "Net-(U$12-G2)") (class "Default")
      (node (ref "U$12") (pin "P$6") (pinfunction "G2_P$6") (pintype "bidirectional"))
      (node (ref "U$19") (pin "P$4") (pinfunction "G_P$4") (pintype "bidirectional"))
      (node (ref "U$25") (pin "P$4") (pinfunction "G_P$4") (pintype "bidirectional"))
    )
    (net (code "137") (name "Net-(U$13-G1)") (class "Default")
      (node (ref "U$13") (pin "P$10") (pinfunction "G1_P$10") (pintype "bidirectional"))
      (node (ref "U$20") (pin "P$4") (pinfunction "G_P$4") (pintype "bidirectional"))
      (node (ref "U$26") (pin "P$4") (pinfunction "G_P$4") (pintype "bidirectional"))
    )
    (net (code "138") (name "Net-(U$13-G2)") (class "Default")
      (node (ref "U$13") (pin "P$6") (pinfunction "G2_P$6") (pintype "bidirectional"))
      (node (ref "U$21") (pin "P$4") (pinfunction "G_P$4") (pintype "bidirectional"))
      (node (ref "U$27") (pin "P$4") (pinfunction "G_P$4") (pintype "bidirectional"))
    )
    (net (code "139") (name "Net-(U$14-G)") (class "Default")
      (node (ref "U$14") (pin "P$4") (pinfunction "G_P$4") (pintype "bidirectional"))
      (node (ref "U$8") (pin "P$10") (pinfunction "G1_P$10") (pintype "bidirectional"))
      (node (ref "U$9") (pin "P$4") (pinfunction "G_P$4") (pintype "bidirectional"))
    )
    (net (code "140") (name "Net-(U$14-S-PadP$1)") (class "Default")
      (node (ref "U$14") (pin "P$1") (pinfunction "S_P$1") (pintype "bidirectional"))
      (node (ref "U$14") (pin "P$2") (pinfunction "S_P$2") (pintype "bidirectional"))
      (node (ref "U$14") (pin "P$3") (pinfunction "S_P$3") (pintype "bidirectional"))
      (node (ref "U$9") (pin "P$1") (pinfunction "S_P$1") (pintype "bidirectional"))
      (node (ref "U$9") (pin "P$2") (pinfunction "S_P$2") (pintype "bidirectional"))
      (node (ref "U$9") (pin "P$3") (pinfunction "S_P$3") (pintype "bidirectional"))
    )
    (net (code "141") (name "Net-(U$16-S-PadP$1)") (class "Default")
      (node (ref "U$16") (pin "P$1") (pinfunction "S_P$1") (pintype "bidirectional"))
      (node (ref "U$16") (pin "P$2") (pinfunction "S_P$2") (pintype "bidirectional"))
      (node (ref "U$16") (pin "P$3") (pinfunction "S_P$3") (pintype "bidirectional"))
      (node (ref "U$22") (pin "P$1") (pinfunction "S_P$1") (pintype "bidirectional"))
      (node (ref "U$22") (pin "P$2") (pinfunction "S_P$2") (pintype "bidirectional"))
      (node (ref "U$22") (pin "P$3") (pinfunction "S_P$3") (pintype "bidirectional"))
    )
    (net (code "142") (name "Net-(U$17-S-PadP$1)") (class "Default")
      (node (ref "U$17") (pin "P$1") (pinfunction "S_P$1") (pintype "bidirectional"))
      (node (ref "U$17") (pin "P$2") (pinfunction "S_P$2") (pintype "bidirectional"))
      (node (ref "U$17") (pin "P$3") (pinfunction "S_P$3") (pintype "bidirectional"))
      (node (ref "U$23") (pin "P$1") (pinfunction "S_P$1") (pintype "bidirectional"))
      (node (ref "U$23") (pin "P$2") (pinfunction "S_P$2") (pintype "bidirectional"))
      (node (ref "U$23") (pin "P$3") (pinfunction "S_P$3") (pintype "bidirectional"))
    )
    (net (code "143") (name "Net-(U$18-S-PadP$1)") (class "Default")
      (node (ref "U$18") (pin "P$1") (pinfunction "S_P$1") (pintype "bidirectional"))
      (node (ref "U$18") (pin "P$2") (pinfunction "S_P$2") (pintype "bidirectional"))
      (node (ref "U$18") (pin "P$3") (pinfunction "S_P$3") (pintype "bidirectional"))
      (node (ref "U$24") (pin "P$1") (pinfunction "S_P$1") (pintype "bidirectional"))
      (node (ref "U$24") (pin "P$2") (pinfunction "S_P$2") (pintype "bidirectional"))
      (node (ref "U$24") (pin "P$3") (pinfunction "S_P$3") (pintype "bidirectional"))
    )
    (net (code "144") (name "Net-(U$19-S-PadP$1)") (class "Default")
      (node (ref "U$19") (pin "P$1") (pinfunction "S_P$1") (pintype "bidirectional"))
      (node (ref "U$19") (pin "P$2") (pinfunction "S_P$2") (pintype "bidirectional"))
      (node (ref "U$19") (pin "P$3") (pinfunction "S_P$3") (pintype "bidirectional"))
      (node (ref "U$25") (pin "P$1") (pinfunction "S_P$1") (pintype "bidirectional"))
      (node (ref "U$25") (pin "P$2") (pinfunction "S_P$2") (pintype "bidirectional"))
      (node (ref "U$25") (pin "P$3") (pinfunction "S_P$3") (pintype "bidirectional"))
    )
    (net (code "145") (name "Net-(U$20-S-PadP$1)") (class "Default")
      (node (ref "U$20") (pin "P$1") (pinfunction "S_P$1") (pintype "bidirectional"))
      (node (ref "U$20") (pin "P$2") (pinfunction "S_P$2") (pintype "bidirectional"))
      (node (ref "U$20") (pin "P$3") (pinfunction "S_P$3") (pintype "bidirectional"))
      (node (ref "U$26") (pin "P$1") (pinfunction "S_P$1") (pintype "bidirectional"))
      (node (ref "U$26") (pin "P$2") (pinfunction "S_P$2") (pintype "bidirectional"))
      (node (ref "U$26") (pin "P$3") (pinfunction "S_P$3") (pintype "bidirectional"))
    )
    (net (code "146") (name "Net-(U$21-S-PadP$1)") (class "Default")
      (node (ref "U$21") (pin "P$1") (pinfunction "S_P$1") (pintype "bidirectional"))
      (node (ref "U$21") (pin "P$2") (pinfunction "S_P$2") (pintype "bidirectional"))
      (node (ref "U$21") (pin "P$3") (pinfunction "S_P$3") (pintype "bidirectional"))
      (node (ref "U$27") (pin "P$1") (pinfunction "S_P$1") (pintype "bidirectional"))
      (node (ref "U$27") (pin "P$2") (pinfunction "S_P$2") (pintype "bidirectional"))
      (node (ref "U$27") (pin "P$3") (pinfunction "S_P$3") (pintype "bidirectional"))
    )
    (net (code "147") (name "Net-(U1-DD+)") (class "Default")
      (node (ref "R4") (pin "1") (pinfunction "1_1") (pintype "passive"))
      (node (ref "U1") (pin "10") (pinfunction "DD+_10") (pintype "bidirectional"))
    )
    (net (code "148") (name "Net-(U1-DD-)") (class "Default")
      (node (ref "R3") (pin "1") (pinfunction "1_1") (pintype "passive"))
      (node (ref "U1") (pin "11") (pinfunction "DD-_11") (pintype "bidirectional"))
    )
    (net (code "149") (name "Net-(U1-GND1)") (class "Default")
      (node (ref "C1") (pin "1") (pinfunction "1_1") (pintype "passive"))
      (node (ref "C2") (pin "1") (pinfunction "1_1") (pintype "passive"))
      (node (ref "R1") (pin "1") (pinfunction "1_1") (pintype "passive"))
      (node (ref "U$1") (pin "GND") (pinfunction "GND_GND") (pintype "bidirectional"))
      (node (ref "U1") (pin "2") (pinfunction "GND1_2_2") (pintype "passive"))
      (node (ref "U1") (pin "8") (pinfunction "GND1_8") (pintype "passive"))
    )
    (net (code "150") (name "Net-(U1-PDEN)") (class "Default")
      (node (ref "C1") (pin "2") (pinfunction "2_2") (pintype "passive"))
      (node (ref "U1") (pin "3") (pinfunction "VDD1_3") (pintype "bidirectional"))
      (node (ref "U1") (pin "4") (pinfunction "PDEN_4") (pintype "input"))
      (node (ref "U1") (pin "5") (pinfunction "SPU_5") (pintype "input"))
    )
    (net (code "151") (name "Net-(U1-PIN)") (class "Default")
      (node (ref "C3") (pin "2") (pinfunction "2_2") (pintype "passive"))
      (node (ref "U1") (pin "12") (pinfunction "PIN_12") (pintype "input"))
      (node (ref "U1") (pin "13") (pinfunction "SPD_13") (pintype "input"))
      (node (ref "U1") (pin "14") (pinfunction "VDD2_14") (pintype "bidirectional"))
    )
    (net (code "152") (name "Net-(U1-UD+)") (class "Default")
      (node (ref "R6") (pin "1") (pinfunction "1_1") (pintype "passive"))
      (node (ref "U1") (pin "7") (pinfunction "UD+_7") (pintype "bidirectional"))
    )
    (net (code "153") (name "Net-(U1-UD-)") (class "Default")
      (node (ref "R5") (pin "1") (pinfunction "1_1") (pintype "passive"))
      (node (ref "U1") (pin "6") (pinfunction "UD-_6") (pintype "bidirectional"))
    )
    (net (code "154") (name "Net-(U1-VBUS1)") (class "Default")
      (node (ref "C2") (pin "2") (pinfunction "2_2") (pintype "passive"))
      (node (ref "LED1") (pin "A") (pinfunction "A_A") (pintype "passive"))
      (node (ref "U$1") (pin "VBUS") (pinfunction "VBUS_VBUS") (pintype "bidirectional"))
      (node (ref "U1") (pin "1") (pinfunction "VBUS1_1") (pintype "bidirectional"))
    )
    (net (code "155") (name "Net-(U2-DI)") (class "Default")
      (node (ref "R12") (pin "2") (pinfunction "2_2") (pintype "passive"))
      (node (ref "R15") (pin "2") (pinfunction "2_2") (pintype "passive"))
      (node (ref "U2") (pin "5") (pinfunction "DI_5") (pintype "bidirectional"))
    )
    (net (code "156") (name "Net-(U3-BOOST1)") (class "Default")
      (node (ref "C15") (pin "2") (pinfunction "2_2") (pintype "passive"))
      (node (ref "U3") (pin "2") (pinfunction "BOOST1_2") (pintype "input"))
    )
    (net (code "157") (name "Net-(U3-BOOST2)") (class "Default")
      (node (ref "C16") (pin "2") (pinfunction "2_2") (pintype "passive"))
      (node (ref "U3") (pin "7") (pinfunction "BOOST2_7") (pintype "input"))
    )
    (net (code "158") (name "Net-(U3-FB1)") (class "Default")
      (node (ref "R13") (pin "2") (pinfunction "2_2") (pintype "passive"))
      (node (ref "R14") (pin "1") (pinfunction "1_1") (pintype "passive"))
      (node (ref "U3") (pin "16") (pinfunction "FB1_16") (pintype "input"))
    )
    (net (code "159") (name "Net-(U3-FB2)") (class "Default")
      (node (ref "R22") (pin "2") (pinfunction "2_2") (pintype "passive"))
      (node (ref "R23") (pin "1") (pinfunction "1_1") (pintype "passive"))
      (node (ref "U3") (pin "9") (pinfunction "FB2_9") (pintype "input"))
    )
    (net (code "160") (name "Net-(U3-RT)") (class "Default")
      (node (ref "R18") (pin "1") (pinfunction "1_1") (pintype "passive"))
      (node (ref "U3") (pin "11") (pinfunction "RT_11") (pintype "input"))
    )
    (net (code "161") (name "Net-(U3-RUN{slash}SS1)") (class "Default")
      (node (ref "C13") (pin "2") (pinfunction "2_2") (pintype "passive"))
      (node (ref "U3") (pin "15") (pinfunction "RUN/SS1_15") (pintype "input"))
    )
    (net (code "162") (name "Net-(U3-RUN{slash}SS2)") (class "Default")
      (node (ref "C17") (pin "2") (pinfunction "2_2") (pintype "passive"))
      (node (ref "U3") (pin "10") (pinfunction "RUN/SS2_10") (pintype "input"))
    )
    (net (code "163") (name "Net-(U3-VIN)") (class "Default")
      (node (ref "C14") (pin "2") (pinfunction "2_2") (pintype "passive"))
      (node (ref "F1") (pin "P$2") (pinfunction "P$2_P$2") (pintype "bidirectional"))
      (node (ref "U3") (pin "4") (pinfunction "VIN_2_4") (pintype "input"))
      (node (ref "U3") (pin "5") (pinfunction "VIN_5") (pintype "input"))
    )
    (net (code "164") (name "Net-(U8-DD+)") (class "Default")
      (node (ref "R29") (pin "1") (pinfunction "1_1") (pintype "passive"))
      (node (ref "U8") (pin "10") (pinfunction "DD+_10") (pintype "bidirectional"))
    )
    (net (code "165") (name "Net-(U8-DD-)") (class "Default")
      (node (ref "R28") (pin "1") (pinfunction "1_1") (pintype "passive"))
      (node (ref "U8") (pin "11") (pinfunction "DD-_11") (pintype "bidirectional"))
    )
    (net (code "166") (name "Net-(U8-GND1)") (class "Default")
      (node (ref "C21") (pin "1") (pinfunction "1_1") (pintype "passive"))
      (node (ref "C22") (pin "1") (pinfunction "1_1") (pintype "passive"))
      (node (ref "U$5") (pin "GND") (pinfunction "GND_GND") (pintype "bidirectional"))
      (node (ref "U8") (pin "2") (pinfunction "GND1_2_2") (pintype "passive"))
      (node (ref "U8") (pin "8") (pinfunction "GND1_8") (pintype "passive"))
    )
    (net (code "167") (name "Net-(U8-PDEN)") (class "Default")
      (node (ref "C21") (pin "2") (pinfunction "2_2") (pintype "passive"))
      (node (ref "U8") (pin "3") (pinfunction "VDD1_3") (pintype "bidirectional"))
      (node (ref "U8") (pin "4") (pinfunction "PDEN_4") (pintype "input"))
      (node (ref "U8") (pin "5") (pinfunction "SPU_5") (pintype "input"))
    )
    (net (code "168") (name "Net-(U8-PIN)") (class "Default")
      (node (ref "C23") (pin "2") (pinfunction "2_2") (pintype "passive"))
      (node (ref "U8") (pin "12") (pinfunction "PIN_12") (pintype "input"))
      (node (ref "U8") (pin "13") (pinfunction "SPD_13") (pintype "input"))
      (node (ref "U8") (pin "14") (pinfunction "VDD2_14") (pintype "bidirectional"))
    )
    (net (code "169") (name "Net-(U8-UD+)") (class "Default")
      (node (ref "R31") (pin "1") (pinfunction "1_1") (pintype "passive"))
      (node (ref "U8") (pin "7") (pinfunction "UD+_7") (pintype "bidirectional"))
    )
    (net (code "170") (name "Net-(U8-UD-)") (class "Default")
      (node (ref "R30") (pin "1") (pinfunction "1_1") (pintype "passive"))
      (node (ref "U8") (pin "6") (pinfunction "UD-_6") (pintype "bidirectional"))
    )
    (net (code "171") (name "Net-(U8-VBUS1)") (class "Default")
      (node (ref "C22") (pin "2") (pinfunction "2_2") (pintype "passive"))
      (node (ref "U$5") (pin "VBUS") (pinfunction "VBUS_VBUS") (pintype "bidirectional"))
      (node (ref "U8") (pin "1") (pinfunction "VBUS1_1") (pintype "bidirectional"))
    )
    (net (code "172") (name "Net-(U9-CAP)") (class "Default")
      (node (ref "C29") (pin "2") (pinfunction "2_2") (pintype "passive"))
      (node (ref "U9") (pin "P$2") (pinfunction "CAP_P$2") (pintype "bidirectional"))
    )
    (net (code "173") (name "Net-(U10-DI)") (class "Default")
      (node (ref "R46") (pin "2") (pinfunction "2_2") (pintype "passive"))
      (node (ref "R47") (pin "2") (pinfunction "2_2") (pintype "passive"))
      (node (ref "U10") (pin "5") (pinfunction "DI_5") (pintype "bidirectional"))
    )
    (net (code "174") (name "Net-(U11-AREF)") (class "Default")
      (node (ref "C39") (pin "1") (pinfunction "1_1") (pintype "passive"))
      (node (ref "U11") (pin "20") (pinfunction "AREF_20") (pintype "input"))
    )
    (net (code "175") (name "Net-(U12-GND2)") (class "Default")
      (node (ref "JP11") (pin "3") (pinfunction "3_3") (pintype "passive"))
      (node (ref "U12") (pin "5") (pinfunction "GND2_5") (pintype "bidirectional"))
    )
    (net (code "176") (name "Net-(U12-INA)") (class "Default")
      (node (ref "JP11") (pin "1") (pinfunction "1_1") (pintype "passive"))
      (node (ref "U12") (pin "7") (pinfunction "INA_7") (pintype "bidirectional"))
    )
    (net (code "177") (name "Net-(U12-OUTB)") (class "Default")
      (node (ref "JP11") (pin "2") (pinfunction "2_2") (pintype "passive"))
      (node (ref "U12") (pin "6") (pinfunction "OUTB_6") (pintype "bidirectional"))
    )
    (net (code "178") (name "Net-(U13-GND2)") (class "Default")
      (node (ref "JP12") (pin "3") (pinfunction "3_3") (pintype "passive"))
      (node (ref "U13") (pin "5") (pinfunction "GND2_5") (pintype "bidirectional"))
    )
    (net (code "179") (name "Net-(U13-INA)") (class "Default")
      (node (ref "JP12") (pin "1") (pinfunction "1_1") (pintype "passive"))
      (node (ref "U13") (pin "7") (pinfunction "INA_7") (pintype "bidirectional"))
    )
    (net (code "180") (name "Net-(U13-OUTB)") (class "Default")
      (node (ref "JP12") (pin "2") (pinfunction "2_2") (pintype "passive"))
      (node (ref "U13") (pin "6") (pinfunction "OUTB_6") (pintype "bidirectional"))
    )
    (net (code "181") (name "Net-(U14-GND2)") (class "Default")
      (node (ref "JP13") (pin "3") (pinfunction "3_3") (pintype "passive"))
      (node (ref "U14") (pin "5") (pinfunction "GND2_5") (pintype "bidirectional"))
    )
    (net (code "182") (name "Net-(U14-INA)") (class "Default")
      (node (ref "JP13") (pin "1") (pinfunction "1_1") (pintype "passive"))
      (node (ref "U14") (pin "7") (pinfunction "INA_7") (pintype "bidirectional"))
    )
    (net (code "183") (name "Net-(U14-OUTB)") (class "Default")
      (node (ref "JP13") (pin "2") (pinfunction "2_2") (pintype "passive"))
      (node (ref "U14") (pin "6") (pinfunction "OUTB_6") (pintype "bidirectional"))
    )
    (net (code "184") (name "Net-(U15-GND2)") (class "Default")
      (node (ref "JP14") (pin "3") (pinfunction "3_3") (pintype "passive"))
      (node (ref "U15") (pin "5") (pinfunction "GND2_5") (pintype "bidirectional"))
    )
    (net (code "185") (name "Net-(U15-INA)") (class "Default")
      (node (ref "JP14") (pin "1") (pinfunction "1_1") (pintype "passive"))
      (node (ref "U15") (pin "7") (pinfunction "INA_7") (pintype "bidirectional"))
    )
    (net (code "186") (name "Net-(U15-OUTB)") (class "Default")
      (node (ref "JP14") (pin "2") (pinfunction "2_2") (pintype "passive"))
      (node (ref "U15") (pin "6") (pinfunction "OUTB_6") (pintype "bidirectional"))
    )
    (net (code "187") (name "Net-(U16-BOOT)") (class "Default")
      (node (ref "C41") (pin "2") (pinfunction "2_2") (pintype "passive"))
      (node (ref "U16") (pin "1") (pinfunction "BOOT_1") (pintype "passive"))
    )
    (net (code "188") (name "Net-(U16-VSENSE)") (class "Default")
      (node (ref "R60") (pin "1") (pinfunction "1_1") (pintype "passive"))
      (node (ref "R61") (pin "2") (pinfunction "2_2") (pintype "passive"))
      (node (ref "U16") (pin "4") (pinfunction "VSENSE_4") (pintype "output"))
    )
    (net (code "189") (name "Net-(U17-BOOT)") (class "Default")
      (node (ref "C46") (pin "2") (pinfunction "2_2") (pintype "passive"))
      (node (ref "U17") (pin "1") (pinfunction "BOOT_1") (pintype "passive"))
    )
    (net (code "190") (name "Net-(U17-VSENSE)") (class "Default")
      (node (ref "R64") (pin "1") (pinfunction "1_1") (pintype "passive"))
      (node (ref "R65") (pin "2") (pinfunction "2_2") (pintype "passive"))
      (node (ref "U17") (pin "4") (pinfunction "VSENSE_4") (pintype "output"))
    )
    (net (code "191") (name "Net-(U18-BOOST1)") (class "Default")
      (node (ref "C58") (pin "2") (pinfunction "2_2") (pintype "passive"))
      (node (ref "U18") (pin "2") (pinfunction "BOOST1_2") (pintype "input"))
    )
    (net (code "192") (name "Net-(U18-BOOST2)") (class "Default")
      (node (ref "C59") (pin "2") (pinfunction "2_2") (pintype "passive"))
      (node (ref "U18") (pin "7") (pinfunction "BOOST2_7") (pintype "input"))
    )
    (net (code "193") (name "Net-(U18-FB1)") (class "Default")
      (node (ref "R66") (pin "2") (pinfunction "2_2") (pintype "passive"))
      (node (ref "R67") (pin "1") (pinfunction "1_1") (pintype "passive"))
      (node (ref "U18") (pin "16") (pinfunction "FB1_16") (pintype "input"))
    )
    (net (code "194") (name "Net-(U18-FB2)") (class "Default")
      (node (ref "R69") (pin "2") (pinfunction "2_2") (pintype "passive"))
      (node (ref "R70") (pin "1") (pinfunction "1_1") (pintype "passive"))
      (node (ref "U18") (pin "9") (pinfunction "FB2_9") (pintype "input"))
    )
    (net (code "195") (name "Net-(U18-RT)") (class "Default")
      (node (ref "R68") (pin "1") (pinfunction "1_1") (pintype "passive"))
      (node (ref "U18") (pin "11") (pinfunction "RT_11") (pintype "input"))
    )
    (net (code "196") (name "Net-(U18-RUN{slash}SS1)") (class "Default")
      (node (ref "C56") (pin "2") (pinfunction "2_2") (pintype "passive"))
      (node (ref "U18") (pin "15") (pinfunction "RUN/SS1_15") (pintype "input"))
    )
    (net (code "197") (name "Net-(U18-RUN{slash}SS2)") (class "Default")
      (node (ref "C60") (pin "2") (pinfunction "2_2") (pintype "passive"))
      (node (ref "U18") (pin "10") (pinfunction "RUN/SS2_10") (pintype "input"))
    )
    (net (code "198") (name "Net-(U18-VIN)") (class "Default")
      (node (ref "C57") (pin "2") (pinfunction "2_2") (pintype "passive"))
      (node (ref "F3") (pin "P$2") (pinfunction "P$2_P$2") (pintype "bidirectional"))
      (node (ref "U18") (pin "4") (pinfunction "VIN_2_4") (pintype "input"))
      (node (ref "U18") (pin "5") (pinfunction "VIN_5") (pintype "input"))
    )
    (net (code "199") (name "PE") (class "Default")
      (node (ref "C32") (pin "-") (pinfunction "-_-") (pintype "passive"))
      (node (ref "C33") (pin "-") (pinfunction "-_-") (pintype "passive"))
      (node (ref "C44") (pin "P$2") (pinfunction "P$2_P$2") (pintype "bidirectional"))
      (node (ref "C45") (pin "P$2") (pinfunction "P$2_P$2") (pintype "bidirectional"))
      (node (ref "C47") (pin "1") (pinfunction "1_1") (pintype "passive"))
      (node (ref "C50") (pin "P$2") (pinfunction "P$2_P$2") (pintype "bidirectional"))
      (node (ref "C52") (pin "1") (pinfunction "1_1") (pintype "passive"))
      (node (ref "C54") (pin "P$2") (pinfunction "P$2_P$2") (pintype "bidirectional"))
      (node (ref "D4") (pin "1") (pinfunction "P$2_1") (pintype "bidirectional"))
      (node (ref "F2") (pin "P$1") (pinfunction "P$1_P$1") (pintype "bidirectional"))
      (node (ref "JP16") (pin "1") (pinfunction "1_1") (pintype "passive"))
      (node (ref "JP18") (pin "P$10") (pinfunction "P$10_P$10") (pintype "bidirectional"))
      (node (ref "JP18") (pin "P$12") (pinfunction "P$12_P$12") (pintype "bidirectional"))
      (node (ref "JP18") (pin "P$14") (pinfunction "P$14_P$14") (pintype "bidirectional"))
      (node (ref "JP18") (pin "P$16") (pinfunction "P$16_P$16") (pintype "bidirectional"))
      (node (ref "JP18") (pin "P$2") (pinfunction "P$2_P$2") (pintype "bidirectional"))
      (node (ref "JP18") (pin "P$4") (pinfunction "P$4_P$4") (pintype "bidirectional"))
      (node (ref "JP18") (pin "P$6") (pinfunction "P$6_P$6") (pintype "bidirectional"))
      (node (ref "JP18") (pin "P$8") (pinfunction "P$8_P$8") (pintype "bidirectional"))
      (node (ref "JP2") (pin "P$1") (pinfunction "P$1_P$1") (pintype "bidirectional"))
      (node (ref "JP2") (pin "P$13") (pinfunction "P$13_P$13") (pintype "bidirectional"))
      (node (ref "JP2") (pin "P$14") (pinfunction "P$14_P$14") (pintype "bidirectional"))
      (node (ref "JP2") (pin "P$15") (pinfunction "P$15_P$15") (pintype "bidirectional"))
      (node (ref "JP2") (pin "P$16") (pinfunction "P$16_P$16") (pintype "bidirectional"))
      (node (ref "JP2") (pin "P$2") (pinfunction "P$2_P$2") (pintype "bidirectional"))
      (node (ref "JP2") (pin "P$3") (pinfunction "P$3_P$3") (pintype "bidirectional"))
      (node (ref "JP2") (pin "P$4") (pinfunction "P$4_P$4") (pintype "bidirectional"))
      (node (ref "R32") (pin "1") (pinfunction "1_1") (pintype "passive"))
      (node (ref "R33") (pin "1") (pinfunction "1_1") (pintype "passive"))
      (node (ref "R58") (pin "1") (pinfunction "1_1") (pintype "passive"))
      (node (ref "R59") (pin "1") (pinfunction "1_1") (pintype "passive"))
      (node (ref "R62") (pin "2") (pinfunction "2_2") (pintype "passive"))
      (node (ref "R63") (pin "2") (pinfunction "2_2") (pintype "passive"))
      (node (ref "R65") (pin "1") (pinfunction "1_1") (pintype "passive"))
      (node (ref "U$11") (pin "P$3") (pinfunction "GND_P$3") (pintype "bidirectional"))
      (node (ref "U$12") (pin "P$3") (pinfunction "GND_P$3") (pintype "bidirectional"))
      (node (ref "U$13") (pin "P$3") (pinfunction "GND_P$3") (pintype "bidirectional"))
      (node (ref "U17") (pin "6") (pinfunction "GND_6") (pintype "passive"))
      (node (ref "U17") (pin "9") (pinfunction "EP_9") (pintype "passive"))
    )
    (net (code "200") (name "unconnected-(IC1A-DB2{slash}RTS-Pad18)") (class "Default")
      (node (ref "IC1") (pin "18") (pinfunction "DB2/RTS_18") (pintype "bidirectional"))
    )
    (net (code "201") (name "unconnected-(IC1A-DB3{slash}CTS-Pad19)") (class "Default")
      (node (ref "IC1") (pin "19") (pinfunction "DB3/CTS_19") (pintype "bidirectional"))
    )
    (net (code "202") (name "unconnected-(IC1A-DB4{slash}DTR-Pad21)") (class "Default")
      (node (ref "IC1") (pin "21") (pinfunction "DB4/DTR_21") (pintype "bidirectional"))
    )
    (net (code "203") (name "unconnected-(IC1A-DB5{slash}DSR-Pad22)") (class "Default")
      (node (ref "IC1") (pin "22") (pinfunction "DB5/DSR_22") (pintype "bidirectional"))
    )
    (net (code "204") (name "unconnected-(IC1A-DB6{slash}DCD-Pad23)") (class "Default")
      (node (ref "IC1") (pin "23") (pinfunction "DB6/DCD_23") (pintype "bidirectional"))
    )
    (net (code "205") (name "unconnected-(IC1A-DB7{slash}RI-Pad24)") (class "Default")
      (node (ref "IC1") (pin "24") (pinfunction "DB7/RI_24") (pintype "bidirectional"))
    )
    (net (code "206") (name "unconnected-(IC1B-DB2{slash}RTS-Pad28)") (class "Default")
      (node (ref "IC1") (pin "28") (pinfunction "DB2/RTS_28") (pintype "bidirectional"))
    )
    (net (code "207") (name "unconnected-(IC1B-DB3{slash}CTS-Pad29)") (class "Default")
      (node (ref "IC1") (pin "29") (pinfunction "DB3/CTS_29") (pintype "bidirectional"))
    )
    (net (code "208") (name "unconnected-(IC1B-DB4{slash}DTR-Pad30)") (class "Default")
      (node (ref "IC1") (pin "30") (pinfunction "DB4/DTR_30") (pintype "bidirectional"))
    )
    (net (code "209") (name "unconnected-(IC1B-DB5{slash}DSR-Pad32)") (class "Default")
      (node (ref "IC1") (pin "32") (pinfunction "DB5/DSR_32") (pintype "bidirectional"))
    )
    (net (code "210") (name "unconnected-(IC1B-DB6{slash}DCD-Pad33)") (class "Default")
      (node (ref "IC1") (pin "33") (pinfunction "DB6/DCD_33") (pintype "bidirectional"))
    )
    (net (code "211") (name "unconnected-(IC1B-DB7{slash}RI-Pad34)") (class "Default")
      (node (ref "IC1") (pin "34") (pinfunction "DB7/RI_34") (pintype "bidirectional"))
    )
    (net (code "212") (name "unconnected-(IC1C-DB2{slash}RTS-Pad40)") (class "Default")
      (node (ref "IC1") (pin "40") (pinfunction "DB2/RTS_40") (pintype "bidirectional"))
    )
    (net (code "213") (name "unconnected-(IC1C-DB3{slash}CTS-Pad41)") (class "Default")
      (node (ref "IC1") (pin "41") (pinfunction "DB3/CTS_41") (pintype "bidirectional"))
    )
    (net (code "214") (name "unconnected-(IC1C-DB4{slash}DTR-Pad43)") (class "Default")
      (node (ref "IC1") (pin "43") (pinfunction "DB4/DTR_43") (pintype "bidirectional"))
    )
    (net (code "215") (name "unconnected-(IC1C-DB5{slash}DSR-Pad44)") (class "Default")
      (node (ref "IC1") (pin "44") (pinfunction "DB5/DSR_44") (pintype "bidirectional"))
    )
    (net (code "216") (name "unconnected-(IC1C-DB6{slash}DCD-Pad45)") (class "Default")
      (node (ref "IC1") (pin "45") (pinfunction "DB6/DCD_45") (pintype "bidirectional"))
    )
    (net (code "217") (name "unconnected-(IC1C-DB7{slash}RI-Pad46)") (class "Default")
      (node (ref "IC1") (pin "46") (pinfunction "DB7/RI_46") (pintype "bidirectional"))
    )
    (net (code "218") (name "unconnected-(IC1D-PWREN#-Pad60)") (class "Default")
      (node (ref "IC1") (pin "60") (pinfunction "PWREN#_60") (pintype "output"))
    )
    (net (code "219") (name "unconnected-(IC1D-SUSPEND#-Pad36)") (class "Default")
      (node (ref "IC1") (pin "36") (pinfunction "SUSPEND#_36") (pintype "output"))
    )
    (net (code "220") (name "unconnected-(IC2A-DB2{slash}RTS-Pad18)") (class "Default")
      (node (ref "IC2") (pin "18") (pinfunction "DB2/RTS_18") (pintype "bidirectional"))
    )
    (net (code "221") (name "unconnected-(IC2A-DB3{slash}CTS-Pad19)") (class "Default")
      (node (ref "IC2") (pin "19") (pinfunction "DB3/CTS_19") (pintype "bidirectional"))
    )
    (net (code "222") (name "unconnected-(IC2A-DB4{slash}DTR-Pad21)") (class "Default")
      (node (ref "IC2") (pin "21") (pinfunction "DB4/DTR_21") (pintype "bidirectional"))
    )
    (net (code "223") (name "unconnected-(IC2A-DB5{slash}DSR-Pad22)") (class "Default")
      (node (ref "IC2") (pin "22") (pinfunction "DB5/DSR_22") (pintype "bidirectional"))
    )
    (net (code "224") (name "unconnected-(IC2A-DB6{slash}DCD-Pad23)") (class "Default")
      (node (ref "IC2") (pin "23") (pinfunction "DB6/DCD_23") (pintype "bidirectional"))
    )
    (net (code "225") (name "unconnected-(IC2A-DB7{slash}RI-Pad24)") (class "Default")
      (node (ref "IC2") (pin "24") (pinfunction "DB7/RI_24") (pintype "bidirectional"))
    )
    (net (code "226") (name "unconnected-(IC2B-DB2{slash}RTS-Pad28)") (class "Default")
      (node (ref "IC2") (pin "28") (pinfunction "DB2/RTS_28") (pintype "bidirectional"))
    )
    (net (code "227") (name "unconnected-(IC2B-DB3{slash}CTS-Pad29)") (class "Default")
      (node (ref "IC2") (pin "29") (pinfunction "DB3/CTS_29") (pintype "bidirectional"))
    )
    (net (code "228") (name "unconnected-(IC2B-DB4{slash}DTR-Pad30)") (class "Default")
      (node (ref "IC2") (pin "30") (pinfunction "DB4/DTR_30") (pintype "bidirectional"))
    )
    (net (code "229") (name "unconnected-(IC2B-DB5{slash}DSR-Pad32)") (class "Default")
      (node (ref "IC2") (pin "32") (pinfunction "DB5/DSR_32") (pintype "bidirectional"))
    )
    (net (code "230") (name "unconnected-(IC2B-DB6{slash}DCD-Pad33)") (class "Default")
      (node (ref "IC2") (pin "33") (pinfunction "DB6/DCD_33") (pintype "bidirectional"))
    )
    (net (code "231") (name "unconnected-(IC2B-DB7{slash}RI-Pad34)") (class "Default")
      (node (ref "IC2") (pin "34") (pinfunction "DB7/RI_34") (pintype "bidirectional"))
    )
    (net (code "232") (name "unconnected-(IC2C-DB2{slash}RTS-Pad40)") (class "Default")
      (node (ref "IC2") (pin "40") (pinfunction "DB2/RTS_40") (pintype "bidirectional"))
    )
    (net (code "233") (name "unconnected-(IC2C-DB3{slash}CTS-Pad41)") (class "Default")
      (node (ref "IC2") (pin "41") (pinfunction "DB3/CTS_41") (pintype "bidirectional"))
    )
    (net (code "234") (name "unconnected-(IC2C-DB4{slash}DTR-Pad43)") (class "Default")
      (node (ref "IC2") (pin "43") (pinfunction "DB4/DTR_43") (pintype "bidirectional"))
    )
    (net (code "235") (name "unconnected-(IC2C-DB5{slash}DSR-Pad44)") (class "Default")
      (node (ref "IC2") (pin "44") (pinfunction "DB5/DSR_44") (pintype "bidirectional"))
    )
    (net (code "236") (name "unconnected-(IC2C-DB6{slash}DCD-Pad45)") (class "Default")
      (node (ref "IC2") (pin "45") (pinfunction "DB6/DCD_45") (pintype "bidirectional"))
    )
    (net (code "237") (name "unconnected-(IC2C-DB7{slash}RI-Pad46)") (class "Default")
      (node (ref "IC2") (pin "46") (pinfunction "DB7/RI_46") (pintype "bidirectional"))
    )
    (net (code "238") (name "unconnected-(IC2D-PWREN#-Pad60)") (class "Default")
      (node (ref "IC2") (pin "60") (pinfunction "PWREN#_60") (pintype "output"))
    )
    (net (code "239") (name "unconnected-(IC2D-SUSPEND#-Pad36)") (class "Default")
      (node (ref "IC2") (pin "36") (pinfunction "SUSPEND#_36") (pintype "output"))
    )
    (net (code "240") (name "unconnected-(IC2E-DB2{slash}RTS-Pad53)") (class "Default")
      (node (ref "IC2") (pin "53") (pinfunction "DB2/RTS_53") (pintype "bidirectional"))
    )
    (net (code "241") (name "unconnected-(IC2E-DB3{slash}CTS-Pad54)") (class "Default")
      (node (ref "IC2") (pin "54") (pinfunction "DB3/CTS_54") (pintype "bidirectional"))
    )
    (net (code "242") (name "unconnected-(IC2E-DB4{slash}DTR-Pad55)") (class "Default")
      (node (ref "IC2") (pin "55") (pinfunction "DB4/DTR_55") (pintype "bidirectional"))
    )
    (net (code "243") (name "unconnected-(IC2E-DB5{slash}DSR-Pad57)") (class "Default")
      (node (ref "IC2") (pin "57") (pinfunction "DB5/DSR_57") (pintype "bidirectional"))
    )
    (net (code "244") (name "unconnected-(IC2E-DB6{slash}DCD-Pad58)") (class "Default")
      (node (ref "IC2") (pin "58") (pinfunction "DB6/DCD_58") (pintype "bidirectional"))
    )
    (net (code "245") (name "unconnected-(IC2E-DB7{slash}RI-Pad59)") (class "Default")
      (node (ref "IC2") (pin "59") (pinfunction "DB7/RI_59") (pintype "bidirectional"))
    )
    (net (code "246") (name "unconnected-(U$1-MTN1-PadMTN3)") (class "Default")
      (node (ref "U$1") (pin "MTN3") (pinfunction "MTN1_MTN3") (pintype "bidirectional"))
    )
    (net (code "247") (name "unconnected-(U$1-MTN2-PadMTN1)") (class "Default")
      (node (ref "U$1") (pin "MTN1") (pinfunction "MTN2_MTN1") (pintype "bidirectional"))
    )
    (net (code "248") (name "unconnected-(U$1-MTN3-PadMTN2)") (class "Default")
      (node (ref "U$1") (pin "MTN2") (pinfunction "MTN3_MTN2") (pintype "bidirectional"))
    )
    (net (code "249") (name "unconnected-(U$1-PadID)") (class "Default")
      (node (ref "U$1") (pin "ID") (pinfunction "ID_ID") (pintype "bidirectional"))
    )
    (net (code "250") (name "unconnected-(U$1-PadMTN4)") (class "Default")
      (node (ref "U$1") (pin "MTN4") (pinfunction "MTN4_MTN4") (pintype "bidirectional"))
    )
    (net (code "251") (name "unconnected-(U$5-MTN1-PadMTN3)") (class "Default")
      (node (ref "U$5") (pin "MTN3") (pinfunction "MTN1_MTN3") (pintype "bidirectional"))
    )
    (net (code "252") (name "unconnected-(U$5-MTN2-PadMTN1)") (class "Default")
      (node (ref "U$5") (pin "MTN1") (pinfunction "MTN2_MTN1") (pintype "bidirectional"))
    )
    (net (code "253") (name "unconnected-(U$5-MTN3-PadMTN2)") (class "Default")
      (node (ref "U$5") (pin "MTN2") (pinfunction "MTN3_MTN2") (pintype "bidirectional"))
    )
    (net (code "254") (name "unconnected-(U$5-PadID)") (class "Default")
      (node (ref "U$5") (pin "ID") (pinfunction "ID_ID") (pintype "bidirectional"))
    )
    (net (code "255") (name "unconnected-(U$5-PadMTN4)") (class "Default")
      (node (ref "U$5") (pin "MTN4") (pinfunction "MTN4_MTN4") (pintype "bidirectional"))
    )
    (net (code "256") (name "unconnected-(U$8-H1-PadP$1)") (class "Default")
      (node (ref "U$8") (pin "P$1") (pinfunction "H1_P$1") (pintype "bidirectional"))
    )
    (net (code "257") (name "unconnected-(U$8-H2-PadP$5)") (class "Default")
      (node (ref "U$8") (pin "P$5") (pinfunction "H2_P$5") (pintype "bidirectional"))
    )
    (net (code "258") (name "unconnected-(U$11-H1-PadP$1)") (class "Default")
      (node (ref "U$11") (pin "P$1") (pinfunction "H1_P$1") (pintype "bidirectional"))
    )
    (net (code "259") (name "unconnected-(U$11-H2-PadP$5)") (class "Default")
      (node (ref "U$11") (pin "P$5") (pinfunction "H2_P$5") (pintype "bidirectional"))
    )
    (net (code "260") (name "unconnected-(U$12-H1-PadP$1)") (class "Default")
      (node (ref "U$12") (pin "P$1") (pinfunction "H1_P$1") (pintype "bidirectional"))
    )
    (net (code "261") (name "unconnected-(U$12-H2-PadP$5)") (class "Default")
      (node (ref "U$12") (pin "P$5") (pinfunction "H2_P$5") (pintype "bidirectional"))
    )
    (net (code "262") (name "unconnected-(U$13-H1-PadP$1)") (class "Default")
      (node (ref "U$13") (pin "P$1") (pinfunction "H1_P$1") (pintype "bidirectional"))
    )
    (net (code "263") (name "unconnected-(U$13-H2-PadP$5)") (class "Default")
      (node (ref "U$13") (pin "P$5") (pinfunction "H2_P$5") (pintype "bidirectional"))
    )
    (net (code "264") (name "unconnected-(U2-NC-Pad1)") (class "Default")
      (node (ref "U2") (pin "1") (pinfunction "NC_1") (pintype "bidirectional"))
    )
    (net (code "265") (name "unconnected-(U9-NC-PadP$6)") (class "Default")
      (node (ref "U9") (pin "P$6") (pinfunction "NC_P$6") (pintype "bidirectional"))
    )
    (net (code "266") (name "unconnected-(U10-NC-Pad1)") (class "Default")
      (node (ref "U10") (pin "1") (pinfunction "NC_1") (pintype "bidirectional"))
    )
    (net (code "267") (name "unconnected-(U16-ENA-Pad5)") (class "Default")
      (node (ref "U16") (pin "5") (pinfunction "ENA_5") (pintype "input"))
    )
    (net (code "268") (name "unconnected-(U16-NC-Pad3)") (class "Default")
      (node (ref "U16") (pin "3") (pinfunction "NC_3") (pintype "no_connect"))
    )
    (net (code "269") (name "unconnected-(U16-NC_2-Pad2)") (class "Default")
      (node (ref "U16") (pin "2") (pinfunction "NC_2_2") (pintype "no_connect"))
    )
    (net (code "270") (name "unconnected-(U17-ENA-Pad5)") (class "Default")
      (node (ref "U17") (pin "5") (pinfunction "ENA_5") (pintype "input"))
    )
    (net (code "271") (name "unconnected-(U17-NC-Pad3)") (class "Default")
      (node (ref "U17") (pin "3") (pinfunction "NC_3") (pintype "no_connect"))
    )
    (net (code "272") (name "unconnected-(U17-NC_2-Pad2)") (class "Default")
      (node (ref "U17") (pin "2") (pinfunction "NC_2_2") (pintype "no_connect"))
    )
  )
)
